# EA08AI.net
KiCad netlist of a schematic drawn in Altium Designer
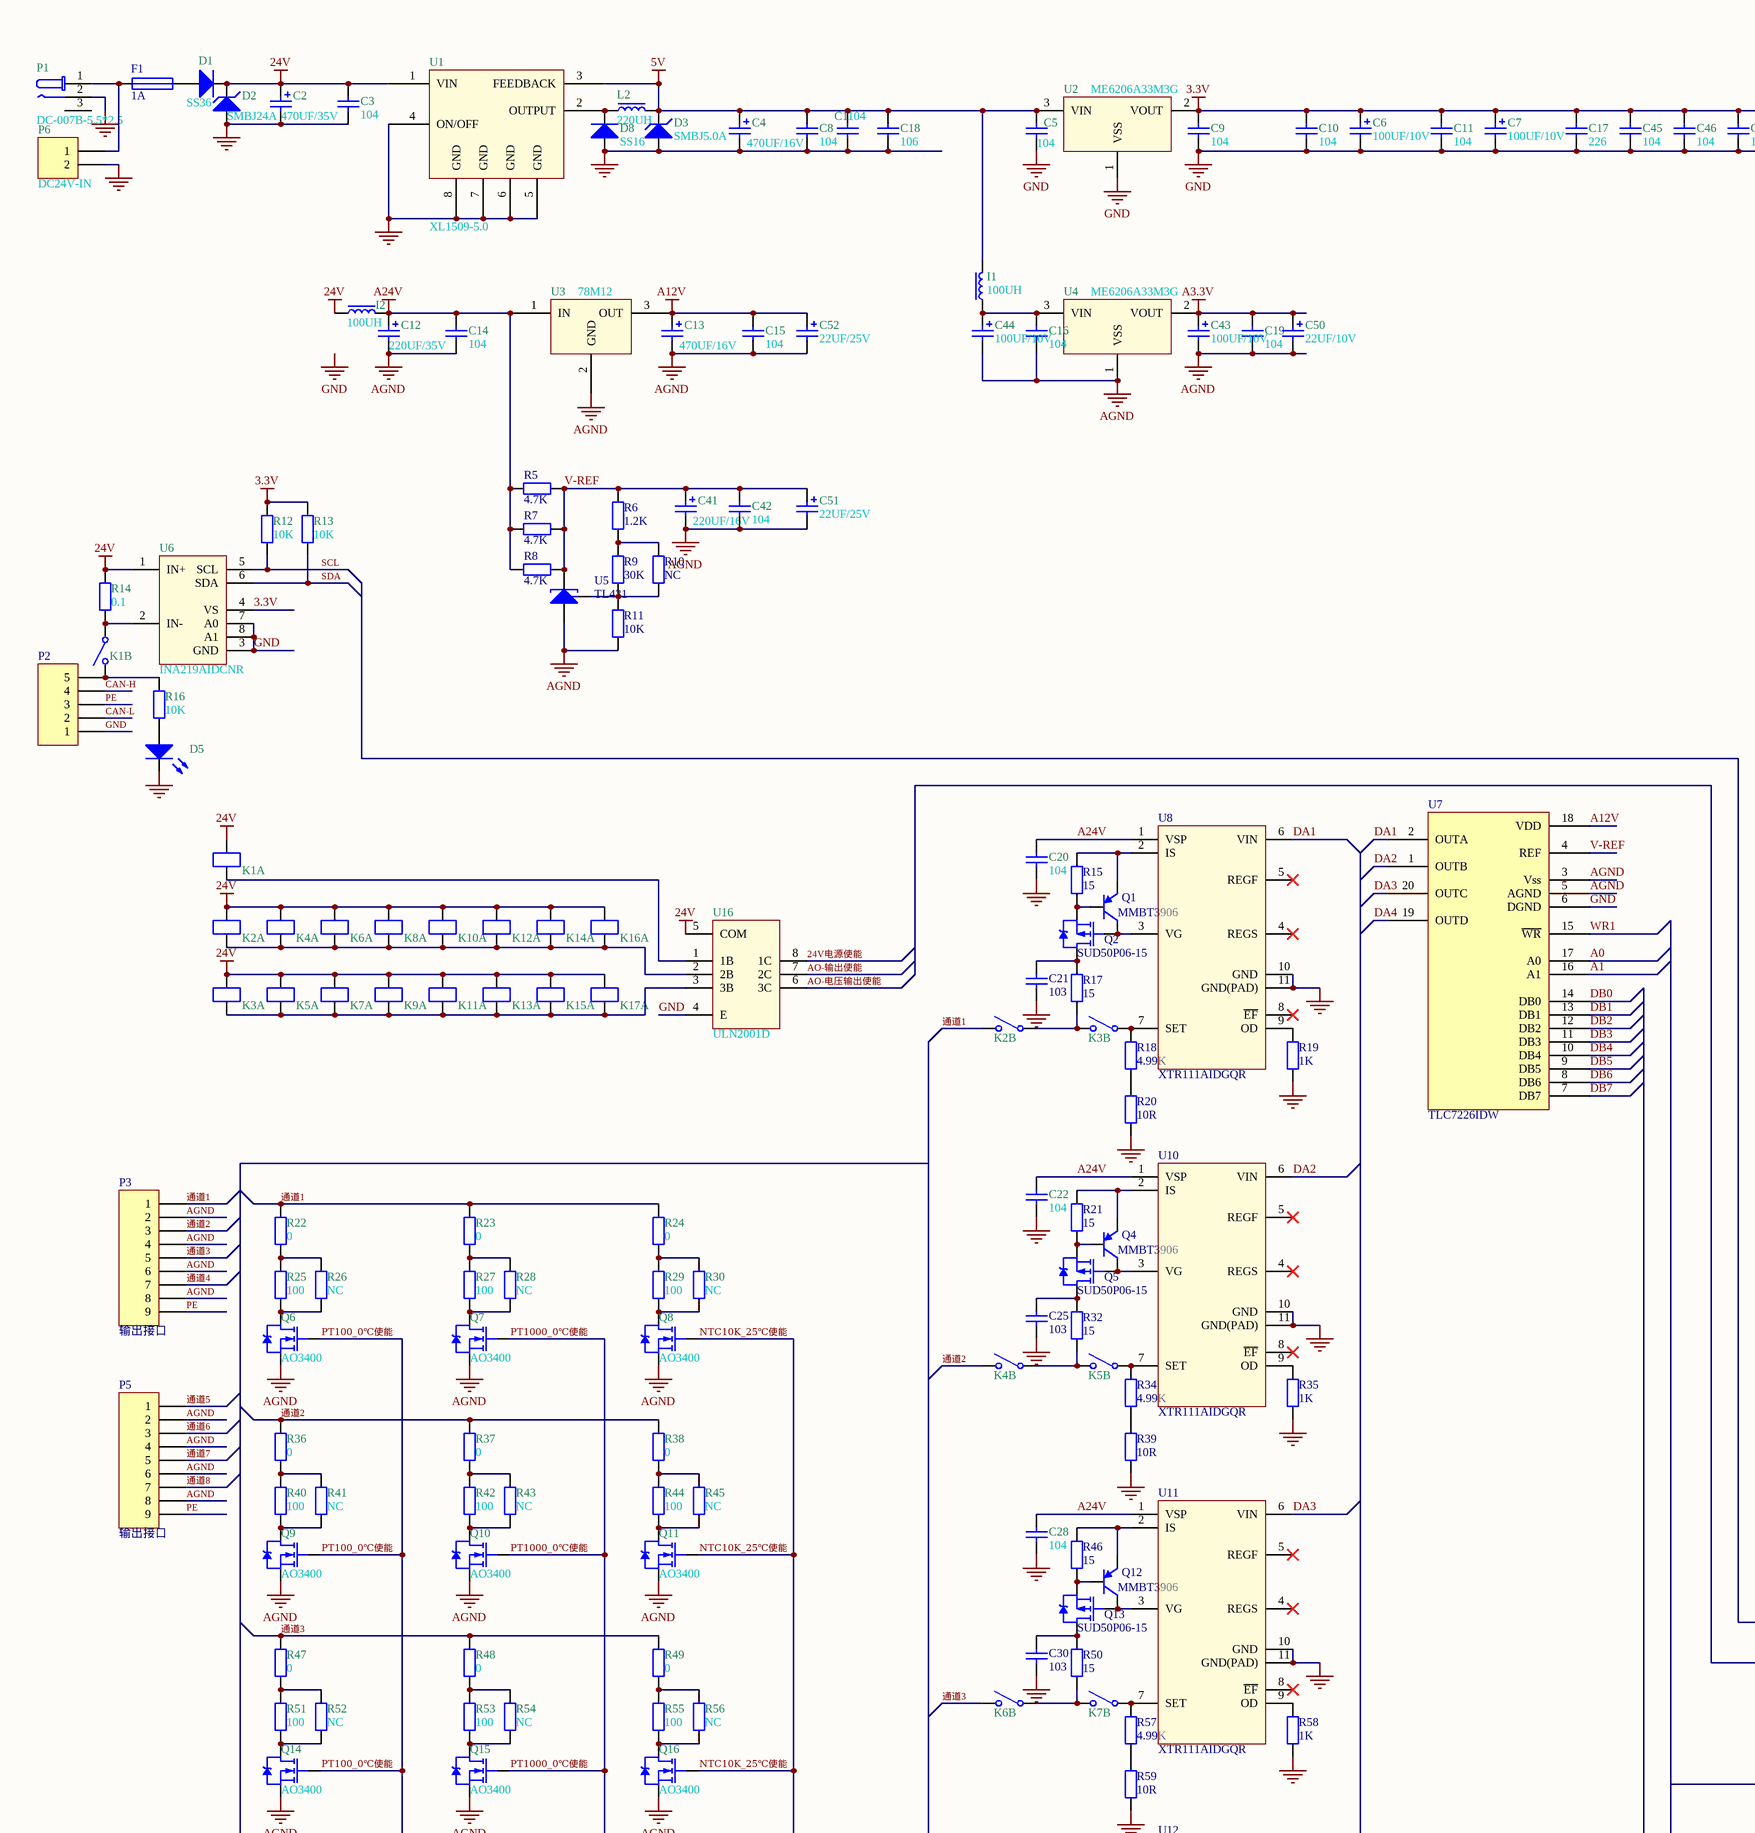
[diagram p0: EA08AI测试板.SchDoc, top left]
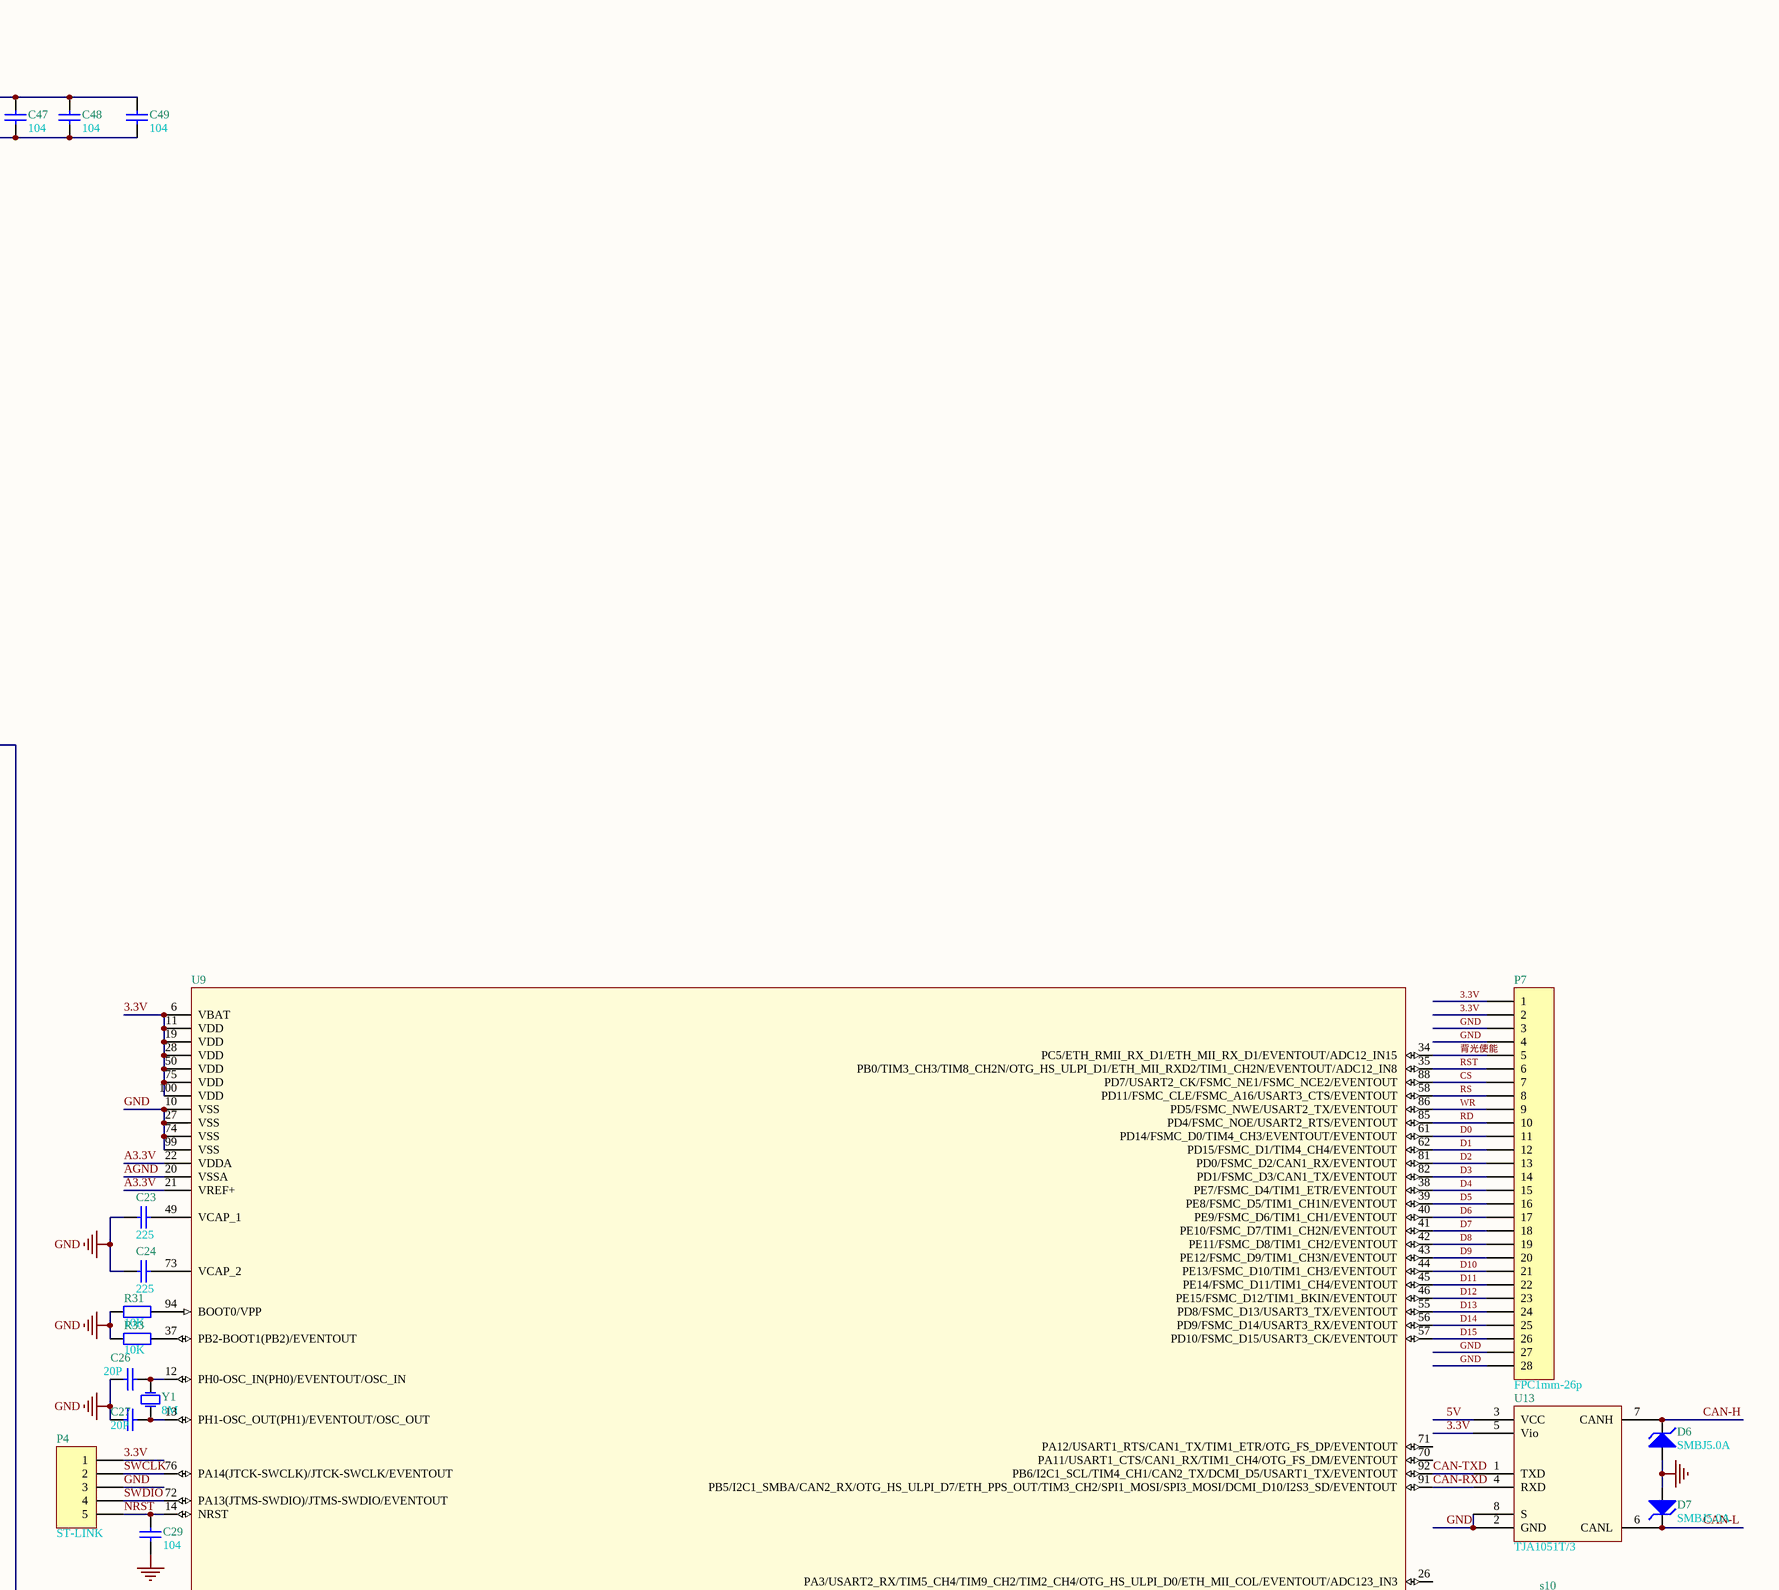
[diagram p1: EA08AI测试板.SchDoc, top right]
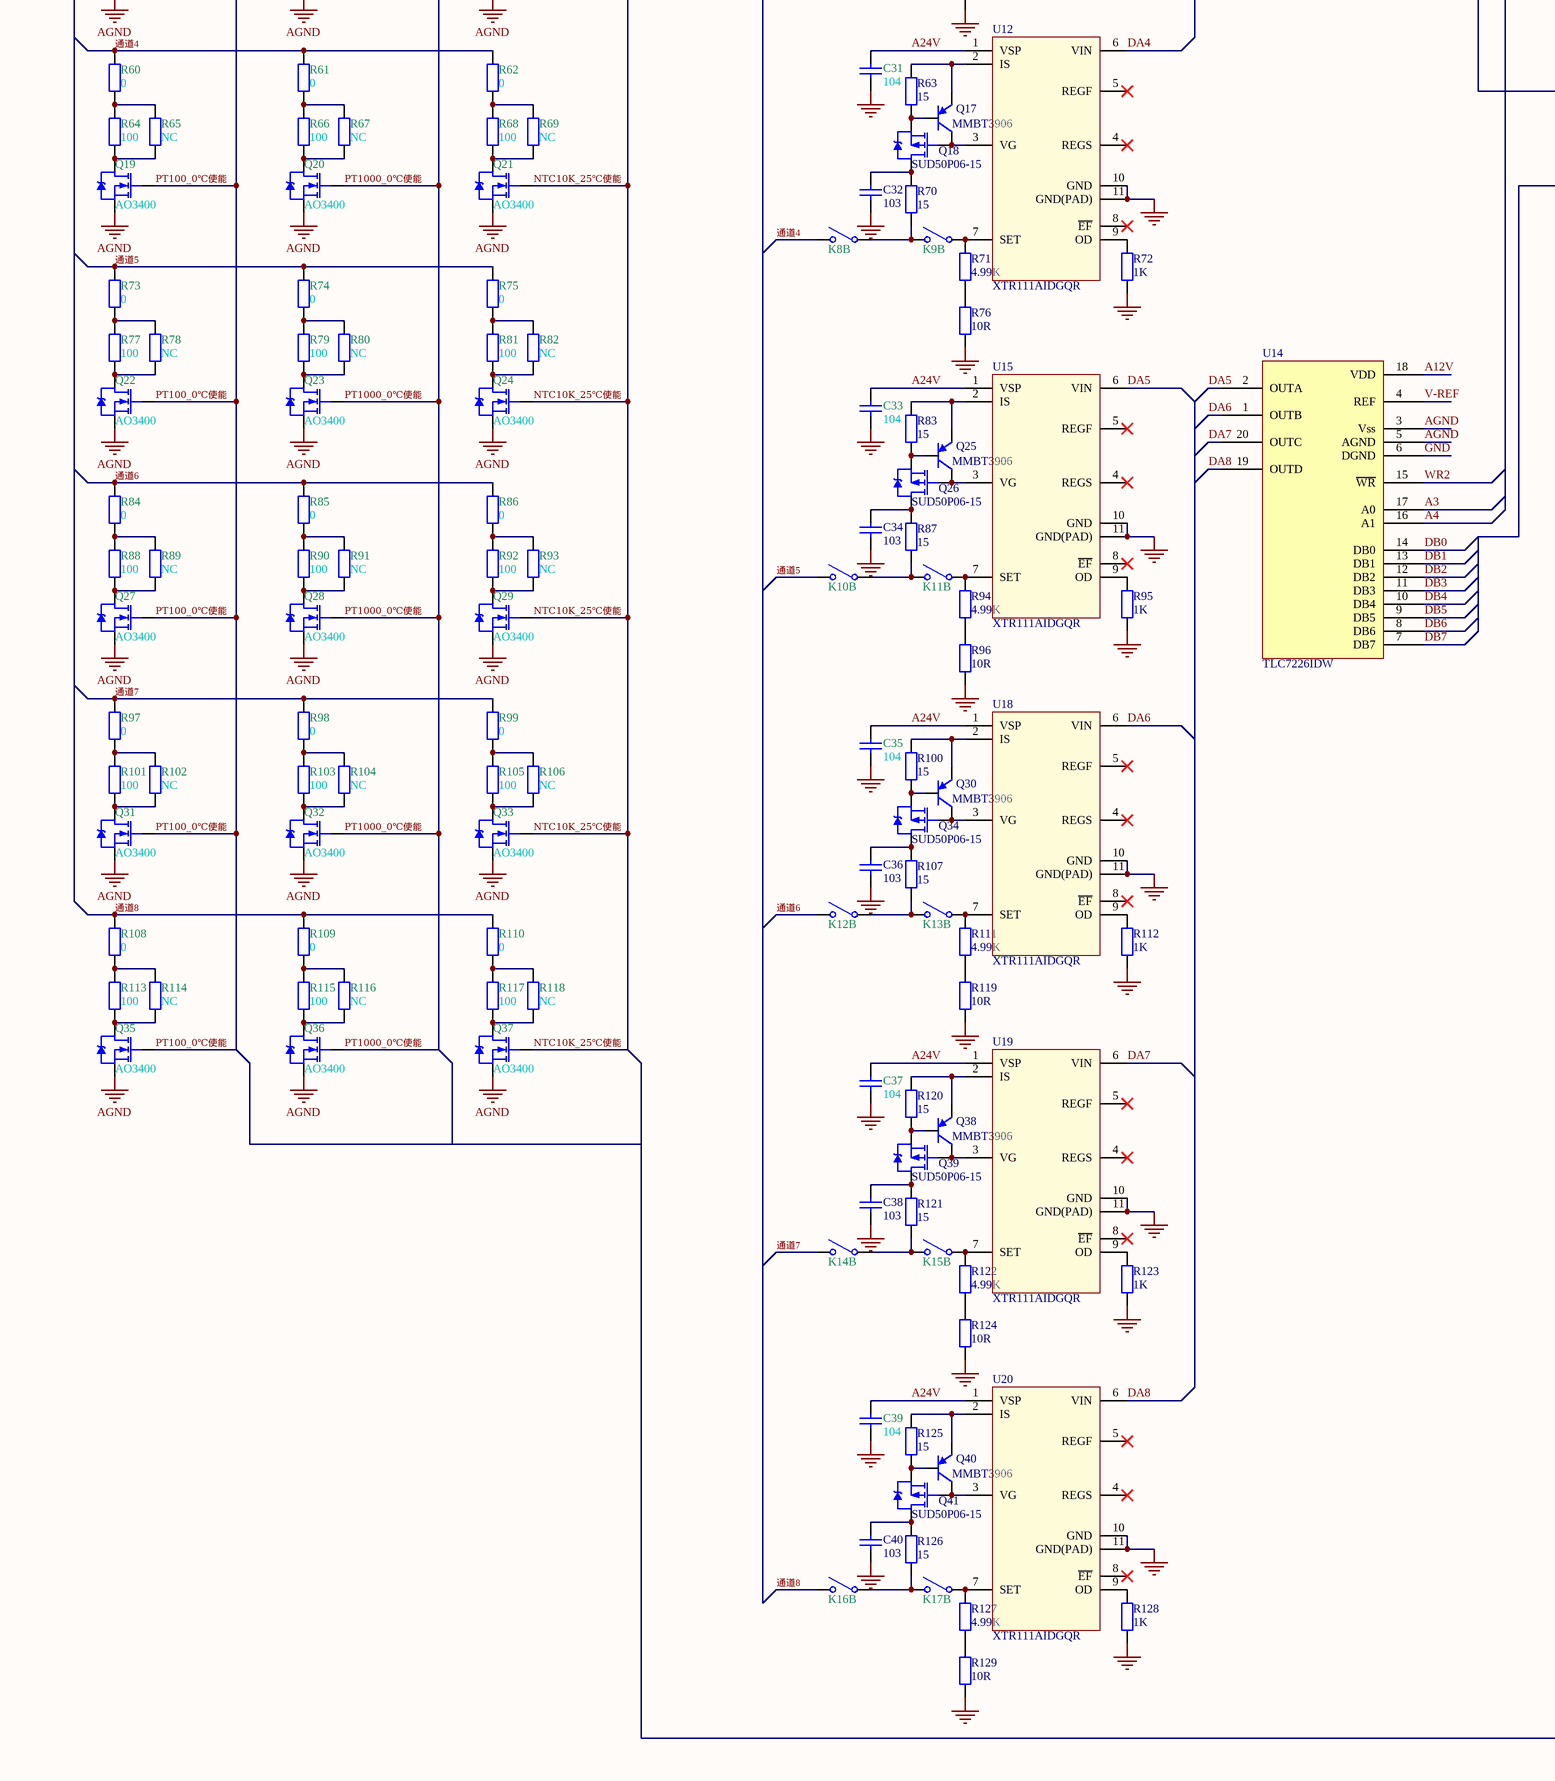
[diagram p2: EA08AI测试板.SchDoc, bottom left]
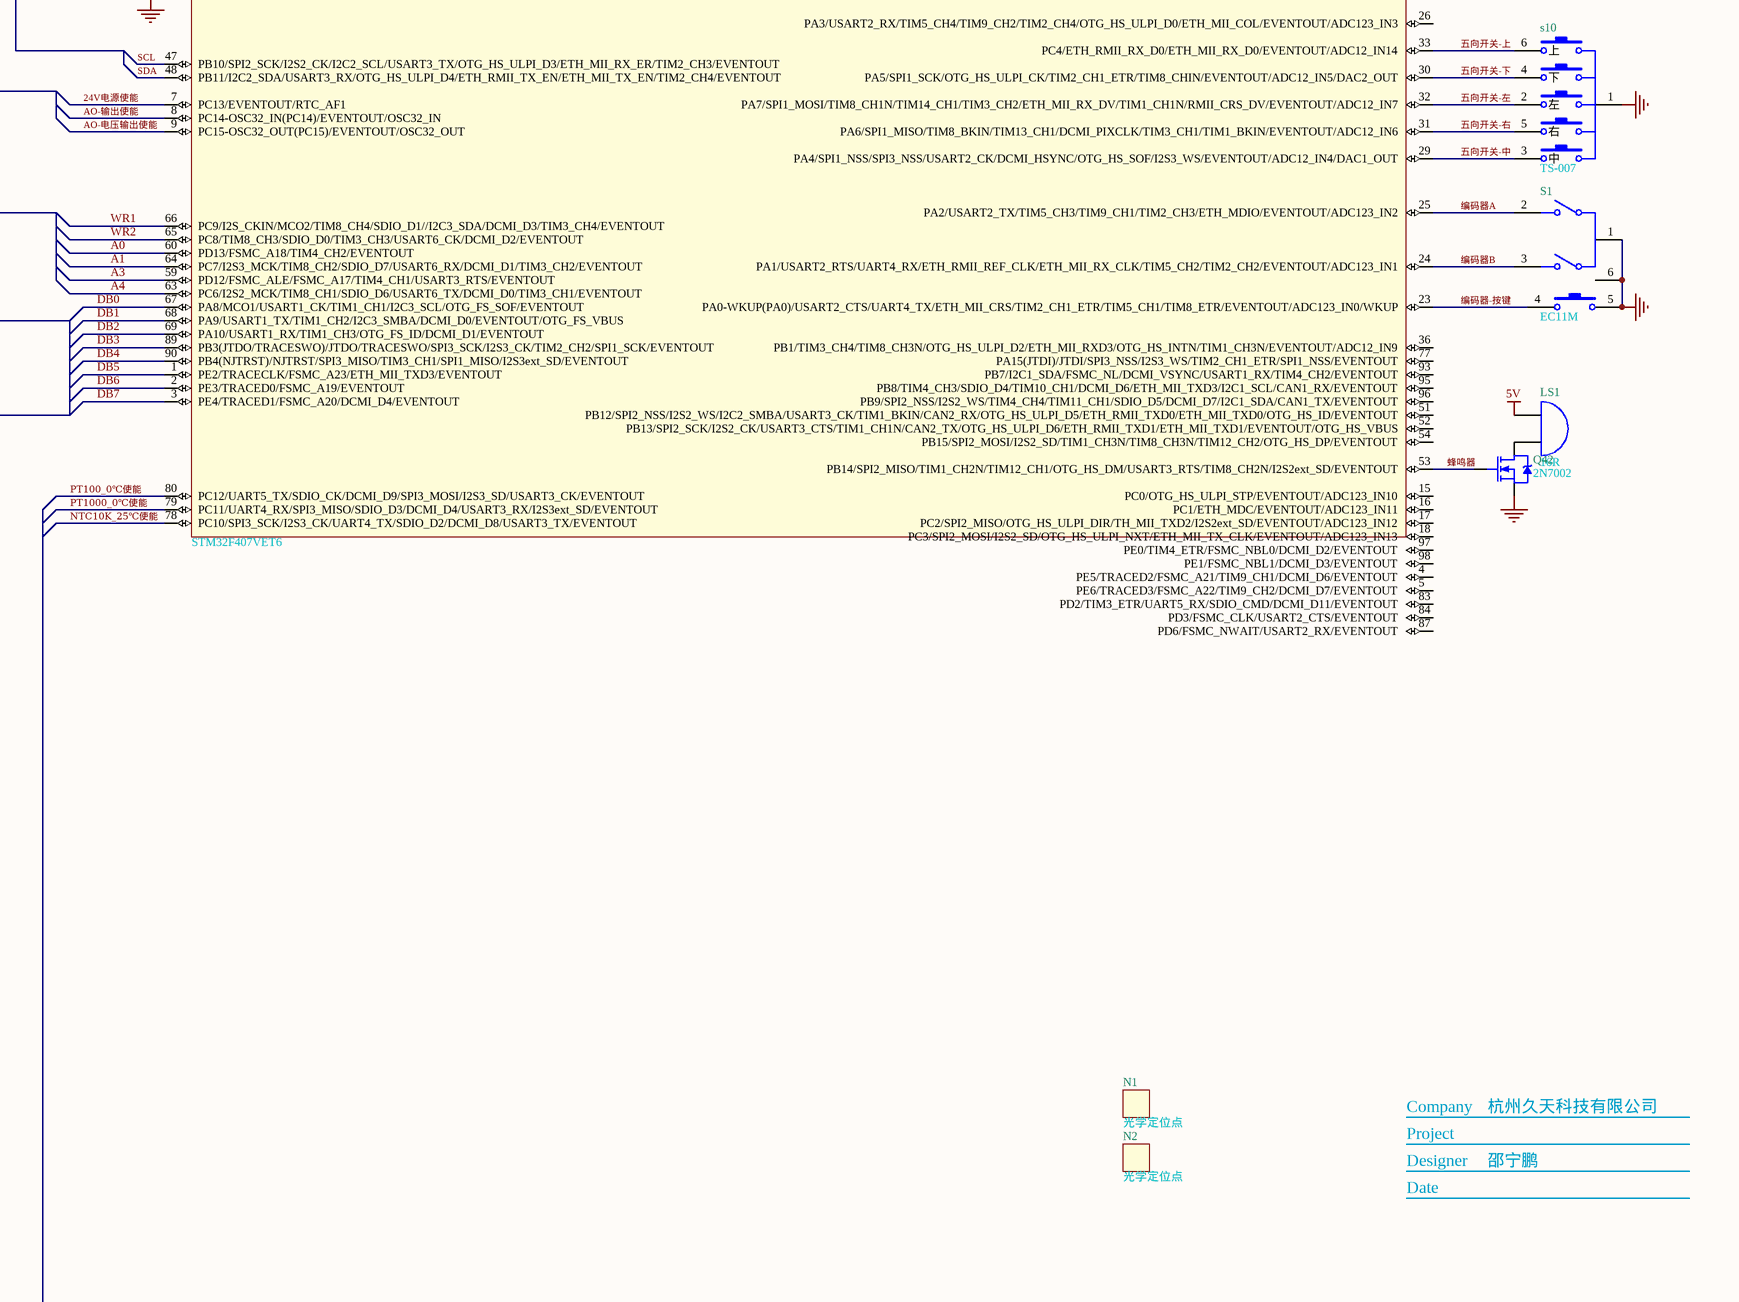
[diagram p3: EA08AI测试板.SchDoc, bottom right]

(export (version "E")
  (design (tool "Eeschema 10.0.6"))
  (components
    (comp (ref "C1")
      (value "104")
      (footprint "C-0603")
      (description "Capacitor")
      (fields (field (name "PUBLISHER") "Altium Limited"))
      (libsource (lib "元件2.0") (part "Cap"))
    )
    (comp (ref "C2")
      (value "470UF/35V")
      (footprint "贴片固态电容10*10")
      (description "电解电容")
      (fields (field (name "PUBLISHER") "Altium Limited"))
      (libsource (lib "2电容-V1.0") (part "Cap Pol1"))
    )
    (comp (ref "C3")
      (value "104")
      (footprint "C-0603")
      (description "Capacitor")
      (fields (field (name "PUBLISHER") "Altium Limited"))
      (libsource (lib "元件2.0") (part "Cap"))
    )
    (comp (ref "C4")
      (value "470UF/16V")
      (footprint "贴片固态电容8*10-M")
      (description "Polarized Capacitor (Radial)")
      (fields (field (name "PUBLISHER") "Altium Limited"))
      (libsource (lib "元件2.0") (part "Cap Pol1"))
    )
    (comp (ref "C5")
      (value "104")
      (footprint "C-0603")
      (description "Capacitor")
      (fields (field (name "PUBLISHER") "Altium Limited"))
      (libsource (lib "元件2.0") (part "Cap"))
    )
    (comp (ref "C6")
      (value "100UF/10V")
      (footprint "贴片固态电容5*5.3")
      (description "Polarized Capacitor (Radial)")
      (fields (field (name "PUBLISHER") "Altium Limited"))
      (libsource (lib "元件2.0") (part "Cap Pol1"))
    )
    (comp (ref "C7")
      (value "100UF/10V")
      (footprint "C-7343")
      (description "Polarized Capacitor (Radial)")
      (fields (field (name "PUBLISHER") "Altium Limited"))
      (libsource (lib "元件2.0") (part "Cap Pol1"))
    )
    (comp (ref "C8")
      (value "104")
      (footprint "C-0603")
      (description "Capacitor")
      (fields (field (name "PUBLISHER") "Altium Limited"))
      (libsource (lib "元件2.0") (part "Cap"))
    )
    (comp (ref "C9")
      (value "104")
      (footprint "C-0603")
      (description "Capacitor")
      (fields (field (name "PUBLISHER") "Altium Limited"))
      (libsource (lib "元件2.0") (part "Cap"))
    )
    (comp (ref "C10")
      (value "104")
      (footprint "C-0603")
      (description "Capacitor")
      (fields (field (name "PUBLISHER") "Altium Limited"))
      (libsource (lib "元件2.0") (part "Cap"))
    )
    (comp (ref "C11")
      (value "104")
      (footprint "C-0603")
      (description "Capacitor")
      (fields (field (name "PUBLISHER") "Altium Limited"))
      (libsource (lib "元件2.0") (part "Cap"))
    )
    (comp (ref "C12")
      (value "220UF/35V")
      (footprint "贴片固态电容8*10-M")
      (description "电解电容")
      (fields (field (name "PUBLISHER") "Altium Limited"))
      (libsource (lib "2电容-V1.0") (part "Cap Pol1"))
    )
    (comp (ref "C13")
      (value "470UF/16V")
      (footprint "贴片固态电容8*10-M")
      (description "Polarized Capacitor (Radial)")
      (fields (field (name "PUBLISHER") "Altium Limited"))
      (libsource (lib "元件2.0") (part "Cap Pol1"))
    )
    (comp (ref "C14")
      (value "104")
      (footprint "C-0603")
      (description "Capacitor")
      (fields (field (name "PUBLISHER") "Altium Limited"))
      (libsource (lib "元件2.0") (part "Cap"))
    )
    (comp (ref "C15")
      (value "104")
      (footprint "C-0603")
      (description "Capacitor")
      (fields (field (name "PUBLISHER") "Altium Limited"))
      (libsource (lib "元件2.0") (part "Cap"))
    )
    (comp (ref "C16")
      (value "104")
      (footprint "C-0603")
      (description "Capacitor")
      (fields (field (name "PUBLISHER") "Altium Limited"))
      (libsource (lib "元件2.0") (part "Cap"))
    )
    (comp (ref "C17")
      (value "226")
      (footprint "C-0805")
      (description "Capacitor")
      (fields (field (name "PUBLISHER") "Altium Limited"))
      (libsource (lib "元件2.0") (part "Cap"))
    )
    (comp (ref "C18")
      (value "106")
      (footprint "C-0805")
      (description "Capacitor")
      (fields (field (name "PUBLISHER") "Altium Limited"))
      (libsource (lib "元件2.0") (part "Cap"))
    )
    (comp (ref "C19")
      (value "104")
      (footprint "C-0603")
      (description "Capacitor")
      (fields (field (name "PUBLISHER") "Altium Limited"))
      (libsource (lib "元件2.0") (part "Cap"))
    )
    (comp (ref "C20")
      (value "104")
      (footprint "C-0603")
      (description "Capacitor")
      (fields (field (name "PUBLISHER") "Altium Limited"))
      (libsource (lib "元件2.0") (part "Cap"))
    )
    (comp (ref "C21")
      (value "103")
      (footprint "C-0603")
      (description "0805")
      (fields (field (name "PUBLISHER") "Altium Limited"))
      (libsource (lib "2电容-V1.0") (part "Cap-0603"))
    )
    (comp (ref "C22")
      (value "104")
      (footprint "C-0603")
      (description "Capacitor")
      (fields (field (name "PUBLISHER") "Altium Limited"))
      (libsource (lib "元件2.0") (part "Cap"))
    )
    (comp (ref "C23")
      (value "225")
      (footprint "C-0603")
      (description "0805")
      (fields (field (name "PUBLISHER") "Altium Limited"))
      (libsource (lib "2电容-V1.0") (part "Cap-0603"))
    )
    (comp (ref "C24")
      (value "225")
      (footprint "C-0603")
      (description "0805")
      (fields (field (name "PUBLISHER") "Altium Limited"))
      (libsource (lib "2电容-V1.0") (part "Cap-0603"))
    )
    (comp (ref "C25")
      (value "103")
      (footprint "C-0603")
      (description "0805")
      (fields (field (name "PUBLISHER") "Altium Limited"))
      (libsource (lib "2电容-V1.0") (part "Cap-0603"))
    )
    (comp (ref "C26")
      (value "20P")
      (footprint "C-0603")
      (description "0805")
      (fields (field (name "PUBLISHER") "Altium Limited"))
      (libsource (lib "2电容-V1.0") (part "Cap-0603"))
    )
    (comp (ref "C27")
      (value "20P")
      (footprint "C-0603")
      (description "0805")
      (fields (field (name "PUBLISHER") "Altium Limited"))
      (libsource (lib "2电容-V1.0") (part "Cap-0603"))
    )
    (comp (ref "C28")
      (value "104")
      (footprint "C-0603")
      (description "Capacitor")
      (fields (field (name "PUBLISHER") "Altium Limited"))
      (libsource (lib "元件2.0") (part "Cap"))
    )
    (comp (ref "C29")
      (value "104")
      (footprint "C-0603")
      (description "0805")
      (fields (field (name "PUBLISHER") "Altium Limited"))
      (libsource (lib "2电容-V1.0") (part "Cap-0603"))
    )
    (comp (ref "C30")
      (value "103")
      (footprint "C-0603")
      (description "0805")
      (fields (field (name "PUBLISHER") "Altium Limited"))
      (libsource (lib "2电容-V1.0") (part "Cap-0603"))
    )
    (comp (ref "C31")
      (value "104")
      (footprint "C-0603")
      (description "Capacitor")
      (fields (field (name "PUBLISHER") "Altium Limited"))
      (libsource (lib "元件2.0") (part "Cap"))
    )
    (comp (ref "C32")
      (value "103")
      (footprint "C-0603")
      (description "0805")
      (fields (field (name "PUBLISHER") "Altium Limited"))
      (libsource (lib "2电容-V1.0") (part "Cap-0603"))
    )
    (comp (ref "C33")
      (value "104")
      (footprint "C-0603")
      (description "Capacitor")
      (fields (field (name "PUBLISHER") "Altium Limited"))
      (libsource (lib "元件2.0") (part "Cap"))
    )
    (comp (ref "C34")
      (value "103")
      (footprint "C-0603")
      (description "0805")
      (fields (field (name "PUBLISHER") "Altium Limited"))
      (libsource (lib "2电容-V1.0") (part "Cap-0603"))
    )
    (comp (ref "C35")
      (value "104")
      (footprint "C-0603")
      (description "Capacitor")
      (fields (field (name "PUBLISHER") "Altium Limited"))
      (libsource (lib "元件2.0") (part "Cap"))
    )
    (comp (ref "C36")
      (value "103")
      (footprint "C-0603")
      (description "0805")
      (fields (field (name "PUBLISHER") "Altium Limited"))
      (libsource (lib "2电容-V1.0") (part "Cap-0603"))
    )
    (comp (ref "C37")
      (value "104")
      (footprint "C-0603")
      (description "Capacitor")
      (fields (field (name "PUBLISHER") "Altium Limited"))
      (libsource (lib "元件2.0") (part "Cap"))
    )
    (comp (ref "C38")
      (value "103")
      (footprint "C-0603")
      (description "0805")
      (fields (field (name "PUBLISHER") "Altium Limited"))
      (libsource (lib "2电容-V1.0") (part "Cap-0603"))
    )
    (comp (ref "C39")
      (value "104")
      (footprint "C-0603")
      (description "Capacitor")
      (fields (field (name "PUBLISHER") "Altium Limited"))
      (libsource (lib "元件2.0") (part "Cap"))
    )
    (comp (ref "C40")
      (value "103")
      (footprint "C-0603")
      (description "0805")
      (fields (field (name "PUBLISHER") "Altium Limited"))
      (libsource (lib "2电容-V1.0") (part "Cap-0603"))
    )
    (comp (ref "C41")
      (value "220UF/16V")
      (footprint "贴片固态电容6.3*7.7")
      (description "Polarized Capacitor (Radial)")
      (fields (field (name "PUBLISHER") "Altium Limited"))
      (libsource (lib "元件2.0") (part "Cap Pol1"))
    )
    (comp (ref "C42")
      (value "104")
      (footprint "C-0603")
      (description "Capacitor")
      (fields (field (name "PUBLISHER") "Altium Limited"))
      (libsource (lib "元件2.0") (part "Cap"))
    )
    (comp (ref "C43")
      (value "100UF/10V")
      (footprint "贴片固态电容5*5.3")
      (description "Polarized Capacitor (Radial)")
      (fields (field (name "PUBLISHER") "Altium Limited"))
      (libsource (lib "元件2.0") (part "Cap Pol1"))
    )
    (comp (ref "C44")
      (value "100UF/10V")
      (footprint "贴片固态电容5*5.3")
      (description "Polarized Capacitor (Radial)")
      (fields (field (name "PUBLISHER") "Altium Limited"))
      (libsource (lib "元件2.0") (part "Cap Pol1"))
    )
    (comp (ref "C45")
      (value "104")
      (footprint "C-0603")
      (description "Capacitor")
      (fields (field (name "PUBLISHER") "Altium Limited"))
      (libsource (lib "元件2.0") (part "Cap"))
    )
    (comp (ref "C46")
      (value "104")
      (footprint "C-0603")
      (description "Capacitor")
      (fields (field (name "PUBLISHER") "Altium Limited"))
      (libsource (lib "元件2.0") (part "Cap"))
    )
    (comp (ref "C47")
      (value "104")
      (footprint "C-0603")
      (description "Capacitor")
      (fields (field (name "PUBLISHER") "Altium Limited"))
      (libsource (lib "元件2.0") (part "Cap"))
    )
    (comp (ref "C48")
      (value "104")
      (footprint "C-0603")
      (description "Capacitor")
      (fields (field (name "PUBLISHER") "Altium Limited"))
      (libsource (lib "元件2.0") (part "Cap"))
    )
    (comp (ref "C49")
      (value "104")
      (footprint "C-0603")
      (description "Capacitor")
      (fields (field (name "PUBLISHER") "Altium Limited"))
      (libsource (lib "元件2.0") (part "Cap"))
    )
    (comp (ref "C50")
      (value "22UF/10V")
      (footprint "C-3216")
      (description "Polarized Capacitor (Radial)")
      (fields (field (name "PUBLISHER") "Altium Limited"))
      (libsource (lib "元件2.0") (part "Cap Pol1"))
    )
    (comp (ref "C51")
      (value "22UF/25V")
      (footprint "C-3528")
      (description "Polarized Capacitor (Radial)")
      (fields (field (name "PUBLISHER") "Altium Limited"))
      (libsource (lib "元件2.0") (part "Cap Pol1"))
    )
    (comp (ref "C52")
      (value "22UF/25V")
      (footprint "C-3528")
      (description "Polarized Capacitor (Radial)")
      (fields (field (name "PUBLISHER") "Altium Limited"))
      (libsource (lib "元件2.0") (part "Cap Pol1"))
    )
    (comp (ref "D1")
      (value "SS36")
      (footprint "SMB")
      (description "SMB")
      (fields (field (name "PUBLISHER") "Altium Limited"))
      (libsource (lib "4二极管-V1.1") (part "SS36"))
    )
    (comp (ref "D2")
      (value "SMBJ24A")
      (footprint "SMB")
      (description "SMB")
      (libsource (lib "4二极管-V1.1") (part "TVS-1"))
    )
    (comp (ref "D3")
      (value "SMBJ5.0A")
      (footprint "SMB")
      (description "SMB")
      (libsource (lib "4二极管-V1.1") (part "TVS-1"))
    )
    (comp (ref "D5")
      (value "~")
      (footprint "LED-0603-GREEN")
      (fields (field (name "PUBLISHER") "Altium Limited"))
      (libsource (lib "4二极管-V1.1") (part "LED-0603-Blue"))
    )
    (comp (ref "D6")
      (value "SMBJ5.0A")
      (footprint "SMB-N")
      (description "SMB")
      (libsource (lib "4二极管-V1.1") (part "TVS-1"))
    )
    (comp (ref "D7")
      (value "SMBJ5.0A")
      (footprint "SMB-N")
      (description "SMB")
      (libsource (lib "4二极管-V1.1") (part "TVS-1"))
    )
    (comp (ref "D8")
      (value "SS16")
      (footprint "SMA")
      (description "SMA")
      (libsource (lib "4二极管-V1.1") (part "SS14"))
    )
    (comp (ref "F1")
      (value "1A")
      (footprint "FUSE-1808保险丝座")
      (description "Fuse")
      (fields (field (name "PUBLISHER") "Altium Limited"))
      (libsource (lib "11其他元件-V1.0") (part "Fuse 1"))
    )
    (comp (ref "I1") (value "100UH") (footprint "CDRH74R") (libsource (lib "3电感-V1.0") (part "Inductance3")))
    (comp (ref "I2") (value "100UH") (footprint "CDRH74R") (libsource (lib "3电感-V1.0") (part "Inductance3")))
    (comp (ref "K1")
      (value "HF49FD-D24-1H11")
      (footprint "HF49FD-D24-1H11")
      (libsource (lib "10继电器-V1.0") (part "HF49FD-D24-1H11"))
    )
    (comp (ref "K2")
      (value "HF49FD-D24-1H11")
      (footprint "HF49FD-D24-1H11")
      (libsource (lib "") (part "HF49FD-D24-1H11_1"))
    )
    (comp (ref "K3")
      (value "HF49FD-D24-1H11")
      (footprint "HF49FD-D24-1H11")
      (libsource (lib "") (part "HF49FD-D24-1H11_1"))
    )
    (comp (ref "K4")
      (value "HF49FD-D24-1H11")
      (footprint "HF49FD-D24-1H11")
      (libsource (lib "") (part "HF49FD-D24-1H11_1"))
    )
    (comp (ref "K5")
      (value "HF49FD-D24-1H11")
      (footprint "HF49FD-D24-1H11")
      (libsource (lib "10继电器-V1.0") (part "HF49FD-D24-1H11"))
    )
    (comp (ref "K6")
      (value "HF49FD-D24-1H11")
      (footprint "HF49FD-D24-1H11")
      (libsource (lib "10继电器-V1.0") (part "HF49FD-D24-1H11"))
    )
    (comp (ref "K7")
      (value "HF49FD-D24-1H11")
      (footprint "HF49FD-D24-1H11")
      (libsource (lib "") (part "HF49FD-D24-1H11_1"))
    )
    (comp (ref "K8")
      (value "HF49FD-D24-1H11")
      (footprint "HF49FD-D24-1H11")
      (libsource (lib "10继电器-V1.0") (part "HF49FD-D24-1H11"))
    )
    (comp (ref "K9")
      (value "HF49FD-D24-1H11")
      (footprint "HF49FD-D24-1H11")
      (libsource (lib "10继电器-V1.0") (part "HF49FD-D24-1H11"))
    )
    (comp (ref "K10")
      (value "HF49FD-D24-1H11")
      (footprint "HF49FD-D24-1H11")
      (libsource (lib "") (part "HF49FD-D24-1H11_1"))
    )
    (comp (ref "K11")
      (value "HF49FD-D24-1H11")
      (footprint "HF49FD-D24-1H11")
      (libsource (lib "10继电器-V1.0") (part "HF49FD-D24-1H11"))
    )
    (comp (ref "K12")
      (value "HF49FD-D24-1H11")
      (footprint "HF49FD-D24-1H11")
      (libsource (lib "") (part "HF49FD-D24-1H11_1"))
    )
    (comp (ref "K13")
      (value "HF49FD-D24-1H11")
      (footprint "HF49FD-D24-1H11")
      (libsource (lib "") (part "HF49FD-D24-1H11_1"))
    )
    (comp (ref "K14")
      (value "HF49FD-D24-1H11")
      (footprint "HF49FD-D24-1H11")
      (libsource (lib "10继电器-V1.0") (part "HF49FD-D24-1H11"))
    )
    (comp (ref "K15")
      (value "HF49FD-D24-1H11")
      (footprint "HF49FD-D24-1H11")
      (libsource (lib "10继电器-V1.0") (part "HF49FD-D24-1H11"))
    )
    (comp (ref "K16")
      (value "HF49FD-D24-1H11")
      (footprint "HF49FD-D24-1H11")
      (libsource (lib "10继电器-V1.0") (part "HF49FD-D24-1H11"))
    )
    (comp (ref "K17")
      (value "HF49FD-D24-1H11")
      (footprint "HF49FD-D24-1H11")
      (libsource (lib "10继电器-V1.0") (part "HF49FD-D24-1H11"))
    )
    (comp (ref "L2") (value "220UH") (footprint "CDRH127R") (libsource (lib "3电感-V1.0") (part "Inductance3")))
    (comp (ref "LS1")
      (value "16R")
      (footprint "蜂鸣器 YH-8503-A")
      (description "Electrical Bell")
      (fields (field (name "PUBLISHER") "Altium Limited"))
      (libsource (lib "11其他元件-V1.0") (part "Bell"))
    )
    (comp (ref "N1") (value "光学定位点") (footprint "MARK-1mm-3mm") (libsource (lib "11其他元件-V1.0") (part "无引脚")))
    (comp (ref "N2") (value "光学定位点") (footprint "MARK-1mm-3mm") (libsource (lib "11其他元件-V1.0") (part "无引脚")))
    (comp (ref "P1")
      (value "DC-007B-5.5*2.5")
      (footprint "DC-007B")
      (libsource (lib "PJ系列") (part "DC-007B"))
    )
    (comp (ref "P2")
      (value "~")
      (footprint "KF2EDGVC-5.08-5P弯针")
      (description "Header, 5-Pin")
      (fields (field (name "PUBLISHER") "Altium Limited"))
      (libsource (lib "5排针-V1.0") (part "Header 5"))
    )
    (comp (ref "P3")
      (value "输出接口")
      (footprint "KF2EDGVC-5.08-9P")
      (description "Header, 9-Pin")
      (fields (field (name "PUBLISHER") "Altium Limited"))
      (libsource (lib "5排针-V1.0") (part "Header 9"))
    )
    (comp (ref "P4")
      (value "ST-LINK")
      (footprint "HDR1X5")
      (description "Header, 5-Pin")
      (fields (field (name "PUBLISHER") "Altium Limited"))
      (libsource (lib "") (part "Header 5_1"))
    )
    (comp (ref "P5")
      (value "输出接口")
      (footprint "KF2EDGVC-5.08-9P")
      (description "Header, 9-Pin")
      (fields (field (name "PUBLISHER") "Altium Limited"))
      (libsource (lib "5排针-V1.0") (part "Header 9"))
    )
    (comp (ref "P6")
      (value "DC24V-IN")
      (footprint "KF2EDGVC-5.08-2P")
      (description "Header, 2-Pin")
      (fields (field (name "PUBLISHER") "Altium Limited"))
      (libsource (lib "5排针-V1.0") (part "Header 2"))
    )
    (comp (ref "P7")
      (value "FPC1mm-26p")
      (footprint "FPC-0.5mm_26P下接翻盖")
      (description "Header, 28-Pin")
      (fields (field (name "PUBLISHER") "Altium Limited"))
      (libsource (lib "5排针-V1.0") (part "Header 28"))
    )
    (comp (ref "Q1")
      (value "MMBT3906")
      (footprint "SOT-23")
      (description "PNP SOT-23")
      (fields (field (name "PUBLISHER") "Altium Limited"))
      (libsource (lib "4二极管-V1.1") (part "S8550"))
    )
    (comp (ref "Q2")
      (value "SUD50P06-15")
      (footprint "TO-252")
      (description "SOT-23")
      (libsource (lib "4二极管-V1.1") (part "AO3401"))
    )
    (comp (ref "Q4")
      (value "MMBT3906")
      (footprint "SOT-23")
      (description "PNP SOT-23")
      (fields (field (name "PUBLISHER") "Altium Limited"))
      (libsource (lib "4二极管-V1.1") (part "S8550"))
    )
    (comp (ref "Q5")
      (value "SUD50P06-15")
      (footprint "TO-252")
      (description "SOT-23")
      (libsource (lib "4二极管-V1.1") (part "AO3401"))
    )
    (comp (ref "Q6")
      (value "AO3400")
      (footprint "SOT-23")
      (description "SOT-23")
      (libsource (lib "4二极管-V1.1") (part "AO3400"))
    )
    (comp (ref "Q7")
      (value "AO3400")
      (footprint "SOT-23")
      (description "SOT-23")
      (libsource (lib "4二极管-V1.1") (part "AO3400"))
    )
    (comp (ref "Q8")
      (value "AO3400")
      (footprint "SOT-23")
      (description "SOT-23")
      (libsource (lib "4二极管-V1.1") (part "AO3400"))
    )
    (comp (ref "Q9")
      (value "AO3400")
      (footprint "SOT-23")
      (description "SOT-23")
      (libsource (lib "4二极管-V1.1") (part "AO3400"))
    )
    (comp (ref "Q10")
      (value "AO3400")
      (footprint "SOT-23")
      (description "SOT-23")
      (libsource (lib "4二极管-V1.1") (part "AO3400"))
    )
    (comp (ref "Q11")
      (value "AO3400")
      (footprint "SOT-23")
      (description "SOT-23")
      (libsource (lib "4二极管-V1.1") (part "AO3400"))
    )
    (comp (ref "Q12")
      (value "MMBT3906")
      (footprint "SOT-23")
      (description "PNP SOT-23")
      (fields (field (name "PUBLISHER") "Altium Limited"))
      (libsource (lib "4二极管-V1.1") (part "S8550"))
    )
    (comp (ref "Q13")
      (value "SUD50P06-15")
      (footprint "TO-252")
      (description "SOT-23")
      (libsource (lib "4二极管-V1.1") (part "AO3401"))
    )
    (comp (ref "Q14")
      (value "AO3400")
      (footprint "SOT-23")
      (description "SOT-23")
      (libsource (lib "4二极管-V1.1") (part "AO3400"))
    )
    (comp (ref "Q15")
      (value "AO3400")
      (footprint "SOT-23")
      (description "SOT-23")
      (libsource (lib "4二极管-V1.1") (part "AO3400"))
    )
    (comp (ref "Q16")
      (value "AO3400")
      (footprint "SOT-23")
      (description "SOT-23")
      (libsource (lib "4二极管-V1.1") (part "AO3400"))
    )
    (comp (ref "Q17")
      (value "MMBT3906")
      (footprint "SOT-23")
      (description "PNP SOT-23")
      (fields (field (name "PUBLISHER") "Altium Limited"))
      (libsource (lib "4二极管-V1.1") (part "S8550"))
    )
    (comp (ref "Q18")
      (value "SUD50P06-15")
      (footprint "TO-252")
      (description "SOT-23")
      (libsource (lib "4二极管-V1.1") (part "AO3401"))
    )
    (comp (ref "Q19")
      (value "AO3400")
      (footprint "SOT-23")
      (description "SOT-23")
      (libsource (lib "4二极管-V1.1") (part "AO3400"))
    )
    (comp (ref "Q20")
      (value "AO3400")
      (footprint "SOT-23")
      (description "SOT-23")
      (libsource (lib "4二极管-V1.1") (part "AO3400"))
    )
    (comp (ref "Q21")
      (value "AO3400")
      (footprint "SOT-23")
      (description "SOT-23")
      (libsource (lib "4二极管-V1.1") (part "AO3400"))
    )
    (comp (ref "Q22")
      (value "AO3400")
      (footprint "SOT-23")
      (description "SOT-23")
      (libsource (lib "4二极管-V1.1") (part "AO3400"))
    )
    (comp (ref "Q23")
      (value "AO3400")
      (footprint "SOT-23")
      (description "SOT-23")
      (libsource (lib "4二极管-V1.1") (part "AO3400"))
    )
    (comp (ref "Q24")
      (value "AO3400")
      (footprint "SOT-23")
      (description "SOT-23")
      (libsource (lib "4二极管-V1.1") (part "AO3400"))
    )
    (comp (ref "Q25")
      (value "MMBT3906")
      (footprint "SOT-23")
      (description "PNP SOT-23")
      (fields (field (name "PUBLISHER") "Altium Limited"))
      (libsource (lib "4二极管-V1.1") (part "S8550"))
    )
    (comp (ref "Q26")
      (value "SUD50P06-15")
      (footprint "TO-252")
      (description "SOT-23")
      (libsource (lib "4二极管-V1.1") (part "AO3401"))
    )
    (comp (ref "Q27")
      (value "AO3400")
      (footprint "SOT-23")
      (description "SOT-23")
      (libsource (lib "4二极管-V1.1") (part "AO3400"))
    )
    (comp (ref "Q28")
      (value "AO3400")
      (footprint "SOT-23")
      (description "SOT-23")
      (libsource (lib "4二极管-V1.1") (part "AO3400"))
    )
    (comp (ref "Q29")
      (value "AO3400")
      (footprint "SOT-23")
      (description "SOT-23")
      (libsource (lib "4二极管-V1.1") (part "AO3400"))
    )
    (comp (ref "Q30")
      (value "MMBT3906")
      (footprint "SOT-23")
      (description "PNP SOT-23")
      (fields (field (name "PUBLISHER") "Altium Limited"))
      (libsource (lib "4二极管-V1.1") (part "S8550"))
    )
    (comp (ref "Q31")
      (value "AO3400")
      (footprint "SOT-23")
      (description "SOT-23")
      (libsource (lib "4二极管-V1.1") (part "AO3400"))
    )
    (comp (ref "Q32")
      (value "AO3400")
      (footprint "SOT-23")
      (description "SOT-23")
      (libsource (lib "4二极管-V1.1") (part "AO3400"))
    )
    (comp (ref "Q33")
      (value "AO3400")
      (footprint "SOT-23")
      (description "SOT-23")
      (libsource (lib "4二极管-V1.1") (part "AO3400"))
    )
    (comp (ref "Q34")
      (value "SUD50P06-15")
      (footprint "TO-252")
      (description "SOT-23")
      (libsource (lib "4二极管-V1.1") (part "AO3401"))
    )
    (comp (ref "Q35")
      (value "AO3400")
      (footprint "SOT-23")
      (description "SOT-23")
      (libsource (lib "4二极管-V1.1") (part "AO3400"))
    )
    (comp (ref "Q36")
      (value "AO3400")
      (footprint "SOT-23")
      (description "SOT-23")
      (libsource (lib "4二极管-V1.1") (part "AO3400"))
    )
    (comp (ref "Q37")
      (value "AO3400")
      (footprint "SOT-23")
      (description "SOT-23")
      (libsource (lib "4二极管-V1.1") (part "AO3400"))
    )
    (comp (ref "Q38")
      (value "MMBT3906")
      (footprint "SOT-23")
      (description "PNP SOT-23")
      (fields (field (name "PUBLISHER") "Altium Limited"))
      (libsource (lib "4二极管-V1.1") (part "S8550"))
    )
    (comp (ref "Q39")
      (value "SUD50P06-15")
      (footprint "TO-252")
      (description "SOT-23")
      (libsource (lib "4二极管-V1.1") (part "AO3401"))
    )
    (comp (ref "Q40")
      (value "MMBT3906")
      (footprint "SOT-23")
      (description "PNP SOT-23")
      (fields (field (name "PUBLISHER") "Altium Limited"))
      (libsource (lib "4二极管-V1.1") (part "S8550"))
    )
    (comp (ref "Q41")
      (value "SUD50P06-15")
      (footprint "TO-252")
      (description "SOT-23")
      (libsource (lib "4二极管-V1.1") (part "AO3401"))
    )
    (comp (ref "Q42") (value "2N7002") (footprint "SOT-23") (libsource (lib "4二极管-V1.1") (part "2N7002")))
    (comp (ref "R5")
      (value "4.7K")
      (footprint "R-1206")
      (description "0603")
      (fields (field (name "PUBLISHER") "Altium Limited"))
      (libsource (lib "") (part "Res2-0603_1"))
    )
    (comp (ref "R6")
      (value "1.2K")
      (footprint "R-0603")
      (description "0603")
      (fields (field (name "PUBLISHER") "Altium Limited"))
      (libsource (lib "1电阻-V1.0") (part "Res2-0603"))
    )
    (comp (ref "R7")
      (value "4.7K")
      (footprint "R-1206")
      (description "0603")
      (fields (field (name "PUBLISHER") "Altium Limited"))
      (libsource (lib "") (part "Res2-0603_1"))
    )
    (comp (ref "R8")
      (value "4.7K")
      (footprint "R-1206")
      (description "0603")
      (fields (field (name "PUBLISHER") "Altium Limited"))
      (libsource (lib "") (part "Res2-0603_1"))
    )
    (comp (ref "R9")
      (value "30K")
      (footprint "R-0603")
      (description "0603")
      (fields (field (name "PUBLISHER") "Altium Limited"))
      (libsource (lib "1电阻-V1.0") (part "Res2-0603"))
    )
    (comp (ref "R10")
      (value "NC")
      (footprint "R-0603")
      (description "0603")
      (fields (field (name "PUBLISHER") "Altium Limited"))
      (libsource (lib "1电阻-V1.0") (part "Res2-0603"))
    )
    (comp (ref "R11")
      (value "10K")
      (footprint "R-0603")
      (description "0603")
      (fields (field (name "PUBLISHER") "Altium Limited"))
      (libsource (lib "1电阻-V1.0") (part "Res2-0603"))
    )
    (comp (ref "R12")
      (value "10K")
      (footprint "R-0603")
      (description "0603")
      (fields (field (name "PUBLISHER") "Altium Limited"))
      (libsource (lib "") (part "Res2-0603_2"))
    )
    (comp (ref "R13")
      (value "10K")
      (footprint "R-0603")
      (description "0603")
      (fields (field (name "PUBLISHER") "Altium Limited"))
      (libsource (lib "") (part "Res2-0603_2"))
    )
    (comp (ref "R14")
      (value "0.1")
      (footprint "R-1206")
      (description "0603")
      (fields (field (name "PUBLISHER") "Altium Limited"))
      (libsource (lib "1电阻-V1.0") (part "Res2-0603"))
    )
    (comp (ref "R15")
      (value "15")
      (footprint "R-1206")
      (description "0603")
      (fields (field (name "PUBLISHER") "Altium Limited"))
      (libsource (lib "") (part "Res2-0603_1"))
    )
    (comp (ref "R16")
      (value "10K")
      (footprint "R-0603")
      (description "0603")
      (fields (field (name "PUBLISHER") "Altium Limited"))
      (libsource (lib "") (part "Res2-0603_2"))
    )
    (comp (ref "R17")
      (value "15")
      (footprint "R-1206")
      (description "0603")
      (fields (field (name "PUBLISHER") "Altium Limited"))
      (libsource (lib "") (part "Res2-0603_1"))
    )
    (comp (ref "R18")
      (value "4.99K")
      (footprint "R-0603")
      (description "0603")
      (fields (field (name "PUBLISHER") "Altium Limited"))
      (libsource (lib "") (part "Res2-0603_1"))
    )
    (comp (ref "R19")
      (value "1K")
      (footprint "R-0603")
      (description "0603")
      (fields (field (name "PUBLISHER") "Altium Limited"))
      (libsource (lib "") (part "Res2-0603_1"))
    )
    (comp (ref "R20")
      (value "10R")
      (footprint "R-0603")
      (description "0603")
      (fields (field (name "PUBLISHER") "Altium Limited"))
      (libsource (lib "") (part "Res2-0603_1"))
    )
    (comp (ref "R21")
      (value "15")
      (footprint "R-1206")
      (description "0603")
      (fields (field (name "PUBLISHER") "Altium Limited"))
      (libsource (lib "") (part "Res2-0603_1"))
    )
    (comp (ref "R22")
      (value "0")
      (footprint "R-1206")
      (description "0603")
      (fields (field (name "PUBLISHER") "Altium Limited"))
      (libsource (lib "1电阻-V1.0") (part "Res2-0603"))
    )
    (comp (ref "R23")
      (value "0")
      (footprint "R-1206")
      (description "0603")
      (fields (field (name "PUBLISHER") "Altium Limited"))
      (libsource (lib "1电阻-V1.0") (part "Res2-0603"))
    )
    (comp (ref "R24")
      (value "0")
      (footprint "R-1206")
      (description "0603")
      (fields (field (name "PUBLISHER") "Altium Limited"))
      (libsource (lib "1电阻-V1.0") (part "Res2-0603"))
    )
    (comp (ref "R25")
      (value "100")
      (footprint "R-1206")
      (description "0603")
      (fields (field (name "PUBLISHER") "Altium Limited"))
      (libsource (lib "1电阻-V1.0") (part "Res2-0603"))
    )
    (comp (ref "R26")
      (value "NC")
      (footprint "R-1206")
      (description "0603")
      (fields (field (name "PUBLISHER") "Altium Limited"))
      (libsource (lib "1电阻-V1.0") (part "Res2-0603"))
    )
    (comp (ref "R27")
      (value "100")
      (footprint "R-1206")
      (description "0603")
      (fields (field (name "PUBLISHER") "Altium Limited"))
      (libsource (lib "1电阻-V1.0") (part "Res2-0603"))
    )
    (comp (ref "R28")
      (value "NC")
      (footprint "R-1206")
      (description "0603")
      (fields (field (name "PUBLISHER") "Altium Limited"))
      (libsource (lib "1电阻-V1.0") (part "Res2-0603"))
    )
    (comp (ref "R29")
      (value "100")
      (footprint "R-1206")
      (description "0603")
      (fields (field (name "PUBLISHER") "Altium Limited"))
      (libsource (lib "1电阻-V1.0") (part "Res2-0603"))
    )
    (comp (ref "R30")
      (value "NC")
      (footprint "R-1206")
      (description "0603")
      (fields (field (name "PUBLISHER") "Altium Limited"))
      (libsource (lib "1电阻-V1.0") (part "Res2-0603"))
    )
    (comp (ref "R31")
      (value "10K")
      (footprint "R-0603")
      (description "0603")
      (fields (field (name "PUBLISHER") "Altium Limited"))
      (libsource (lib "") (part "Res2-0603_1"))
    )
    (comp (ref "R32")
      (value "15")
      (footprint "R-1206")
      (description "0603")
      (fields (field (name "PUBLISHER") "Altium Limited"))
      (libsource (lib "") (part "Res2-0603_1"))
    )
    (comp (ref "R33")
      (value "10K")
      (footprint "R-0603")
      (description "0603")
      (fields (field (name "PUBLISHER") "Altium Limited"))
      (libsource (lib "") (part "Res2-0603_1"))
    )
    (comp (ref "R34")
      (value "4.99K")
      (footprint "R-0603")
      (description "0603")
      (fields (field (name "PUBLISHER") "Altium Limited"))
      (libsource (lib "") (part "Res2-0603_1"))
    )
    (comp (ref "R35")
      (value "1K")
      (footprint "R-0603")
      (description "0603")
      (fields (field (name "PUBLISHER") "Altium Limited"))
      (libsource (lib "") (part "Res2-0603_1"))
    )
    (comp (ref "R36")
      (value "0")
      (footprint "R-1206")
      (description "0603")
      (fields (field (name "PUBLISHER") "Altium Limited"))
      (libsource (lib "1电阻-V1.0") (part "Res2-0603"))
    )
    (comp (ref "R37")
      (value "0")
      (footprint "R-1206")
      (description "0603")
      (fields (field (name "PUBLISHER") "Altium Limited"))
      (libsource (lib "1电阻-V1.0") (part "Res2-0603"))
    )
    (comp (ref "R38")
      (value "0")
      (footprint "R-1206")
      (description "0603")
      (fields (field (name "PUBLISHER") "Altium Limited"))
      (libsource (lib "1电阻-V1.0") (part "Res2-0603"))
    )
    (comp (ref "R39")
      (value "10R")
      (footprint "R-0603")
      (description "0603")
      (fields (field (name "PUBLISHER") "Altium Limited"))
      (libsource (lib "") (part "Res2-0603_1"))
    )
    (comp (ref "R40")
      (value "100")
      (footprint "R-1206")
      (description "0603")
      (fields (field (name "PUBLISHER") "Altium Limited"))
      (libsource (lib "1电阻-V1.0") (part "Res2-0603"))
    )
    (comp (ref "R41")
      (value "NC")
      (footprint "R-1206")
      (description "0603")
      (fields (field (name "PUBLISHER") "Altium Limited"))
      (libsource (lib "1电阻-V1.0") (part "Res2-0603"))
    )
    (comp (ref "R42")
      (value "100")
      (footprint "R-1206")
      (description "0603")
      (fields (field (name "PUBLISHER") "Altium Limited"))
      (libsource (lib "1电阻-V1.0") (part "Res2-0603"))
    )
    (comp (ref "R43")
      (value "NC")
      (footprint "R-1206")
      (description "0603")
      (fields (field (name "PUBLISHER") "Altium Limited"))
      (libsource (lib "1电阻-V1.0") (part "Res2-0603"))
    )
    (comp (ref "R44")
      (value "100")
      (footprint "R-1206")
      (description "0603")
      (fields (field (name "PUBLISHER") "Altium Limited"))
      (libsource (lib "1电阻-V1.0") (part "Res2-0603"))
    )
    (comp (ref "R45")
      (value "NC")
      (footprint "R-1206")
      (description "0603")
      (fields (field (name "PUBLISHER") "Altium Limited"))
      (libsource (lib "1电阻-V1.0") (part "Res2-0603"))
    )
    (comp (ref "R46")
      (value "15")
      (footprint "R-1206")
      (description "0603")
      (fields (field (name "PUBLISHER") "Altium Limited"))
      (libsource (lib "") (part "Res2-0603_1"))
    )
    (comp (ref "R47")
      (value "0")
      (footprint "R-1206")
      (description "0603")
      (fields (field (name "PUBLISHER") "Altium Limited"))
      (libsource (lib "1电阻-V1.0") (part "Res2-0603"))
    )
    (comp (ref "R48")
      (value "0")
      (footprint "R-1206")
      (description "0603")
      (fields (field (name "PUBLISHER") "Altium Limited"))
      (libsource (lib "1电阻-V1.0") (part "Res2-0603"))
    )
    (comp (ref "R49")
      (value "0")
      (footprint "R-1206")
      (description "0603")
      (fields (field (name "PUBLISHER") "Altium Limited"))
      (libsource (lib "1电阻-V1.0") (part "Res2-0603"))
    )
    (comp (ref "R50")
      (value "15")
      (footprint "R-1206")
      (description "0603")
      (fields (field (name "PUBLISHER") "Altium Limited"))
      (libsource (lib "") (part "Res2-0603_1"))
    )
    (comp (ref "R51")
      (value "100")
      (footprint "R-1206")
      (description "0603")
      (fields (field (name "PUBLISHER") "Altium Limited"))
      (libsource (lib "1电阻-V1.0") (part "Res2-0603"))
    )
    (comp (ref "R52")
      (value "NC")
      (footprint "R-1206")
      (description "0603")
      (fields (field (name "PUBLISHER") "Altium Limited"))
      (libsource (lib "1电阻-V1.0") (part "Res2-0603"))
    )
    (comp (ref "R53")
      (value "100")
      (footprint "R-1206")
      (description "0603")
      (fields (field (name "PUBLISHER") "Altium Limited"))
      (libsource (lib "1电阻-V1.0") (part "Res2-0603"))
    )
    (comp (ref "R54")
      (value "NC")
      (footprint "R-1206")
      (description "0603")
      (fields (field (name "PUBLISHER") "Altium Limited"))
      (libsource (lib "1电阻-V1.0") (part "Res2-0603"))
    )
    (comp (ref "R55")
      (value "100")
      (footprint "R-1206")
      (description "0603")
      (fields (field (name "PUBLISHER") "Altium Limited"))
      (libsource (lib "1电阻-V1.0") (part "Res2-0603"))
    )
    (comp (ref "R56")
      (value "NC")
      (footprint "R-1206")
      (description "0603")
      (fields (field (name "PUBLISHER") "Altium Limited"))
      (libsource (lib "1电阻-V1.0") (part "Res2-0603"))
    )
    (comp (ref "R57")
      (value "4.99K")
      (footprint "R-0603")
      (description "0603")
      (fields (field (name "PUBLISHER") "Altium Limited"))
      (libsource (lib "") (part "Res2-0603_1"))
    )
    (comp (ref "R58")
      (value "1K")
      (footprint "R-0603")
      (description "0603")
      (fields (field (name "PUBLISHER") "Altium Limited"))
      (libsource (lib "") (part "Res2-0603_1"))
    )
    (comp (ref "R59")
      (value "10R")
      (footprint "R-0603")
      (description "0603")
      (fields (field (name "PUBLISHER") "Altium Limited"))
      (libsource (lib "") (part "Res2-0603_1"))
    )
    (comp (ref "R60")
      (value "0")
      (footprint "R-1206")
      (description "0603")
      (fields (field (name "PUBLISHER") "Altium Limited"))
      (libsource (lib "1电阻-V1.0") (part "Res2-0603"))
    )
    (comp (ref "R61")
      (value "0")
      (footprint "R-1206")
      (description "0603")
      (fields (field (name "PUBLISHER") "Altium Limited"))
      (libsource (lib "1电阻-V1.0") (part "Res2-0603"))
    )
    (comp (ref "R62")
      (value "0")
      (footprint "R-1206")
      (description "0603")
      (fields (field (name "PUBLISHER") "Altium Limited"))
      (libsource (lib "1电阻-V1.0") (part "Res2-0603"))
    )
    (comp (ref "R63")
      (value "15")
      (footprint "R-1206")
      (description "0603")
      (fields (field (name "PUBLISHER") "Altium Limited"))
      (libsource (lib "") (part "Res2-0603_1"))
    )
    (comp (ref "R64")
      (value "100")
      (footprint "R-1206")
      (description "0603")
      (fields (field (name "PUBLISHER") "Altium Limited"))
      (libsource (lib "1电阻-V1.0") (part "Res2-0603"))
    )
    (comp (ref "R65")
      (value "NC")
      (footprint "R-1206")
      (description "0603")
      (fields (field (name "PUBLISHER") "Altium Limited"))
      (libsource (lib "1电阻-V1.0") (part "Res2-0603"))
    )
    (comp (ref "R66")
      (value "100")
      (footprint "R-1206")
      (description "0603")
      (fields (field (name "PUBLISHER") "Altium Limited"))
      (libsource (lib "1电阻-V1.0") (part "Res2-0603"))
    )
    (comp (ref "R67")
      (value "NC")
      (footprint "R-1206")
      (description "0603")
      (fields (field (name "PUBLISHER") "Altium Limited"))
      (libsource (lib "1电阻-V1.0") (part "Res2-0603"))
    )
    (comp (ref "R68")
      (value "100")
      (footprint "R-1206")
      (description "0603")
      (fields (field (name "PUBLISHER") "Altium Limited"))
      (libsource (lib "1电阻-V1.0") (part "Res2-0603"))
    )
    (comp (ref "R69")
      (value "NC")
      (footprint "R-1206")
      (description "0603")
      (fields (field (name "PUBLISHER") "Altium Limited"))
      (libsource (lib "1电阻-V1.0") (part "Res2-0603"))
    )
    (comp (ref "R70")
      (value "15")
      (footprint "R-1206")
      (description "0603")
      (fields (field (name "PUBLISHER") "Altium Limited"))
      (libsource (lib "") (part "Res2-0603_1"))
    )
    (comp (ref "R71")
      (value "4.99K")
      (footprint "R-0603")
      (description "0603")
      (fields (field (name "PUBLISHER") "Altium Limited"))
      (libsource (lib "") (part "Res2-0603_1"))
    )
    (comp (ref "R72")
      (value "1K")
      (footprint "R-0603")
      (description "0603")
      (fields (field (name "PUBLISHER") "Altium Limited"))
      (libsource (lib "") (part "Res2-0603_1"))
    )
    (comp (ref "R73")
      (value "0")
      (footprint "R-1206")
      (description "0603")
      (fields (field (name "PUBLISHER") "Altium Limited"))
      (libsource (lib "1电阻-V1.0") (part "Res2-0603"))
    )
    (comp (ref "R74")
      (value "0")
      (footprint "R-1206")
      (description "0603")
      (fields (field (name "PUBLISHER") "Altium Limited"))
      (libsource (lib "1电阻-V1.0") (part "Res2-0603"))
    )
    (comp (ref "R75")
      (value "0")
      (footprint "R-1206")
      (description "0603")
      (fields (field (name "PUBLISHER") "Altium Limited"))
      (libsource (lib "1电阻-V1.0") (part "Res2-0603"))
    )
    (comp (ref "R76")
      (value "10R")
      (footprint "R-0603")
      (description "0603")
      (fields (field (name "PUBLISHER") "Altium Limited"))
      (libsource (lib "") (part "Res2-0603_1"))
    )
    (comp (ref "R77")
      (value "100")
      (footprint "R-1206")
      (description "0603")
      (fields (field (name "PUBLISHER") "Altium Limited"))
      (libsource (lib "1电阻-V1.0") (part "Res2-0603"))
    )
    (comp (ref "R78")
      (value "NC")
      (footprint "R-1206")
      (description "0603")
      (fields (field (name "PUBLISHER") "Altium Limited"))
      (libsource (lib "1电阻-V1.0") (part "Res2-0603"))
    )
    (comp (ref "R79")
      (value "100")
      (footprint "R-1206")
      (description "0603")
      (fields (field (name "PUBLISHER") "Altium Limited"))
      (libsource (lib "1电阻-V1.0") (part "Res2-0603"))
    )
    (comp (ref "R80")
      (value "NC")
      (footprint "R-1206")
      (description "0603")
      (fields (field (name "PUBLISHER") "Altium Limited"))
      (libsource (lib "1电阻-V1.0") (part "Res2-0603"))
    )
    (comp (ref "R81")
      (value "100")
      (footprint "R-1206")
      (description "0603")
      (fields (field (name "PUBLISHER") "Altium Limited"))
      (libsource (lib "1电阻-V1.0") (part "Res2-0603"))
    )
    (comp (ref "R82")
      (value "NC")
      (footprint "R-1206")
      (description "0603")
      (fields (field (name "PUBLISHER") "Altium Limited"))
      (libsource (lib "1电阻-V1.0") (part "Res2-0603"))
    )
    (comp (ref "R83")
      (value "15")
      (footprint "R-1206")
      (description "0603")
      (fields (field (name "PUBLISHER") "Altium Limited"))
      (libsource (lib "") (part "Res2-0603_1"))
    )
    (comp (ref "R84")
      (value "0")
      (footprint "R-1206")
      (description "0603")
      (fields (field (name "PUBLISHER") "Altium Limited"))
      (libsource (lib "1电阻-V1.0") (part "Res2-0603"))
    )
    (comp (ref "R85")
      (value "0")
      (footprint "R-1206")
      (description "0603")
      (fields (field (name "PUBLISHER") "Altium Limited"))
      (libsource (lib "1电阻-V1.0") (part "Res2-0603"))
    )
    (comp (ref "R86")
      (value "0")
      (footprint "R-1206")
      (description "0603")
      (fields (field (name "PUBLISHER") "Altium Limited"))
      (libsource (lib "1电阻-V1.0") (part "Res2-0603"))
    )
    (comp (ref "R87")
      (value "15")
      (footprint "R-1206")
      (description "0603")
      (fields (field (name "PUBLISHER") "Altium Limited"))
      (libsource (lib "") (part "Res2-0603_1"))
    )
    (comp (ref "R88")
      (value "100")
      (footprint "R-1206")
      (description "0603")
      (fields (field (name "PUBLISHER") "Altium Limited"))
      (libsource (lib "1电阻-V1.0") (part "Res2-0603"))
    )
    (comp (ref "R89")
      (value "NC")
      (footprint "R-1206")
      (description "0603")
      (fields (field (name "PUBLISHER") "Altium Limited"))
      (libsource (lib "1电阻-V1.0") (part "Res2-0603"))
    )
    (comp (ref "R90")
      (value "100")
      (footprint "R-1206")
      (description "0603")
      (fields (field (name "PUBLISHER") "Altium Limited"))
      (libsource (lib "1电阻-V1.0") (part "Res2-0603"))
    )
    (comp (ref "R91")
      (value "NC")
      (footprint "R-1206")
      (description "0603")
      (fields (field (name "PUBLISHER") "Altium Limited"))
      (libsource (lib "1电阻-V1.0") (part "Res2-0603"))
    )
    (comp (ref "R92")
      (value "100")
      (footprint "R-1206")
      (description "0603")
      (fields (field (name "PUBLISHER") "Altium Limited"))
      (libsource (lib "1电阻-V1.0") (part "Res2-0603"))
    )
    (comp (ref "R93")
      (value "NC")
      (footprint "R-1206")
      (description "0603")
      (fields (field (name "PUBLISHER") "Altium Limited"))
      (libsource (lib "1电阻-V1.0") (part "Res2-0603"))
    )
    (comp (ref "R94")
      (value "4.99K")
      (footprint "R-0603")
      (description "0603")
      (fields (field (name "PUBLISHER") "Altium Limited"))
      (libsource (lib "") (part "Res2-0603_1"))
    )
    (comp (ref "R95")
      (value "1K")
      (footprint "R-0603")
      (description "0603")
      (fields (field (name "PUBLISHER") "Altium Limited"))
      (libsource (lib "") (part "Res2-0603_1"))
    )
    (comp (ref "R96")
      (value "10R")
      (footprint "R-0603")
      (description "0603")
      (fields (field (name "PUBLISHER") "Altium Limited"))
      (libsource (lib "") (part "Res2-0603_1"))
    )
    (comp (ref "R97")
      (value "0")
      (footprint "R-1206")
      (description "0603")
      (fields (field (name "PUBLISHER") "Altium Limited"))
      (libsource (lib "1电阻-V1.0") (part "Res2-0603"))
    )
    (comp (ref "R98")
      (value "0")
      (footprint "R-1206")
      (description "0603")
      (fields (field (name "PUBLISHER") "Altium Limited"))
      (libsource (lib "1电阻-V1.0") (part "Res2-0603"))
    )
    (comp (ref "R99")
      (value "0")
      (footprint "R-1206")
      (description "0603")
      (fields (field (name "PUBLISHER") "Altium Limited"))
      (libsource (lib "1电阻-V1.0") (part "Res2-0603"))
    )
    (comp (ref "R100")
      (value "15")
      (footprint "R-1206")
      (description "0603")
      (fields (field (name "PUBLISHER") "Altium Limited"))
      (libsource (lib "") (part "Res2-0603_1"))
    )
    (comp (ref "R101")
      (value "100")
      (footprint "R-1206")
      (description "0603")
      (fields (field (name "PUBLISHER") "Altium Limited"))
      (libsource (lib "1电阻-V1.0") (part "Res2-0603"))
    )
    (comp (ref "R102")
      (value "NC")
      (footprint "R-1206")
      (description "0603")
      (fields (field (name "PUBLISHER") "Altium Limited"))
      (libsource (lib "1电阻-V1.0") (part "Res2-0603"))
    )
    (comp (ref "R103")
      (value "100")
      (footprint "R-1206")
      (description "0603")
      (fields (field (name "PUBLISHER") "Altium Limited"))
      (libsource (lib "1电阻-V1.0") (part "Res2-0603"))
    )
    (comp (ref "R104")
      (value "NC")
      (footprint "R-1206")
      (description "0603")
      (fields (field (name "PUBLISHER") "Altium Limited"))
      (libsource (lib "1电阻-V1.0") (part "Res2-0603"))
    )
    (comp (ref "R105")
      (value "100")
      (footprint "R-1206")
      (description "0603")
      (fields (field (name "PUBLISHER") "Altium Limited"))
      (libsource (lib "1电阻-V1.0") (part "Res2-0603"))
    )
    (comp (ref "R106")
      (value "NC")
      (footprint "R-1206")
      (description "0603")
      (fields (field (name "PUBLISHER") "Altium Limited"))
      (libsource (lib "1电阻-V1.0") (part "Res2-0603"))
    )
    (comp (ref "R107")
      (value "15")
      (footprint "R-1206")
      (description "0603")
      (fields (field (name "PUBLISHER") "Altium Limited"))
      (libsource (lib "") (part "Res2-0603_1"))
    )
    (comp (ref "R108")
      (value "0")
      (footprint "R-1206")
      (description "0603")
      (fields (field (name "PUBLISHER") "Altium Limited"))
      (libsource (lib "1电阻-V1.0") (part "Res2-0603"))
    )
    (comp (ref "R109")
      (value "0")
      (footprint "R-1206")
      (description "0603")
      (fields (field (name "PUBLISHER") "Altium Limited"))
      (libsource (lib "1电阻-V1.0") (part "Res2-0603"))
    )
    (comp (ref "R110")
      (value "0")
      (footprint "R-1206")
      (description "0603")
      (fields (field (name "PUBLISHER") "Altium Limited"))
      (libsource (lib "1电阻-V1.0") (part "Res2-0603"))
    )
    (comp (ref "R111")
      (value "4.99K")
      (footprint "R-0603")
      (description "0603")
      (fields (field (name "PUBLISHER") "Altium Limited"))
      (libsource (lib "") (part "Res2-0603_1"))
    )
    (comp (ref "R112")
      (value "1K")
      (footprint "R-0603")
      (description "0603")
      (fields (field (name "PUBLISHER") "Altium Limited"))
      (libsource (lib "") (part "Res2-0603_1"))
    )
    (comp (ref "R113")
      (value "100")
      (footprint "R-1206")
      (description "0603")
      (fields (field (name "PUBLISHER") "Altium Limited"))
      (libsource (lib "1电阻-V1.0") (part "Res2-0603"))
    )
    (comp (ref "R114")
      (value "NC")
      (footprint "R-1206")
      (description "0603")
      (fields (field (name "PUBLISHER") "Altium Limited"))
      (libsource (lib "1电阻-V1.0") (part "Res2-0603"))
    )
    (comp (ref "R115")
      (value "100")
      (footprint "R-1206")
      (description "0603")
      (fields (field (name "PUBLISHER") "Altium Limited"))
      (libsource (lib "1电阻-V1.0") (part "Res2-0603"))
    )
    (comp (ref "R116")
      (value "NC")
      (footprint "R-1206")
      (description "0603")
      (fields (field (name "PUBLISHER") "Altium Limited"))
      (libsource (lib "1电阻-V1.0") (part "Res2-0603"))
    )
    (comp (ref "R117")
      (value "100")
      (footprint "R-1206")
      (description "0603")
      (fields (field (name "PUBLISHER") "Altium Limited"))
      (libsource (lib "1电阻-V1.0") (part "Res2-0603"))
    )
    (comp (ref "R118")
      (value "NC")
      (footprint "R-1206")
      (description "0603")
      (fields (field (name "PUBLISHER") "Altium Limited"))
      (libsource (lib "1电阻-V1.0") (part "Res2-0603"))
    )
    (comp (ref "R119")
      (value "10R")
      (footprint "R-0603")
      (description "0603")
      (fields (field (name "PUBLISHER") "Altium Limited"))
      (libsource (lib "") (part "Res2-0603_1"))
    )
    (comp (ref "R120")
      (value "15")
      (footprint "R-1206")
      (description "0603")
      (fields (field (name "PUBLISHER") "Altium Limited"))
      (libsource (lib "") (part "Res2-0603_1"))
    )
    (comp (ref "R121")
      (value "15")
      (footprint "R-1206")
      (description "0603")
      (fields (field (name "PUBLISHER") "Altium Limited"))
      (libsource (lib "") (part "Res2-0603_1"))
    )
    (comp (ref "R122")
      (value "4.99K")
      (footprint "R-0603")
      (description "0603")
      (fields (field (name "PUBLISHER") "Altium Limited"))
      (libsource (lib "") (part "Res2-0603_1"))
    )
    (comp (ref "R123")
      (value "1K")
      (footprint "R-0603")
      (description "0603")
      (fields (field (name "PUBLISHER") "Altium Limited"))
      (libsource (lib "") (part "Res2-0603_1"))
    )
    (comp (ref "R124")
      (value "10R")
      (footprint "R-0603")
      (description "0603")
      (fields (field (name "PUBLISHER") "Altium Limited"))
      (libsource (lib "") (part "Res2-0603_1"))
    )
    (comp (ref "R125")
      (value "15")
      (footprint "R-1206")
      (description "0603")
      (fields (field (name "PUBLISHER") "Altium Limited"))
      (libsource (lib "") (part "Res2-0603_1"))
    )
    (comp (ref "R126")
      (value "15")
      (footprint "R-1206")
      (description "0603")
      (fields (field (name "PUBLISHER") "Altium Limited"))
      (libsource (lib "") (part "Res2-0603_1"))
    )
    (comp (ref "R127")
      (value "4.99K")
      (footprint "R-0603")
      (description "0603")
      (fields (field (name "PUBLISHER") "Altium Limited"))
      (libsource (lib "") (part "Res2-0603_1"))
    )
    (comp (ref "R128")
      (value "1K")
      (footprint "R-0603")
      (description "0603")
      (fields (field (name "PUBLISHER") "Altium Limited"))
      (libsource (lib "") (part "Res2-0603_1"))
    )
    (comp (ref "R129")
      (value "10R")
      (footprint "R-0603")
      (description "0603")
      (fields (field (name "PUBLISHER") "Altium Limited"))
      (libsource (lib "") (part "Res2-0603_1"))
    )
    (comp (ref "S1") (value "EC11M") (footprint "EC11M") (libsource (lib "开关-V1") (part "EC11M")))
    (comp (ref "s10")
      (value "TS-007")
      (footprint "TS-007")
      (description "五向开关")
      (libsource (lib "开关-V1") (part "TS-007"))
    )
    (comp (ref "U1")
      (value "XL1509-5.0")
      (footprint "SOP-8-m")
      (description "开关电源 SOP-8")
      (libsource (lib "8集成电路-V1.1") (part "XL1509-ADJ"))
    )
    (comp (ref "U2")
      (value "ME6206A33M3G")
      (footprint "SOT-23")
      (description "LDO稳压 SOT-23")
      (libsource (lib "电源芯片-线性稳压-V1") (part "ME6206A33M3G"))
    )
    (comp (ref "U3")
      (value "78M12")
      (footprint "TO-252")
      (description "TO-252")
      (libsource (lib "电源芯片-线性稳压-V1") (part "78M05"))
    )
    (comp (ref "U4")
      (value "ME6206A33M3G")
      (footprint "SOT-23")
      (description "LDO稳压 SOT-23")
      (libsource (lib "电源芯片-线性稳压-V1") (part "ME6206A33M3G"))
    )
    (comp (ref "U5")
      (value "TL431")
      (footprint "SOT-23")
      (description "稳压芯片 SOT-23")
      (libsource (lib "8集成电路-V1.1") (part "TL431"))
    )
    (comp (ref "U6")
      (value "INA219AIDCNR")
      (footprint "SOT-23-8-N")
      (description "26V、双向、零漂移、低侧/高侧、I2C输出电流/功率监控器")
      (libsource (lib "8集成电路-V1.1") (part "INA219AIDCNR"))
    )
    (comp (ref "U7") (value "TLC7226IDW") (footprint "SOP-20") (libsource (lib "DAC-V1") (part "TLC7226IDW")))
    (comp (ref "U8")
      (value "XTR111AIDGQR")
      (footprint "MSOP-10(11)-M")
      (description "4-20ma输出")
      (libsource (lib "8集成电路-V1.1") (part "XTR111"))
    )
    (comp (ref "U9")
      (value "STM32F407VET6")
      (footprint "LQFP100")
      (libsource (lib "9单片机-V1.0") (part "STM32F407VET6"))
    )
    (comp (ref "U10")
      (value "XTR111AIDGQR")
      (footprint "MSOP-10(11)-M")
      (description "4-20ma输出")
      (libsource (lib "8集成电路-V1.1") (part "XTR111"))
    )
    (comp (ref "U11")
      (value "XTR111AIDGQR")
      (footprint "MSOP-10(11)-M")
      (description "4-20ma输出")
      (libsource (lib "8集成电路-V1.1") (part "XTR111"))
    )
    (comp (ref "U12")
      (value "XTR111AIDGQR")
      (footprint "MSOP-10(11)-M")
      (description "4-20ma输出")
      (libsource (lib "8集成电路-V1.1") (part "XTR111"))
    )
    (comp (ref "U13")
      (value "TJA1051T/3")
      (footprint "SOP-8-M")
      (libsource (lib "通讯-V1") (part "TJA1051T/3"))
    )
    (comp (ref "U14")
      (value "TLC7226IDW")
      (footprint "SOP-20")
      (libsource (lib "DAC-V1") (part "TLC7226IDW"))
    )
    (comp (ref "U15")
      (value "XTR111AIDGQR")
      (footprint "MSOP-10(11)-M")
      (description "4-20ma输出")
      (libsource (lib "8集成电路-V1.1") (part "XTR111"))
    )
    (comp (ref "U16") (value "ULN2001D") (footprint "SOP-8-M") (libsource (lib "电机驱动器V1") (part "ULN2001D")))
    (comp (ref "U18")
      (value "XTR111AIDGQR")
      (footprint "MSOP-10(11)-M")
      (description "4-20ma输出")
      (libsource (lib "8集成电路-V1.1") (part "XTR111"))
    )
    (comp (ref "U19")
      (value "XTR111AIDGQR")
      (footprint "MSOP-10(11)-M")
      (description "4-20ma输出")
      (libsource (lib "8集成电路-V1.1") (part "XTR111"))
    )
    (comp (ref "U20")
      (value "XTR111AIDGQR")
      (footprint "MSOP-10(11)-M")
      (description "4-20ma输出")
      (libsource (lib "8集成电路-V1.1") (part "XTR111"))
    )
    (comp (ref "Y1") (value "8M") (footprint "HC-49SMD") (libsource (lib "11其他元件-V1.0") (part "晶振")))
  )
  (nets
    (net (code "1") (name "/24V电源使能") (class "Default")
      (node (ref "U16") (pin "8") (pinfunction "1C_8") (pintype "passive"))
      (node (ref "U9") (pin "7") (pinfunction "PC13/EVENTOUT/RTC_AF1_7") (pintype "bidirectional"))
    )
    (net (code "2") (name "/A0") (class "Default")
      (node (ref "U7") (pin "17") (pinfunction "A0_17") (pintype "passive"))
      (node (ref "U9") (pin "60") (pinfunction "PD13/FSMC_A18/TIM4_CH2/EVENTOUT_60") (pintype "bidirectional"))
    )
    (net (code "3") (name "/A1") (class "Default")
      (node (ref "U7") (pin "16") (pinfunction "A1_16") (pintype "passive"))
      (node (ref "U9") (pin "64") (pinfunction "PC7/I2S3_MCK/TIM8_CH2/SDIO_D7/USART6_RX/DCMI_D1/TIM3_CH2/EVENTOUT_64") (pintype "bidirectional"))
    )
    (net (code "4") (name "/A3") (class "Default")
      (node (ref "U14") (pin "17") (pinfunction "A0_17") (pintype "passive"))
      (node (ref "U9") (pin "59") (pinfunction "PD12/FSMC_ALE/FSMC_A17/TIM4_CH1/USART3_RTS/EVENTOUT_59") (pintype "bidirectional"))
    )
    (net (code "5") (name "/A4") (class "Default")
      (node (ref "U14") (pin "16") (pinfunction "A1_16") (pintype "passive"))
      (node (ref "U9") (pin "63") (pinfunction "PC6/I2S2_MCK/TIM8_CH1/SDIO_D6/USART6_TX/DCMI_D0/TIM3_CH1/EVENTOUT_63") (pintype "bidirectional"))
    )
    (net (code "6") (name "/AO-电压输出使能") (class "Default")
      (node (ref "U16") (pin "6") (pinfunction "3C_6") (pintype "passive"))
      (node (ref "U9") (pin "9") (pinfunction "PC15-OSC32_OUT(PC15)/EVENTOUT/OSC32_OUT_9") (pintype "bidirectional"))
    )
    (net (code "7") (name "/AO-输出使能") (class "Default")
      (node (ref "U16") (pin "7") (pinfunction "2C_7") (pintype "passive"))
      (node (ref "U9") (pin "8") (pinfunction "PC14-OSC32_IN(PC14)/EVENTOUT/OSC32_IN_8") (pintype "bidirectional"))
    )
    (net (code "8") (name "/CAN-H") (class "Default")
      (node (ref "D6") (pin "2") (pinfunction "K_2") (pintype "passive"))
      (node (ref "P2") (pin "4") (pinfunction "4_4") (pintype "passive"))
      (node (ref "U13") (pin "7") (pinfunction "CANH_7") (pintype "passive"))
    )
    (net (code "9") (name "/CAN-L") (class "Default")
      (node (ref "D7") (pin "2") (pinfunction "K_2") (pintype "passive"))
      (node (ref "P2") (pin "2") (pinfunction "2_2") (pintype "passive"))
      (node (ref "U13") (pin "6") (pinfunction "CANL_6") (pintype "passive"))
    )
    (net (code "10") (name "/CAN-RXD") (class "Default")
      (node (ref "U13") (pin "4") (pinfunction "RXD_4") (pintype "passive"))
      (node (ref "U9") (pin "91") (pinfunction "PB5/I2C1_SMBA/CAN2_RX/OTG_HS_ULPI_D7/ETH_PPS_OUT/TIM3_CH2/SPI1_MOSI/SPI3_MOSI/DCMI_D10/I2S3_SD/EVENTOUT_91") (pintype "bidirectional"))
    )
    (net (code "11") (name "/CAN-TXD") (class "Default")
      (node (ref "U13") (pin "1") (pinfunction "TXD_1") (pintype "passive"))
      (node (ref "U9") (pin "92") (pinfunction "PB6/I2C1_SCL/TIM4_CH1/CAN2_TX/DCMI_D5/USART1_TX/EVENTOUT_92") (pintype "bidirectional"))
    )
    (net (code "12") (name "/CS") (class "Default")
      (node (ref "P7") (pin "7") (pinfunction "7_7") (pintype "passive"))
      (node (ref "U9") (pin "88") (pinfunction "PD7/USART2_CK/FSMC_NE1/FSMC_NCE2/EVENTOUT_88") (pintype "bidirectional"))
    )
    (net (code "13") (name "/D0") (class "Default")
      (node (ref "P7") (pin "11") (pinfunction "11_11") (pintype "passive"))
      (node (ref "U9") (pin "61") (pinfunction "PD14/FSMC_D0/TIM4_CH3/EVENTOUT/EVENTOUT_61") (pintype "bidirectional"))
    )
    (net (code "14") (name "/D1") (class "Default")
      (node (ref "P7") (pin "12") (pinfunction "12_12") (pintype "passive"))
      (node (ref "U9") (pin "62") (pinfunction "PD15/FSMC_D1/TIM4_CH4/EVENTOUT_62") (pintype "bidirectional"))
    )
    (net (code "15") (name "/D2") (class "Default")
      (node (ref "P7") (pin "13") (pinfunction "13_13") (pintype "passive"))
      (node (ref "U9") (pin "81") (pinfunction "PD0/FSMC_D2/CAN1_RX/EVENTOUT_81") (pintype "bidirectional"))
    )
    (net (code "16") (name "/D3") (class "Default")
      (node (ref "P7") (pin "14") (pinfunction "14_14") (pintype "passive"))
      (node (ref "U9") (pin "82") (pinfunction "PD1/FSMC_D3/CAN1_TX/EVENTOUT_82") (pintype "bidirectional"))
    )
    (net (code "17") (name "/D4") (class "Default")
      (node (ref "P7") (pin "15") (pinfunction "15_15") (pintype "passive"))
      (node (ref "U9") (pin "38") (pinfunction "PE7/FSMC_D4/TIM1_ETR/EVENTOUT_38") (pintype "bidirectional"))
    )
    (net (code "18") (name "/D5") (class "Default")
      (node (ref "P7") (pin "16") (pinfunction "16_16") (pintype "passive"))
      (node (ref "U9") (pin "39") (pinfunction "PE8/FSMC_D5/TIM1_CH1N/EVENTOUT_39") (pintype "bidirectional"))
    )
    (net (code "19") (name "/D6") (class "Default")
      (node (ref "P7") (pin "17") (pinfunction "17_17") (pintype "passive"))
      (node (ref "U9") (pin "40") (pinfunction "PE9/FSMC_D6/TIM1_CH1/EVENTOUT_40") (pintype "bidirectional"))
    )
    (net (code "20") (name "/D7") (class "Default")
      (node (ref "P7") (pin "18") (pinfunction "18_18") (pintype "passive"))
      (node (ref "U9") (pin "41") (pinfunction "PE10/FSMC_D7/TIM1_CH2N/EVENTOUT_41") (pintype "bidirectional"))
    )
    (net (code "21") (name "/D8") (class "Default")
      (node (ref "P7") (pin "19") (pinfunction "19_19") (pintype "passive"))
      (node (ref "U9") (pin "42") (pinfunction "PE11/FSMC_D8/TIM1_CH2/EVENTOUT_42") (pintype "bidirectional"))
    )
    (net (code "22") (name "/D9") (class "Default")
      (node (ref "P7") (pin "20") (pinfunction "20_20") (pintype "passive"))
      (node (ref "U9") (pin "43") (pinfunction "PE12/FSMC_D9/TIM1_CH3N/EVENTOUT_43") (pintype "bidirectional"))
    )
    (net (code "23") (name "/D10") (class "Default")
      (node (ref "P7") (pin "21") (pinfunction "21_21") (pintype "passive"))
      (node (ref "U9") (pin "44") (pinfunction "PE13/FSMC_D10/TIM1_CH3/EVENTOUT_44") (pintype "bidirectional"))
    )
    (net (code "24") (name "/D11") (class "Default")
      (node (ref "P7") (pin "22") (pinfunction "22_22") (pintype "passive"))
      (node (ref "U9") (pin "45") (pinfunction "PE14/FSMC_D11/TIM1_CH4/EVENTOUT_45") (pintype "bidirectional"))
    )
    (net (code "25") (name "/D12") (class "Default")
      (node (ref "P7") (pin "23") (pinfunction "23_23") (pintype "passive"))
      (node (ref "U9") (pin "46") (pinfunction "PE15/FSMC_D12/TIM1_BKIN/EVENTOUT_46") (pintype "bidirectional"))
    )
    (net (code "26") (name "/D13") (class "Default")
      (node (ref "P7") (pin "24") (pinfunction "24_24") (pintype "passive"))
      (node (ref "U9") (pin "55") (pinfunction "PD8/FSMC_D13/USART3_TX/EVENTOUT_55") (pintype "bidirectional"))
    )
    (net (code "27") (name "/D14") (class "Default")
      (node (ref "P7") (pin "25") (pinfunction "25_25") (pintype "passive"))
      (node (ref "U9") (pin "56") (pinfunction "PD9/FSMC_D14/USART3_RX/EVENTOUT_56") (pintype "bidirectional"))
    )
    (net (code "28") (name "/D15") (class "Default")
      (node (ref "P7") (pin "26") (pinfunction "26_26") (pintype "passive"))
      (node (ref "U9") (pin "57") (pinfunction "PD10/FSMC_D15/USART3_CK/EVENTOUT_57") (pintype "bidirectional"))
    )
    (net (code "29") (name "/DA1") (class "Default")
      (node (ref "U7") (pin "2") (pinfunction "OUTA_2") (pintype "passive"))
      (node (ref "U8") (pin "6") (pinfunction "VIN_6") (pintype "passive"))
    )
    (net (code "30") (name "/DA2") (class "Default")
      (node (ref "U10") (pin "6") (pinfunction "VIN_6") (pintype "passive"))
      (node (ref "U7") (pin "1") (pinfunction "OUTB_1") (pintype "passive"))
    )
    (net (code "31") (name "/DA3") (class "Default")
      (node (ref "U11") (pin "6") (pinfunction "VIN_6") (pintype "passive"))
      (node (ref "U7") (pin "20") (pinfunction "OUTC_20") (pintype "passive"))
    )
    (net (code "32") (name "/DA4") (class "Default")
      (node (ref "U12") (pin "6") (pinfunction "VIN_6") (pintype "passive"))
      (node (ref "U7") (pin "19") (pinfunction "OUTD_19") (pintype "passive"))
    )
    (net (code "33") (name "/DA5") (class "Default")
      (node (ref "U14") (pin "2") (pinfunction "OUTA_2") (pintype "passive"))
      (node (ref "U15") (pin "6") (pinfunction "VIN_6") (pintype "passive"))
    )
    (net (code "34") (name "/DA6") (class "Default")
      (node (ref "U14") (pin "1") (pinfunction "OUTB_1") (pintype "passive"))
      (node (ref "U18") (pin "6") (pinfunction "VIN_6") (pintype "passive"))
    )
    (net (code "35") (name "/DA7") (class "Default")
      (node (ref "U14") (pin "20") (pinfunction "OUTC_20") (pintype "passive"))
      (node (ref "U19") (pin "6") (pinfunction "VIN_6") (pintype "passive"))
    )
    (net (code "36") (name "/DA8") (class "Default")
      (node (ref "U14") (pin "19") (pinfunction "OUTD_19") (pintype "passive"))
      (node (ref "U20") (pin "6") (pinfunction "VIN_6") (pintype "passive"))
    )
    (net (code "37") (name "/DB0") (class "Default")
      (node (ref "U14") (pin "14") (pinfunction "DB0_14") (pintype "passive"))
      (node (ref "U7") (pin "14") (pinfunction "DB0_14") (pintype "passive"))
      (node (ref "U9") (pin "67") (pinfunction "PA8/MCO1/USART1_CK/TIM1_CH1/I2C3_SCL/OTG_FS_SOF/EVENTOUT_67") (pintype "bidirectional"))
    )
    (net (code "38") (name "/DB1") (class "Default")
      (node (ref "U14") (pin "13") (pinfunction "DB1_13") (pintype "passive"))
      (node (ref "U7") (pin "13") (pinfunction "DB1_13") (pintype "passive"))
      (node (ref "U9") (pin "68") (pinfunction "PA9/USART1_TX/TIM1_CH2/I2C3_SMBA/DCMI_D0/EVENTOUT/OTG_FS_VBUS_68") (pintype "bidirectional"))
    )
    (net (code "39") (name "/DB2") (class "Default")
      (node (ref "U14") (pin "12") (pinfunction "DB2_12") (pintype "passive"))
      (node (ref "U7") (pin "12") (pinfunction "DB2_12") (pintype "passive"))
      (node (ref "U9") (pin "69") (pinfunction "PA10/USART1_RX/TIM1_CH3/OTG_FS_ID/DCMI_D1/EVENTOUT_69") (pintype "bidirectional"))
    )
    (net (code "40") (name "/DB3") (class "Default")
      (node (ref "U14") (pin "11") (pinfunction "DB3_11") (pintype "passive"))
      (node (ref "U7") (pin "11") (pinfunction "DB3_11") (pintype "passive"))
      (node (ref "U9") (pin "89") (pinfunction "PB3(JTDO/TRACESWO)/JTDO/TRACESWO/SPI3_SCK/I2S3_CK/TIM2_CH2/SPI1_SCK/EVENTOUT_89") (pintype "bidirectional"))
    )
    (net (code "41") (name "/DB4") (class "Default")
      (node (ref "U14") (pin "10") (pinfunction "DB4_10") (pintype "passive"))
      (node (ref "U7") (pin "10") (pinfunction "DB4_10") (pintype "passive"))
      (node (ref "U9") (pin "90") (pinfunction "PB4(NJTRST)/NJTRST/SPI3_MISO/TIM3_CH1/SPI1_MISO/I2S3ext_SD/EVENTOUT_90") (pintype "bidirectional"))
    )
    (net (code "42") (name "/DB5") (class "Default")
      (node (ref "U14") (pin "9") (pinfunction "DB5_9") (pintype "passive"))
      (node (ref "U7") (pin "9") (pinfunction "DB5_9") (pintype "passive"))
      (node (ref "U9") (pin "1") (pinfunction "PE2/TRACECLK/FSMC_A23/ETH_MII_TXD3/EVENTOUT_1") (pintype "bidirectional"))
    )
    (net (code "43") (name "/DB6") (class "Default")
      (node (ref "U14") (pin "8") (pinfunction "DB6_8") (pintype "passive"))
      (node (ref "U7") (pin "8") (pinfunction "DB6_8") (pintype "passive"))
      (node (ref "U9") (pin "2") (pinfunction "PE3/TRACED0/FSMC_A19/EVENTOUT_2") (pintype "bidirectional"))
    )
    (net (code "44") (name "/DB7") (class "Default")
      (node (ref "U14") (pin "7") (pinfunction "DB7_7") (pintype "passive"))
      (node (ref "U7") (pin "7") (pinfunction "DB7_7") (pintype "passive"))
      (node (ref "U9") (pin "3") (pinfunction "PE4/TRACED1/FSMC_A20/DCMI_D4/EVENTOUT_3") (pintype "bidirectional"))
    )
    (net (code "45") (name "/NRST") (class "Default")
      (node (ref "C29") (pin "2") (pinfunction "2_2") (pintype "passive"))
      (node (ref "P4") (pin "5") (pinfunction "5_5") (pintype "passive"))
      (node (ref "U9") (pin "14") (pinfunction "NRST_14") (pintype "bidirectional"))
    )
    (net (code "46") (name "/NTC10K_25℃使能") (class "Default")
      (node (ref "Q11") (pin "1") (pinfunction "G_1") (pintype "passive"))
      (node (ref "Q16") (pin "1") (pinfunction "G_1") (pintype "passive"))
      (node (ref "Q21") (pin "1") (pinfunction "G_1") (pintype "passive"))
      (node (ref "Q24") (pin "1") (pinfunction "G_1") (pintype "passive"))
      (node (ref "Q29") (pin "1") (pinfunction "G_1") (pintype "passive"))
      (node (ref "Q33") (pin "1") (pinfunction "G_1") (pintype "passive"))
      (node (ref "Q37") (pin "1") (pinfunction "G_1") (pintype "passive"))
      (node (ref "Q8") (pin "1") (pinfunction "G_1") (pintype "passive"))
      (node (ref "U9") (pin "78") (pinfunction "PC10/SPI3_SCK/I2S3_CK/UART4_TX/SDIO_D2/DCMI_D8/USART3_TX/EVENTOUT_78") (pintype "bidirectional"))
    )
    (net (code "47") (name "/PE") (class "Default")
      (node (ref "P2") (pin "3") (pinfunction "3_3") (pintype "passive"))
      (node (ref "P3") (pin "9") (pinfunction "9_9") (pintype "passive"))
      (node (ref "P5") (pin "9") (pinfunction "9_9") (pintype "passive"))
    )
    (net (code "48") (name "/PT100_0℃使能") (class "Default")
      (node (ref "Q14") (pin "1") (pinfunction "G_1") (pintype "passive"))
      (node (ref "Q19") (pin "1") (pinfunction "G_1") (pintype "passive"))
      (node (ref "Q22") (pin "1") (pinfunction "G_1") (pintype "passive"))
      (node (ref "Q27") (pin "1") (pinfunction "G_1") (pintype "passive"))
      (node (ref "Q31") (pin "1") (pinfunction "G_1") (pintype "passive"))
      (node (ref "Q35") (pin "1") (pinfunction "G_1") (pintype "passive"))
      (node (ref "Q6") (pin "1") (pinfunction "G_1") (pintype "passive"))
      (node (ref "Q9") (pin "1") (pinfunction "G_1") (pintype "passive"))
      (node (ref "U9") (pin "80") (pinfunction "PC12/UART5_TX/SDIO_CK/DCMI_D9/SPI3_MOSI/I2S3_SD/USART3_CK/EVENTOUT_80") (pintype "bidirectional"))
    )
    (net (code "49") (name "/PT1000_0℃使能") (class "Default")
      (node (ref "Q10") (pin "1") (pinfunction "G_1") (pintype "passive"))
      (node (ref "Q15") (pin "1") (pinfunction "G_1") (pintype "passive"))
      (node (ref "Q20") (pin "1") (pinfunction "G_1") (pintype "passive"))
      (node (ref "Q23") (pin "1") (pinfunction "G_1") (pintype "passive"))
      (node (ref "Q28") (pin "1") (pinfunction "G_1") (pintype "passive"))
      (node (ref "Q32") (pin "1") (pinfunction "G_1") (pintype "passive"))
      (node (ref "Q36") (pin "1") (pinfunction "G_1") (pintype "passive"))
      (node (ref "Q7") (pin "1") (pinfunction "G_1") (pintype "passive"))
      (node (ref "U9") (pin "79") (pinfunction "PC11/UART4_RX/SPI3_MISO/SDIO_D3/DCMI_D4/USART3_RX/I2S3ext_SD/EVENTOUT_79") (pintype "bidirectional"))
    )
    (net (code "50") (name "/RD") (class "Default")
      (node (ref "P7") (pin "10") (pinfunction "10_10") (pintype "passive"))
      (node (ref "U9") (pin "85") (pinfunction "PD4/FSMC_NOE/USART2_RTS/EVENTOUT_85") (pintype "bidirectional"))
    )
    (net (code "51") (name "/RS") (class "Default")
      (node (ref "P7") (pin "8") (pinfunction "8_8") (pintype "passive"))
      (node (ref "U9") (pin "58") (pinfunction "PD11/FSMC_CLE/FSMC_A16/USART3_CTS/EVENTOUT_58") (pintype "bidirectional"))
    )
    (net (code "52") (name "/RST") (class "Default")
      (node (ref "P7") (pin "6") (pinfunction "6_6") (pintype "passive"))
      (node (ref "U9") (pin "35") (pinfunction "PB0/TIM3_CH3/TIM8_CH2N/OTG_HS_ULPI_D1/ETH_MII_RXD2/TIM1_CH2N/EVENTOUT/ADC12_IN8_35") (pintype "bidirectional"))
    )
    (net (code "53") (name "/SCL") (class "Default")
      (node (ref "R12") (pin "2") (pinfunction "2_2") (pintype "passive"))
      (node (ref "U6") (pin "5") (pinfunction "SCL_5") (pintype "passive"))
      (node (ref "U9") (pin "47") (pinfunction "PB10/SPI2_SCK/I2S2_CK/I2C2_SCL/USART3_TX/OTG_HS_ULPI_D3/ETH_MII_RX_ER/TIM2_CH3/EVENTOUT_47") (pintype "bidirectional"))
    )
    (net (code "54") (name "/SDA") (class "Default")
      (node (ref "R13") (pin "2") (pinfunction "2_2") (pintype "passive"))
      (node (ref "U6") (pin "6") (pinfunction "SDA_6") (pintype "passive"))
      (node (ref "U9") (pin "48") (pinfunction "PB11/I2C2_SDA/USART3_RX/OTG_HS_ULPI_D4/ETH_RMII_TX_EN/ETH_MII_TX_EN/TIM2_CH4/EVENTOUT_48") (pintype "bidirectional"))
    )
    (net (code "55") (name "/SWCLK") (class "Default")
      (node (ref "P4") (pin "2") (pinfunction "2_2") (pintype "passive"))
      (node (ref "U9") (pin "76") (pinfunction "PA14(JTCK-SWCLK)/JTCK-SWCLK/EVENTOUT_76") (pintype "bidirectional"))
    )
    (net (code "56") (name "/SWDIO") (class "Default")
      (node (ref "P4") (pin "4") (pinfunction "4_4") (pintype "passive"))
      (node (ref "U9") (pin "72") (pinfunction "PA13(JTMS-SWDIO)/JTMS-SWDIO/EVENTOUT_72") (pintype "bidirectional"))
    )
    (net (code "57") (name "/V-REF") (class "Default")
      (node (ref "C41") (pin "1") (pinfunction "1_1") (pintype "passive"))
      (node (ref "C42") (pin "2") (pinfunction "2_2") (pintype "passive"))
      (node (ref "C51") (pin "1") (pinfunction "1_1") (pintype "passive"))
      (node (ref "R5") (pin "1") (pinfunction "1_1") (pintype "passive"))
      (node (ref "R6") (pin "2") (pinfunction "2_2") (pintype "passive"))
      (node (ref "R7") (pin "1") (pinfunction "1_1") (pintype "passive"))
      (node (ref "R8") (pin "1") (pinfunction "1_1") (pintype "passive"))
      (node (ref "U14") (pin "4") (pinfunction "REF_4") (pintype "passive"))
      (node (ref "U5") (pin "2") (pinfunction "K_2") (pintype "passive"))
      (node (ref "U7") (pin "4") (pinfunction "REF_4") (pintype "passive"))
    )
    (net (code "58") (name "/WR") (class "Default")
      (node (ref "P7") (pin "9") (pinfunction "9_9") (pintype "passive"))
      (node (ref "U9") (pin "86") (pinfunction "PD5/FSMC_NWE/USART2_TX/EVENTOUT_86") (pintype "bidirectional"))
    )
    (net (code "59") (name "/WR1") (class "Default")
      (node (ref "U7") (pin "15") (pinfunction "~{WR}_15") (pintype "passive"))
      (node (ref "U9") (pin "66") (pinfunction "PC9/I2S_CKIN/MCO2/TIM8_CH4/SDIO_D1//I2C3_SDA/DCMI_D3/TIM3_CH4/EVENTOUT_66") (pintype "bidirectional"))
    )
    (net (code "60") (name "/WR2") (class "Default")
      (node (ref "U14") (pin "15") (pinfunction "~{WR}_15") (pintype "passive"))
      (node (ref "U9") (pin "65") (pinfunction "PC8/TIM8_CH3/SDIO_D0/TIM3_CH3/USART6_CK/DCMI_D2/EVENTOUT_65") (pintype "bidirectional"))
    )
    (net (code "61") (name "/五向开关-上") (class "Default")
      (node (ref "U9") (pin "33") (pinfunction "PC4/ETH_RMII_RX_D0/ETH_MII_RX_D0/EVENTOUT/ADC12_IN14_33") (pintype "bidirectional"))
      (node (ref "s10") (pin "6") (pinfunction "上_6") (pintype "passive"))
    )
    (net (code "62") (name "/五向开关-下") (class "Default")
      (node (ref "U9") (pin "30") (pinfunction "PA5/SPI1_SCK/OTG_HS_ULPI_CK/TIM2_CH1_ETR/TIM8_CHIN/EVENTOUT/ADC12_IN5/DAC2_OUT_30") (pintype "bidirectional"))
      (node (ref "s10") (pin "4") (pinfunction "下_4") (pintype "passive"))
    )
    (net (code "63") (name "/五向开关-中") (class "Default")
      (node (ref "U9") (pin "29") (pinfunction "PA4/SPI1_NSS/SPI3_NSS/USART2_CK/DCMI_HSYNC/OTG_HS_SOF/I2S3_WS/EVENTOUT/ADC12_IN4/DAC1_OUT_29") (pintype "bidirectional"))
      (node (ref "s10") (pin "3") (pinfunction "中_3") (pintype "passive"))
    )
    (net (code "64") (name "/五向开关-右") (class "Default")
      (node (ref "U9") (pin "31") (pinfunction "PA6/SPI1_MISO/TIM8_BKIN/TIM13_CH1/DCMI_PIXCLK/TIM3_CH1/TIM1_BKIN/EVENTOUT/ADC12_IN6_31") (pintype "bidirectional"))
      (node (ref "s10") (pin "5") (pinfunction "右_5") (pintype "passive"))
    )
    (net (code "65") (name "/五向开关-左") (class "Default")
      (node (ref "U9") (pin "32") (pinfunction "PA7/SPI1_MOSI/TIM8_CH1N/TIM14_CH1/TIM3_CH2/ETH_MII_RX_DV/TIM1_CH1N/RMII_CRS_DV/EVENTOUT/ADC12_IN7_32") (pintype "bidirectional"))
      (node (ref "s10") (pin "2") (pinfunction "左_2") (pintype "passive"))
    )
    (net (code "66") (name "/编码器-按键") (class "Default")
      (node (ref "S1") (pin "4") (pinfunction "4_4") (pintype "passive"))
      (node (ref "U9") (pin "23") (pinfunction "PA0-WKUP(PA0)/USART2_CTS/UART4_TX/ETH_MII_CRS/TIM2_CH1_ETR/TIM5_CH1/TIM8_ETR/EVENTOUT/ADC123_IN0/WKUP_23") (pintype "bidirectional"))
    )
    (net (code "67") (name "/编码器A") (class "Default")
      (node (ref "S1") (pin "2") (pinfunction "2_2") (pintype "passive"))
      (node (ref "U9") (pin "25") (pinfunction "PA2/USART2_TX/TIM5_CH3/TIM9_CH1/TIM2_CH3/ETH_MDIO/EVENTOUT/ADC123_IN2_25") (pintype "bidirectional"))
    )
    (net (code "68") (name "/编码器B") (class "Default")
      (node (ref "S1") (pin "3") (pinfunction "3_3") (pintype "passive"))
      (node (ref "U9") (pin "24") (pinfunction "PA1/USART2_RTS/UART4_RX/ETH_RMII_REF_CLK/ETH_MII_RX_CLK/TIM5_CH2/TIM2_CH2/EVENTOUT/ADC123_IN1_24") (pintype "bidirectional"))
    )
    (net (code "69") (name "/背光使能") (class "Default")
      (node (ref "P7") (pin "5") (pinfunction "5_5") (pintype "passive"))
      (node (ref "U9") (pin "34") (pinfunction "PC5/ETH_RMII_RX_D1/ETH_MII_RX_D1/EVENTOUT/ADC12_IN15_34") (pintype "bidirectional"))
    )
    (net (code "70") (name "/蜂鸣器") (class "Default")
      (node (ref "Q42") (pin "1") (pinfunction "G_1") (pintype "passive"))
      (node (ref "U9") (pin "53") (pinfunction "PB14/SPI2_MISO/TIM1_CH2N/TIM12_CH1/OTG_HS_DM/USART3_RTS/TIM8_CH2N/I2S2ext_SD/EVENTOUT_53") (pintype "bidirectional"))
    )
    (net (code "71") (name "/通道1") (class "Default")
      (node (ref "K2") (pin "4") (pinfunction "4_4") (pintype "passive"))
      (node (ref "P3") (pin "1") (pinfunction "1_1") (pintype "passive"))
      (node (ref "R22") (pin "2") (pinfunction "2_2") (pintype "passive"))
      (node (ref "R23") (pin "2") (pinfunction "2_2") (pintype "passive"))
      (node (ref "R24") (pin "2") (pinfunction "2_2") (pintype "passive"))
    )
    (net (code "72") (name "/通道2") (class "Default")
      (node (ref "K4") (pin "4") (pinfunction "4_4") (pintype "passive"))
      (node (ref "P3") (pin "3") (pinfunction "3_3") (pintype "passive"))
      (node (ref "R36") (pin "2") (pinfunction "2_2") (pintype "passive"))
      (node (ref "R37") (pin "2") (pinfunction "2_2") (pintype "passive"))
      (node (ref "R38") (pin "2") (pinfunction "2_2") (pintype "passive"))
    )
    (net (code "73") (name "/通道3") (class "Default")
      (node (ref "K6") (pin "4") (pinfunction "4_4") (pintype "passive"))
      (node (ref "P3") (pin "5") (pinfunction "5_5") (pintype "passive"))
      (node (ref "R47") (pin "2") (pinfunction "2_2") (pintype "passive"))
      (node (ref "R48") (pin "2") (pinfunction "2_2") (pintype "passive"))
      (node (ref "R49") (pin "2") (pinfunction "2_2") (pintype "passive"))
    )
    (net (code "74") (name "/通道4") (class "Default")
      (node (ref "K8") (pin "4") (pinfunction "4_4") (pintype "passive"))
      (node (ref "P3") (pin "7") (pinfunction "7_7") (pintype "passive"))
      (node (ref "R60") (pin "2") (pinfunction "2_2") (pintype "passive"))
      (node (ref "R61") (pin "2") (pinfunction "2_2") (pintype "passive"))
      (node (ref "R62") (pin "2") (pinfunction "2_2") (pintype "passive"))
    )
    (net (code "75") (name "/通道5") (class "Default")
      (node (ref "K10") (pin "4") (pinfunction "4_4") (pintype "passive"))
      (node (ref "P5") (pin "1") (pinfunction "1_1") (pintype "passive"))
      (node (ref "R73") (pin "2") (pinfunction "2_2") (pintype "passive"))
      (node (ref "R74") (pin "2") (pinfunction "2_2") (pintype "passive"))
      (node (ref "R75") (pin "2") (pinfunction "2_2") (pintype "passive"))
    )
    (net (code "76") (name "/通道6") (class "Default")
      (node (ref "K12") (pin "4") (pinfunction "4_4") (pintype "passive"))
      (node (ref "P5") (pin "3") (pinfunction "3_3") (pintype "passive"))
      (node (ref "R84") (pin "2") (pinfunction "2_2") (pintype "passive"))
      (node (ref "R85") (pin "2") (pinfunction "2_2") (pintype "passive"))
      (node (ref "R86") (pin "2") (pinfunction "2_2") (pintype "passive"))
    )
    (net (code "77") (name "/通道7") (class "Default")
      (node (ref "K14") (pin "4") (pinfunction "4_4") (pintype "passive"))
      (node (ref "P5") (pin "5") (pinfunction "5_5") (pintype "passive"))
      (node (ref "R97") (pin "2") (pinfunction "2_2") (pintype "passive"))
      (node (ref "R98") (pin "2") (pinfunction "2_2") (pintype "passive"))
      (node (ref "R99") (pin "2") (pinfunction "2_2") (pintype "passive"))
    )
    (net (code "78") (name "/通道8") (class "Default")
      (node (ref "K16") (pin "4") (pinfunction "4_4") (pintype "passive"))
      (node (ref "P5") (pin "7") (pinfunction "7_7") (pintype "passive"))
      (node (ref "R108") (pin "2") (pinfunction "2_2") (pintype "passive"))
      (node (ref "R109") (pin "2") (pinfunction "2_2") (pintype "passive"))
      (node (ref "R110") (pin "2") (pinfunction "2_2") (pintype "passive"))
    )
    (net (code "79") (name "3.3V") (class "Default")
      (node (ref "C10") (pin "2") (pinfunction "2_2") (pintype "passive"))
      (node (ref "C11") (pin "2") (pinfunction "2_2") (pintype "passive"))
      (node (ref "C17") (pin "2") (pinfunction "2_2") (pintype "passive"))
      (node (ref "C45") (pin "2") (pinfunction "2_2") (pintype "passive"))
      (node (ref "C46") (pin "2") (pinfunction "2_2") (pintype "passive"))
      (node (ref "C47") (pin "2") (pinfunction "2_2") (pintype "passive"))
      (node (ref "C48") (pin "2") (pinfunction "2_2") (pintype "passive"))
      (node (ref "C49") (pin "2") (pinfunction "2_2") (pintype "passive"))
      (node (ref "C6") (pin "1") (pinfunction "1_1") (pintype "passive"))
      (node (ref "C7") (pin "1") (pinfunction "1_1") (pintype "passive"))
      (node (ref "C9") (pin "2") (pinfunction "2_2") (pintype "passive"))
      (node (ref "P4") (pin "1") (pinfunction "1_1") (pintype "passive"))
      (node (ref "P7") (pin "1") (pinfunction "1_1") (pintype "passive"))
      (node (ref "P7") (pin "2") (pinfunction "2_2") (pintype "passive"))
      (node (ref "R12") (pin "1") (pinfunction "1_1") (pintype "passive"))
      (node (ref "R13") (pin "1") (pinfunction "1_1") (pintype "passive"))
      (node (ref "U13") (pin "5") (pinfunction "Vio_5") (pintype "passive"))
      (node (ref "U2") (pin "2") (pinfunction "VOUT_2") (pintype "passive"))
      (node (ref "U6") (pin "4") (pinfunction "VS_4") (pintype "passive"))
      (node (ref "U9") (pin "100") (pinfunction "VDD_100") (pintype "power_in"))
      (node (ref "U9") (pin "11") (pinfunction "VDD_11") (pintype "power_in"))
      (node (ref "U9") (pin "19") (pinfunction "VDD_19") (pintype "power_in"))
      (node (ref "U9") (pin "28") (pinfunction "VDD_28") (pintype "power_in"))
      (node (ref "U9") (pin "50") (pinfunction "VDD_50") (pintype "power_in"))
      (node (ref "U9") (pin "6") (pinfunction "VBAT_6") (pintype "power_in"))
      (node (ref "U9") (pin "75") (pinfunction "VDD_75") (pintype "power_in"))
    )
    (net (code "80") (name "5V") (class "Default")
      (node (ref "C1") (pin "2") (pinfunction "2_2") (pintype "passive"))
      (node (ref "C18") (pin "2") (pinfunction "2_2") (pintype "passive"))
      (node (ref "C4") (pin "1") (pinfunction "1_1") (pintype "passive"))
      (node (ref "C5") (pin "2") (pinfunction "2_2") (pintype "passive"))
      (node (ref "C8") (pin "2") (pinfunction "2_2") (pintype "passive"))
      (node (ref "D3") (pin "2") (pinfunction "K_2") (pintype "passive"))
      (node (ref "I1") (pin "2") (pinfunction "2_2") (pintype "passive"))
      (node (ref "L2") (pin "2") (pinfunction "2_2") (pintype "passive"))
      (node (ref "LS1") (pin "1") (pinfunction "A_1") (pintype "passive"))
      (node (ref "U1") (pin "3") (pinfunction "FEEDBACK_3") (pintype "passive"))
      (node (ref "U13") (pin "3") (pinfunction "VCC_3") (pintype "passive"))
      (node (ref "U2") (pin "3") (pinfunction "VIN_3") (pintype "passive"))
    )
    (net (code "81") (name "24V") (class "Default")
      (node (ref "C2") (pin "1") (pinfunction "1_1") (pintype "passive"))
      (node (ref "C3") (pin "2") (pinfunction "2_2") (pintype "passive"))
      (node (ref "D1") (pin "2") (pinfunction "K_2") (pintype "passive"))
      (node (ref "D2") (pin "2") (pinfunction "K_2") (pintype "passive"))
      (node (ref "I2") (pin "1") (pinfunction "1_1") (pintype "passive"))
      (node (ref "K1") (pin "2") (pinfunction "2_2") (pintype "passive"))
      (node (ref "K10") (pin "2") (pinfunction "2_2") (pintype "passive"))
      (node (ref "K11") (pin "2") (pinfunction "2_2") (pintype "passive"))
      (node (ref "K12") (pin "2") (pinfunction "2_2") (pintype "passive"))
      (node (ref "K13") (pin "2") (pinfunction "2_2") (pintype "passive"))
      (node (ref "K14") (pin "2") (pinfunction "2_2") (pintype "passive"))
      (node (ref "K15") (pin "2") (pinfunction "2_2") (pintype "passive"))
      (node (ref "K16") (pin "2") (pinfunction "2_2") (pintype "passive"))
      (node (ref "K17") (pin "2") (pinfunction "2_2") (pintype "passive"))
      (node (ref "K2") (pin "2") (pinfunction "2_2") (pintype "passive"))
      (node (ref "K3") (pin "2") (pinfunction "2_2") (pintype "passive"))
      (node (ref "K4") (pin "2") (pinfunction "2_2") (pintype "passive"))
      (node (ref "K5") (pin "2") (pinfunction "2_2") (pintype "passive"))
      (node (ref "K6") (pin "2") (pinfunction "2_2") (pintype "passive"))
      (node (ref "K7") (pin "2") (pinfunction "2_2") (pintype "passive"))
      (node (ref "K8") (pin "2") (pinfunction "2_2") (pintype "passive"))
      (node (ref "K9") (pin "2") (pinfunction "2_2") (pintype "passive"))
      (node (ref "R14") (pin "2") (pinfunction "2_2") (pintype "passive"))
      (node (ref "U1") (pin "1") (pinfunction "VIN_1") (pintype "passive"))
      (node (ref "U16") (pin "5") (pinfunction "COM_5") (pintype "passive"))
      (node (ref "U6") (pin "1") (pinfunction "IN+_1") (pintype "passive"))
    )
    (net (code "82") (name "A3.3V") (class "Default")
      (node (ref "C19") (pin "2") (pinfunction "2_2") (pintype "passive"))
      (node (ref "C43") (pin "1") (pinfunction "1_1") (pintype "passive"))
      (node (ref "C50") (pin "1") (pinfunction "1_1") (pintype "passive"))
      (node (ref "U4") (pin "2") (pinfunction "VOUT_2") (pintype "passive"))
      (node (ref "U9") (pin "21") (pinfunction "VREF+_21") (pintype "power_in"))
      (node (ref "U9") (pin "22") (pinfunction "VDDA_22") (pintype "power_in"))
    )
    (net (code "83") (name "A12V") (class "Default")
      (node (ref "C13") (pin "1") (pinfunction "1_1") (pintype "passive"))
      (node (ref "C15") (pin "2") (pinfunction "2_2") (pintype "passive"))
      (node (ref "C52") (pin "1") (pinfunction "1_1") (pintype "passive"))
      (node (ref "U14") (pin "18") (pinfunction "VDD_18") (pintype "passive"))
      (node (ref "U3") (pin "3") (pinfunction "OUT_3") (pintype "passive"))
      (node (ref "U7") (pin "18") (pinfunction "VDD_18") (pintype "passive"))
    )
    (net (code "84") (name "A24V") (class "Default")
      (node (ref "C12") (pin "1") (pinfunction "1_1") (pintype "passive"))
      (node (ref "C14") (pin "2") (pinfunction "2_2") (pintype "passive"))
      (node (ref "C20") (pin "2") (pinfunction "2_2") (pintype "passive"))
      (node (ref "C22") (pin "2") (pinfunction "2_2") (pintype "passive"))
      (node (ref "C28") (pin "2") (pinfunction "2_2") (pintype "passive"))
      (node (ref "C31") (pin "2") (pinfunction "2_2") (pintype "passive"))
      (node (ref "C33") (pin "2") (pinfunction "2_2") (pintype "passive"))
      (node (ref "C35") (pin "2") (pinfunction "2_2") (pintype "passive"))
      (node (ref "C37") (pin "2") (pinfunction "2_2") (pintype "passive"))
      (node (ref "C39") (pin "2") (pinfunction "2_2") (pintype "passive"))
      (node (ref "I2") (pin "2") (pinfunction "2_2") (pintype "passive"))
      (node (ref "R5") (pin "2") (pinfunction "2_2") (pintype "passive"))
      (node (ref "R7") (pin "2") (pinfunction "2_2") (pintype "passive"))
      (node (ref "R8") (pin "2") (pinfunction "2_2") (pintype "passive"))
      (node (ref "U10") (pin "1") (pinfunction "VSP_1") (pintype "passive"))
      (node (ref "U11") (pin "1") (pinfunction "VSP_1") (pintype "passive"))
      (node (ref "U12") (pin "1") (pinfunction "VSP_1") (pintype "passive"))
      (node (ref "U15") (pin "1") (pinfunction "VSP_1") (pintype "passive"))
      (node (ref "U18") (pin "1") (pinfunction "VSP_1") (pintype "passive"))
      (node (ref "U19") (pin "1") (pinfunction "VSP_1") (pintype "passive"))
      (node (ref "U20") (pin "1") (pinfunction "VSP_1") (pintype "passive"))
      (node (ref "U3") (pin "1") (pinfunction "IN_1") (pintype "passive"))
      (node (ref "U8") (pin "1") (pinfunction "VSP_1") (pintype "passive"))
    )
    (net (code "85") (name "AGND") (class "Default")
      (node (ref "C12") (pin "2") (pinfunction "2_2") (pintype "passive"))
      (node (ref "C13") (pin "2") (pinfunction "2_2") (pintype "passive"))
      (node (ref "C14") (pin "1") (pinfunction "1_1") (pintype "passive"))
      (node (ref "C15") (pin "1") (pinfunction "1_1") (pintype "passive"))
      (node (ref "C16") (pin "1") (pinfunction "1_1") (pintype "passive"))
      (node (ref "C19") (pin "1") (pinfunction "1_1") (pintype "passive"))
      (node (ref "C20") (pin "1") (pinfunction "1_1") (pintype "passive"))
      (node (ref "C21") (pin "2") (pinfunction "2_2") (pintype "passive"))
      (node (ref "C22") (pin "1") (pinfunction "1_1") (pintype "passive"))
      (node (ref "C25") (pin "2") (pinfunction "2_2") (pintype "passive"))
      (node (ref "C28") (pin "1") (pinfunction "1_1") (pintype "passive"))
      (node (ref "C30") (pin "2") (pinfunction "2_2") (pintype "passive"))
      (node (ref "C31") (pin "1") (pinfunction "1_1") (pintype "passive"))
      (node (ref "C32") (pin "2") (pinfunction "2_2") (pintype "passive"))
      (node (ref "C33") (pin "1") (pinfunction "1_1") (pintype "passive"))
      (node (ref "C34") (pin "2") (pinfunction "2_2") (pintype "passive"))
      (node (ref "C35") (pin "1") (pinfunction "1_1") (pintype "passive"))
      (node (ref "C36") (pin "2") (pinfunction "2_2") (pintype "passive"))
      (node (ref "C37") (pin "1") (pinfunction "1_1") (pintype "passive"))
      (node (ref "C38") (pin "2") (pinfunction "2_2") (pintype "passive"))
      (node (ref "C39") (pin "1") (pinfunction "1_1") (pintype "passive"))
      (node (ref "C40") (pin "2") (pinfunction "2_2") (pintype "passive"))
      (node (ref "C41") (pin "2") (pinfunction "2_2") (pintype "passive"))
      (node (ref "C42") (pin "1") (pinfunction "1_1") (pintype "passive"))
      (node (ref "C43") (pin "2") (pinfunction "2_2") (pintype "passive"))
      (node (ref "C44") (pin "2") (pinfunction "2_2") (pintype "passive"))
      (node (ref "C50") (pin "2") (pinfunction "2_2") (pintype "passive"))
      (node (ref "C51") (pin "2") (pinfunction "2_2") (pintype "passive"))
      (node (ref "C52") (pin "2") (pinfunction "2_2") (pintype "passive"))
      (node (ref "P3") (pin "2") (pinfunction "2_2") (pintype "passive"))
      (node (ref "P3") (pin "4") (pinfunction "4_4") (pintype "passive"))
      (node (ref "P3") (pin "6") (pinfunction "6_6") (pintype "passive"))
      (node (ref "P3") (pin "8") (pinfunction "8_8") (pintype "passive"))
      (node (ref "P5") (pin "2") (pinfunction "2_2") (pintype "passive"))
      (node (ref "P5") (pin "4") (pinfunction "4_4") (pintype "passive"))
      (node (ref "P5") (pin "6") (pinfunction "6_6") (pintype "passive"))
      (node (ref "P5") (pin "8") (pinfunction "8_8") (pintype "passive"))
      (node (ref "Q10") (pin "2") (pinfunction "S_2") (pintype "passive"))
      (node (ref "Q11") (pin "2") (pinfunction "S_2") (pintype "passive"))
      (node (ref "Q14") (pin "2") (pinfunction "S_2") (pintype "passive"))
      (node (ref "Q15") (pin "2") (pinfunction "S_2") (pintype "passive"))
      (node (ref "Q16") (pin "2") (pinfunction "S_2") (pintype "passive"))
      (node (ref "Q19") (pin "2") (pinfunction "S_2") (pintype "passive"))
      (node (ref "Q20") (pin "2") (pinfunction "S_2") (pintype "passive"))
      (node (ref "Q21") (pin "2") (pinfunction "S_2") (pintype "passive"))
      (node (ref "Q22") (pin "2") (pinfunction "S_2") (pintype "passive"))
      (node (ref "Q23") (pin "2") (pinfunction "S_2") (pintype "passive"))
      (node (ref "Q24") (pin "2") (pinfunction "S_2") (pintype "passive"))
      (node (ref "Q27") (pin "2") (pinfunction "S_2") (pintype "passive"))
      (node (ref "Q28") (pin "2") (pinfunction "S_2") (pintype "passive"))
      (node (ref "Q29") (pin "2") (pinfunction "S_2") (pintype "passive"))
      (node (ref "Q31") (pin "2") (pinfunction "S_2") (pintype "passive"))
      (node (ref "Q32") (pin "2") (pinfunction "S_2") (pintype "passive"))
      (node (ref "Q33") (pin "2") (pinfunction "S_2") (pintype "passive"))
      (node (ref "Q35") (pin "2") (pinfunction "S_2") (pintype "passive"))
      (node (ref "Q36") (pin "2") (pinfunction "S_2") (pintype "passive"))
      (node (ref "Q37") (pin "2") (pinfunction "S_2") (pintype "passive"))
      (node (ref "Q6") (pin "2") (pinfunction "S_2") (pintype "passive"))
      (node (ref "Q7") (pin "2") (pinfunction "S_2") (pintype "passive"))
      (node (ref "Q8") (pin "2") (pinfunction "S_2") (pintype "passive"))
      (node (ref "Q9") (pin "2") (pinfunction "S_2") (pintype "passive"))
      (node (ref "R11") (pin "1") (pinfunction "1_1") (pintype "passive"))
      (node (ref "R112") (pin "2") (pinfunction "2_2") (pintype "passive"))
      (node (ref "R119") (pin "2") (pinfunction "2_2") (pintype "passive"))
      (node (ref "R123") (pin "2") (pinfunction "2_2") (pintype "passive"))
      (node (ref "R124") (pin "2") (pinfunction "2_2") (pintype "passive"))
      (node (ref "R128") (pin "2") (pinfunction "2_2") (pintype "passive"))
      (node (ref "R129") (pin "2") (pinfunction "2_2") (pintype "passive"))
      (node (ref "R19") (pin "2") (pinfunction "2_2") (pintype "passive"))
      (node (ref "R20") (pin "2") (pinfunction "2_2") (pintype "passive"))
      (node (ref "R35") (pin "2") (pinfunction "2_2") (pintype "passive"))
      (node (ref "R39") (pin "2") (pinfunction "2_2") (pintype "passive"))
      (node (ref "R58") (pin "2") (pinfunction "2_2") (pintype "passive"))
      (node (ref "R59") (pin "2") (pinfunction "2_2") (pintype "passive"))
      (node (ref "R72") (pin "2") (pinfunction "2_2") (pintype "passive"))
      (node (ref "R76") (pin "2") (pinfunction "2_2") (pintype "passive"))
      (node (ref "R95") (pin "2") (pinfunction "2_2") (pintype "passive"))
      (node (ref "R96") (pin "2") (pinfunction "2_2") (pintype "passive"))
      (node (ref "U10") (pin "10") (pinfunction "GND_10") (pintype "passive"))
      (node (ref "U10") (pin "11") (pinfunction "GND(PAD)_11") (pintype "passive"))
      (node (ref "U11") (pin "10") (pinfunction "GND_10") (pintype "passive"))
      (node (ref "U11") (pin "11") (pinfunction "GND(PAD)_11") (pintype "passive"))
      (node (ref "U12") (pin "10") (pinfunction "GND_10") (pintype "passive"))
      (node (ref "U12") (pin "11") (pinfunction "GND(PAD)_11") (pintype "passive"))
      (node (ref "U14") (pin "3") (pinfunction "Vss_3") (pintype "passive"))
      (node (ref "U14") (pin "5") (pinfunction "AGND_5") (pintype "passive"))
      (node (ref "U15") (pin "10") (pinfunction "GND_10") (pintype "passive"))
      (node (ref "U15") (pin "11") (pinfunction "GND(PAD)_11") (pintype "passive"))
      (node (ref "U18") (pin "10") (pinfunction "GND_10") (pintype "passive"))
      (node (ref "U18") (pin "11") (pinfunction "GND(PAD)_11") (pintype "passive"))
      (node (ref "U19") (pin "10") (pinfunction "GND_10") (pintype "passive"))
      (node (ref "U19") (pin "11") (pinfunction "GND(PAD)_11") (pintype "passive"))
      (node (ref "U20") (pin "10") (pinfunction "GND_10") (pintype "passive"))
      (node (ref "U20") (pin "11") (pinfunction "GND(PAD)_11") (pintype "passive"))
      (node (ref "U3") (pin "2") (pinfunction "GND_2") (pintype "passive"))
      (node (ref "U4") (pin "1") (pinfunction "VSS_1") (pintype "passive"))
      (node (ref "U5") (pin "3") (pinfunction "A_3") (pintype "passive"))
      (node (ref "U7") (pin "3") (pinfunction "Vss_3") (pintype "passive"))
      (node (ref "U7") (pin "5") (pinfunction "AGND_5") (pintype "passive"))
      (node (ref "U8") (pin "10") (pinfunction "GND_10") (pintype "passive"))
      (node (ref "U8") (pin "11") (pinfunction "GND(PAD)_11") (pintype "passive"))
      (node (ref "U9") (pin "20") (pinfunction "VSSA_20") (pintype "power_in"))
    )
    (net (code "86") (name "GND") (class "Default")
      (node (ref "C1") (pin "1") (pinfunction "1_1") (pintype "passive"))
      (node (ref "C10") (pin "1") (pinfunction "1_1") (pintype "passive"))
      (node (ref "C11") (pin "1") (pinfunction "1_1") (pintype "passive"))
      (node (ref "C17") (pin "1") (pinfunction "1_1") (pintype "passive"))
      (node (ref "C18") (pin "1") (pinfunction "1_1") (pintype "passive"))
      (node (ref "C2") (pin "2") (pinfunction "2_2") (pintype "passive"))
      (node (ref "C23") (pin "1") (pinfunction "1_1") (pintype "passive"))
      (node (ref "C24") (pin "1") (pinfunction "1_1") (pintype "passive"))
      (node (ref "C26") (pin "1") (pinfunction "1_1") (pintype "passive"))
      (node (ref "C27") (pin "1") (pinfunction "1_1") (pintype "passive"))
      (node (ref "C29") (pin "1") (pinfunction "1_1") (pintype "passive"))
      (node (ref "C3") (pin "1") (pinfunction "1_1") (pintype "passive"))
      (node (ref "C4") (pin "2") (pinfunction "2_2") (pintype "passive"))
      (node (ref "C45") (pin "1") (pinfunction "1_1") (pintype "passive"))
      (node (ref "C46") (pin "1") (pinfunction "1_1") (pintype "passive"))
      (node (ref "C47") (pin "1") (pinfunction "1_1") (pintype "passive"))
      (node (ref "C48") (pin "1") (pinfunction "1_1") (pintype "passive"))
      (node (ref "C49") (pin "1") (pinfunction "1_1") (pintype "passive"))
      (node (ref "C5") (pin "1") (pinfunction "1_1") (pintype "passive"))
      (node (ref "C6") (pin "2") (pinfunction "2_2") (pintype "passive"))
      (node (ref "C7") (pin "2") (pinfunction "2_2") (pintype "passive"))
      (node (ref "C8") (pin "1") (pinfunction "1_1") (pintype "passive"))
      (node (ref "C9") (pin "1") (pinfunction "1_1") (pintype "passive"))
      (node (ref "D2") (pin "1") (pinfunction "A_1") (pintype "passive"))
      (node (ref "D3") (pin "1") (pinfunction "A_1") (pintype "passive"))
      (node (ref "D5") (pin "2") (pinfunction "K_2") (pintype "passive"))
      (node (ref "D6") (pin "1") (pinfunction "A_1") (pintype "passive"))
      (node (ref "D7") (pin "1") (pinfunction "A_1") (pintype "passive"))
      (node (ref "D8") (pin "1") (pinfunction "A_1") (pintype "passive"))
      (node (ref "P1") (pin "2") (pinfunction "2_2") (pintype "passive"))
      (node (ref "P2") (pin "1") (pinfunction "1_1") (pintype "passive"))
      (node (ref "P4") (pin "3") (pinfunction "3_3") (pintype "passive"))
      (node (ref "P6") (pin "2") (pinfunction "2_2") (pintype "passive"))
      (node (ref "P7") (pin "27") (pinfunction "27_27") (pintype "passive"))
      (node (ref "P7") (pin "28") (pinfunction "28_28") (pintype "passive"))
      (node (ref "P7") (pin "3") (pinfunction "3_3") (pintype "passive"))
      (node (ref "P7") (pin "4") (pinfunction "4_4") (pintype "passive"))
      (node (ref "Q42") (pin "2") (pinfunction "S_2") (pintype "passive"))
      (node (ref "R31") (pin "2") (pinfunction "2_2") (pintype "passive"))
      (node (ref "R33") (pin "2") (pinfunction "2_2") (pintype "passive"))
      (node (ref "S1") (pin "1") (pinfunction "1_1") (pintype "passive"))
      (node (ref "S1") (pin "5") (pinfunction "5_5") (pintype "passive"))
      (node (ref "S1") (pin "6") (pinfunction "6_6") (pintype "passive"))
      (node (ref "U1") (pin "4") (pinfunction "ON/OFF_4") (pintype "passive"))
      (node (ref "U1") (pin "5") (pinfunction "GND_5") (pintype "passive"))
      (node (ref "U1") (pin "6") (pinfunction "GND_6") (pintype "passive"))
      (node (ref "U1") (pin "7") (pinfunction "GND_7") (pintype "passive"))
      (node (ref "U1") (pin "8") (pinfunction "GND_8") (pintype "passive"))
      (node (ref "U13") (pin "2") (pinfunction "GND_2") (pintype "passive"))
      (node (ref "U13") (pin "8") (pinfunction "S_8") (pintype "passive"))
      (node (ref "U14") (pin "6") (pinfunction "DGND_6") (pintype "passive"))
      (node (ref "U16") (pin "4") (pinfunction "E_4") (pintype "passive"))
      (node (ref "U2") (pin "1") (pinfunction "VSS_1") (pintype "passive"))
      (node (ref "U6") (pin "3") (pinfunction "GND_3") (pintype "passive"))
      (node (ref "U6") (pin "7") (pinfunction "A0_7") (pintype "passive"))
      (node (ref "U6") (pin "8") (pinfunction "A1_8") (pintype "passive"))
      (node (ref "U7") (pin "6") (pinfunction "DGND_6") (pintype "passive"))
      (node (ref "U9") (pin "10") (pinfunction "VSS_10") (pintype "power_in"))
      (node (ref "U9") (pin "27") (pinfunction "VSS_27") (pintype "power_in"))
      (node (ref "U9") (pin "74") (pinfunction "VSS_74") (pintype "power_in"))
      (node (ref "U9") (pin "99") (pinfunction "VSS_99") (pintype "power_in"))
      (node (ref "s10") (pin "1") (pinfunction "Common_1") (pintype "passive"))
    )
    (net (code "87") (name "Net-(D1-A)") (class "Default")
      (node (ref "D1") (pin "1") (pinfunction "A_1") (pintype "passive"))
      (node (ref "F1") (pin "2") (pinfunction "2_2") (pintype "passive"))
    )
    (net (code "88") (name "Net-(D5-A)") (class "Default")
      (node (ref "D5") (pin "1") (pinfunction "A_1") (pintype "passive"))
      (node (ref "R16") (pin "2") (pinfunction "2_2") (pintype "passive"))
    )
    (net (code "89") (name "Net-(D8-K)") (class "Default")
      (node (ref "D8") (pin "2") (pinfunction "K_2") (pintype "passive"))
      (node (ref "L2") (pin "1") (pinfunction "1_1") (pintype "passive"))
      (node (ref "U1") (pin "2") (pinfunction "OUTPUT_2") (pintype "passive"))
    )
    (net (code "90") (name "Net-(F1-Pad1)") (class "Default")
      (node (ref "F1") (pin "1") (pinfunction "1_1") (pintype "passive"))
      (node (ref "P1") (pin "1") (pinfunction "1_1") (pintype "passive"))
      (node (ref "P6") (pin "1") (pinfunction "1_1") (pintype "passive"))
    )
    (net (code "91") (name "Net-(K1-Pad4)") (class "Default")
      (node (ref "K1") (pin "4") (pinfunction "4_4") (pintype "passive"))
      (node (ref "P2") (pin "5") (pinfunction "5_5") (pintype "passive"))
      (node (ref "R16") (pin "1") (pinfunction "1_1") (pintype "passive"))
    )
    (net (code "92") (name "Net-(K2-Pad3)") (class "Default")
      (node (ref "K2") (pin "3") (pinfunction "3_3") (pintype "passive"))
      (node (ref "K3") (pin "4") (pinfunction "4_4") (pintype "passive"))
      (node (ref "R17") (pin "2") (pinfunction "2_2") (pintype "passive"))
    )
    (net (code "93") (name "Net-(K4-Pad3)") (class "Default")
      (node (ref "K4") (pin "3") (pinfunction "3_3") (pintype "passive"))
      (node (ref "K5") (pin "4") (pinfunction "4_4") (pintype "passive"))
      (node (ref "R32") (pin "2") (pinfunction "2_2") (pintype "passive"))
    )
    (net (code "94") (name "Net-(K6-Pad3)") (class "Default")
      (node (ref "K6") (pin "3") (pinfunction "3_3") (pintype "passive"))
      (node (ref "K7") (pin "4") (pinfunction "4_4") (pintype "passive"))
      (node (ref "R50") (pin "2") (pinfunction "2_2") (pintype "passive"))
    )
    (net (code "95") (name "Net-(K8-Pad3)") (class "Default")
      (node (ref "K8") (pin "3") (pinfunction "3_3") (pintype "passive"))
      (node (ref "K9") (pin "4") (pinfunction "4_4") (pintype "passive"))
      (node (ref "R70") (pin "2") (pinfunction "2_2") (pintype "passive"))
    )
    (net (code "96") (name "Net-(K10-Pad3)") (class "Default")
      (node (ref "K10") (pin "3") (pinfunction "3_3") (pintype "passive"))
      (node (ref "K11") (pin "4") (pinfunction "4_4") (pintype "passive"))
      (node (ref "R87") (pin "2") (pinfunction "2_2") (pintype "passive"))
    )
    (net (code "97") (name "Net-(K12-Pad3)") (class "Default")
      (node (ref "K12") (pin "3") (pinfunction "3_3") (pintype "passive"))
      (node (ref "K13") (pin "4") (pinfunction "4_4") (pintype "passive"))
      (node (ref "R107") (pin "2") (pinfunction "2_2") (pintype "passive"))
    )
    (net (code "98") (name "Net-(K14-Pad3)") (class "Default")
      (node (ref "K14") (pin "3") (pinfunction "3_3") (pintype "passive"))
      (node (ref "K15") (pin "4") (pinfunction "4_4") (pintype "passive"))
      (node (ref "R121") (pin "2") (pinfunction "2_2") (pintype "passive"))
    )
    (net (code "99") (name "Net-(K16-Pad3)") (class "Default")
      (node (ref "K16") (pin "3") (pinfunction "3_3") (pintype "passive"))
      (node (ref "K17") (pin "4") (pinfunction "4_4") (pintype "passive"))
      (node (ref "R126") (pin "2") (pinfunction "2_2") (pintype "passive"))
    )
    (net (code "100") (name "Net-(LS1-B)") (class "Default")
      (node (ref "LS1") (pin "2") (pinfunction "B_2") (pintype "passive"))
      (node (ref "Q42") (pin "3") (pinfunction "D_3") (pintype "passive"))
    )
    (net (code "101") (name "Net-(Q1-B)") (class "Default")
      (node (ref "Q1") (pin "1") (pinfunction "B_1") (pintype "passive"))
      (node (ref "Q2") (pin "3") (pinfunction "S_3") (pintype "passive"))
      (node (ref "R15") (pin "2") (pinfunction "2_2") (pintype "passive"))
    )
    (net (code "102") (name "Net-(Q1-C)") (class "Default")
      (node (ref "Q1") (pin "3") (pinfunction "C_3") (pintype "passive"))
      (node (ref "Q2") (pin "1") (pinfunction "G_1") (pintype "passive"))
      (node (ref "U8") (pin "3") (pinfunction "VG_3") (pintype "passive"))
    )
    (net (code "103") (name "Net-(Q1-E)") (class "Default")
      (node (ref "Q1") (pin "2") (pinfunction "E_2") (pintype "passive"))
      (node (ref "R15") (pin "1") (pinfunction "1_1") (pintype "passive"))
      (node (ref "U8") (pin "2") (pinfunction "IS_2") (pintype "passive"))
    )
    (net (code "104") (name "Net-(Q2-D)") (class "Default")
      (node (ref "C21") (pin "1") (pinfunction "1_1") (pintype "passive"))
      (node (ref "Q2") (pin "2") (pinfunction "D_2") (pintype "passive"))
      (node (ref "R17") (pin "1") (pinfunction "1_1") (pintype "passive"))
    )
    (net (code "105") (name "Net-(Q4-B)") (class "Default")
      (node (ref "Q4") (pin "1") (pinfunction "B_1") (pintype "passive"))
      (node (ref "Q5") (pin "3") (pinfunction "S_3") (pintype "passive"))
      (node (ref "R21") (pin "2") (pinfunction "2_2") (pintype "passive"))
    )
    (net (code "106") (name "Net-(Q4-C)") (class "Default")
      (node (ref "Q4") (pin "3") (pinfunction "C_3") (pintype "passive"))
      (node (ref "Q5") (pin "1") (pinfunction "G_1") (pintype "passive"))
      (node (ref "U10") (pin "3") (pinfunction "VG_3") (pintype "passive"))
    )
    (net (code "107") (name "Net-(Q4-E)") (class "Default")
      (node (ref "Q4") (pin "2") (pinfunction "E_2") (pintype "passive"))
      (node (ref "R21") (pin "1") (pinfunction "1_1") (pintype "passive"))
      (node (ref "U10") (pin "2") (pinfunction "IS_2") (pintype "passive"))
    )
    (net (code "108") (name "Net-(Q5-D)") (class "Default")
      (node (ref "C25") (pin "1") (pinfunction "1_1") (pintype "passive"))
      (node (ref "Q5") (pin "2") (pinfunction "D_2") (pintype "passive"))
      (node (ref "R32") (pin "1") (pinfunction "1_1") (pintype "passive"))
    )
    (net (code "109") (name "Net-(Q6-D)") (class "Default")
      (node (ref "Q6") (pin "3") (pinfunction "D_3") (pintype "passive"))
      (node (ref "R25") (pin "1") (pinfunction "1_1") (pintype "passive"))
      (node (ref "R26") (pin "1") (pinfunction "1_1") (pintype "passive"))
    )
    (net (code "110") (name "Net-(Q7-D)") (class "Default")
      (node (ref "Q7") (pin "3") (pinfunction "D_3") (pintype "passive"))
      (node (ref "R27") (pin "1") (pinfunction "1_1") (pintype "passive"))
      (node (ref "R28") (pin "1") (pinfunction "1_1") (pintype "passive"))
    )
    (net (code "111") (name "Net-(Q8-D)") (class "Default")
      (node (ref "Q8") (pin "3") (pinfunction "D_3") (pintype "passive"))
      (node (ref "R29") (pin "1") (pinfunction "1_1") (pintype "passive"))
      (node (ref "R30") (pin "1") (pinfunction "1_1") (pintype "passive"))
    )
    (net (code "112") (name "Net-(Q9-D)") (class "Default")
      (node (ref "Q9") (pin "3") (pinfunction "D_3") (pintype "passive"))
      (node (ref "R40") (pin "1") (pinfunction "1_1") (pintype "passive"))
      (node (ref "R41") (pin "1") (pinfunction "1_1") (pintype "passive"))
    )
    (net (code "113") (name "Net-(Q10-D)") (class "Default")
      (node (ref "Q10") (pin "3") (pinfunction "D_3") (pintype "passive"))
      (node (ref "R42") (pin "1") (pinfunction "1_1") (pintype "passive"))
      (node (ref "R43") (pin "1") (pinfunction "1_1") (pintype "passive"))
    )
    (net (code "114") (name "Net-(Q11-D)") (class "Default")
      (node (ref "Q11") (pin "3") (pinfunction "D_3") (pintype "passive"))
      (node (ref "R44") (pin "1") (pinfunction "1_1") (pintype "passive"))
      (node (ref "R45") (pin "1") (pinfunction "1_1") (pintype "passive"))
    )
    (net (code "115") (name "Net-(Q12-B)") (class "Default")
      (node (ref "Q12") (pin "1") (pinfunction "B_1") (pintype "passive"))
      (node (ref "Q13") (pin "3") (pinfunction "S_3") (pintype "passive"))
      (node (ref "R46") (pin "2") (pinfunction "2_2") (pintype "passive"))
    )
    (net (code "116") (name "Net-(Q12-C)") (class "Default")
      (node (ref "Q12") (pin "3") (pinfunction "C_3") (pintype "passive"))
      (node (ref "Q13") (pin "1") (pinfunction "G_1") (pintype "passive"))
      (node (ref "U11") (pin "3") (pinfunction "VG_3") (pintype "passive"))
    )
    (net (code "117") (name "Net-(Q12-E)") (class "Default")
      (node (ref "Q12") (pin "2") (pinfunction "E_2") (pintype "passive"))
      (node (ref "R46") (pin "1") (pinfunction "1_1") (pintype "passive"))
      (node (ref "U11") (pin "2") (pinfunction "IS_2") (pintype "passive"))
    )
    (net (code "118") (name "Net-(Q13-D)") (class "Default")
      (node (ref "C30") (pin "1") (pinfunction "1_1") (pintype "passive"))
      (node (ref "Q13") (pin "2") (pinfunction "D_2") (pintype "passive"))
      (node (ref "R50") (pin "1") (pinfunction "1_1") (pintype "passive"))
    )
    (net (code "119") (name "Net-(Q14-D)") (class "Default")
      (node (ref "Q14") (pin "3") (pinfunction "D_3") (pintype "passive"))
      (node (ref "R51") (pin "1") (pinfunction "1_1") (pintype "passive"))
      (node (ref "R52") (pin "1") (pinfunction "1_1") (pintype "passive"))
    )
    (net (code "120") (name "Net-(Q15-D)") (class "Default")
      (node (ref "Q15") (pin "3") (pinfunction "D_3") (pintype "passive"))
      (node (ref "R53") (pin "1") (pinfunction "1_1") (pintype "passive"))
      (node (ref "R54") (pin "1") (pinfunction "1_1") (pintype "passive"))
    )
    (net (code "121") (name "Net-(Q16-D)") (class "Default")
      (node (ref "Q16") (pin "3") (pinfunction "D_3") (pintype "passive"))
      (node (ref "R55") (pin "1") (pinfunction "1_1") (pintype "passive"))
      (node (ref "R56") (pin "1") (pinfunction "1_1") (pintype "passive"))
    )
    (net (code "122") (name "Net-(Q17-B)") (class "Default")
      (node (ref "Q17") (pin "1") (pinfunction "B_1") (pintype "passive"))
      (node (ref "Q18") (pin "3") (pinfunction "S_3") (pintype "passive"))
      (node (ref "R63") (pin "2") (pinfunction "2_2") (pintype "passive"))
    )
    (net (code "123") (name "Net-(Q17-C)") (class "Default")
      (node (ref "Q17") (pin "3") (pinfunction "C_3") (pintype "passive"))
      (node (ref "Q18") (pin "1") (pinfunction "G_1") (pintype "passive"))
      (node (ref "U12") (pin "3") (pinfunction "VG_3") (pintype "passive"))
    )
    (net (code "124") (name "Net-(Q17-E)") (class "Default")
      (node (ref "Q17") (pin "2") (pinfunction "E_2") (pintype "passive"))
      (node (ref "R63") (pin "1") (pinfunction "1_1") (pintype "passive"))
      (node (ref "U12") (pin "2") (pinfunction "IS_2") (pintype "passive"))
    )
    (net (code "125") (name "Net-(Q18-D)") (class "Default")
      (node (ref "C32") (pin "1") (pinfunction "1_1") (pintype "passive"))
      (node (ref "Q18") (pin "2") (pinfunction "D_2") (pintype "passive"))
      (node (ref "R70") (pin "1") (pinfunction "1_1") (pintype "passive"))
    )
    (net (code "126") (name "Net-(Q19-D)") (class "Default")
      (node (ref "Q19") (pin "3") (pinfunction "D_3") (pintype "passive"))
      (node (ref "R64") (pin "1") (pinfunction "1_1") (pintype "passive"))
      (node (ref "R65") (pin "1") (pinfunction "1_1") (pintype "passive"))
    )
    (net (code "127") (name "Net-(Q20-D)") (class "Default")
      (node (ref "Q20") (pin "3") (pinfunction "D_3") (pintype "passive"))
      (node (ref "R66") (pin "1") (pinfunction "1_1") (pintype "passive"))
      (node (ref "R67") (pin "1") (pinfunction "1_1") (pintype "passive"))
    )
    (net (code "128") (name "Net-(Q21-D)") (class "Default")
      (node (ref "Q21") (pin "3") (pinfunction "D_3") (pintype "passive"))
      (node (ref "R68") (pin "1") (pinfunction "1_1") (pintype "passive"))
      (node (ref "R69") (pin "1") (pinfunction "1_1") (pintype "passive"))
    )
    (net (code "129") (name "Net-(Q22-D)") (class "Default")
      (node (ref "Q22") (pin "3") (pinfunction "D_3") (pintype "passive"))
      (node (ref "R77") (pin "1") (pinfunction "1_1") (pintype "passive"))
      (node (ref "R78") (pin "1") (pinfunction "1_1") (pintype "passive"))
    )
    (net (code "130") (name "Net-(Q23-D)") (class "Default")
      (node (ref "Q23") (pin "3") (pinfunction "D_3") (pintype "passive"))
      (node (ref "R79") (pin "1") (pinfunction "1_1") (pintype "passive"))
      (node (ref "R80") (pin "1") (pinfunction "1_1") (pintype "passive"))
    )
    (net (code "131") (name "Net-(Q24-D)") (class "Default")
      (node (ref "Q24") (pin "3") (pinfunction "D_3") (pintype "passive"))
      (node (ref "R81") (pin "1") (pinfunction "1_1") (pintype "passive"))
      (node (ref "R82") (pin "1") (pinfunction "1_1") (pintype "passive"))
    )
    (net (code "132") (name "Net-(Q25-B)") (class "Default")
      (node (ref "Q25") (pin "1") (pinfunction "B_1") (pintype "passive"))
      (node (ref "Q26") (pin "3") (pinfunction "S_3") (pintype "passive"))
      (node (ref "R83") (pin "2") (pinfunction "2_2") (pintype "passive"))
    )
    (net (code "133") (name "Net-(Q25-C)") (class "Default")
      (node (ref "Q25") (pin "3") (pinfunction "C_3") (pintype "passive"))
      (node (ref "Q26") (pin "1") (pinfunction "G_1") (pintype "passive"))
      (node (ref "U15") (pin "3") (pinfunction "VG_3") (pintype "passive"))
    )
    (net (code "134") (name "Net-(Q25-E)") (class "Default")
      (node (ref "Q25") (pin "2") (pinfunction "E_2") (pintype "passive"))
      (node (ref "R83") (pin "1") (pinfunction "1_1") (pintype "passive"))
      (node (ref "U15") (pin "2") (pinfunction "IS_2") (pintype "passive"))
    )
    (net (code "135") (name "Net-(Q26-D)") (class "Default")
      (node (ref "C34") (pin "1") (pinfunction "1_1") (pintype "passive"))
      (node (ref "Q26") (pin "2") (pinfunction "D_2") (pintype "passive"))
      (node (ref "R87") (pin "1") (pinfunction "1_1") (pintype "passive"))
    )
    (net (code "136") (name "Net-(Q27-D)") (class "Default")
      (node (ref "Q27") (pin "3") (pinfunction "D_3") (pintype "passive"))
      (node (ref "R88") (pin "1") (pinfunction "1_1") (pintype "passive"))
      (node (ref "R89") (pin "1") (pinfunction "1_1") (pintype "passive"))
    )
    (net (code "137") (name "Net-(Q28-D)") (class "Default")
      (node (ref "Q28") (pin "3") (pinfunction "D_3") (pintype "passive"))
      (node (ref "R90") (pin "1") (pinfunction "1_1") (pintype "passive"))
      (node (ref "R91") (pin "1") (pinfunction "1_1") (pintype "passive"))
    )
    (net (code "138") (name "Net-(Q29-D)") (class "Default")
      (node (ref "Q29") (pin "3") (pinfunction "D_3") (pintype "passive"))
      (node (ref "R92") (pin "1") (pinfunction "1_1") (pintype "passive"))
      (node (ref "R93") (pin "1") (pinfunction "1_1") (pintype "passive"))
    )
    (net (code "139") (name "Net-(Q30-B)") (class "Default")
      (node (ref "Q30") (pin "1") (pinfunction "B_1") (pintype "passive"))
      (node (ref "Q34") (pin "3") (pinfunction "S_3") (pintype "passive"))
      (node (ref "R100") (pin "2") (pinfunction "2_2") (pintype "passive"))
    )
    (net (code "140") (name "Net-(Q30-C)") (class "Default")
      (node (ref "Q30") (pin "3") (pinfunction "C_3") (pintype "passive"))
      (node (ref "Q34") (pin "1") (pinfunction "G_1") (pintype "passive"))
      (node (ref "U18") (pin "3") (pinfunction "VG_3") (pintype "passive"))
    )
    (net (code "141") (name "Net-(Q30-E)") (class "Default")
      (node (ref "Q30") (pin "2") (pinfunction "E_2") (pintype "passive"))
      (node (ref "R100") (pin "1") (pinfunction "1_1") (pintype "passive"))
      (node (ref "U18") (pin "2") (pinfunction "IS_2") (pintype "passive"))
    )
    (net (code "142") (name "Net-(Q31-D)") (class "Default")
      (node (ref "Q31") (pin "3") (pinfunction "D_3") (pintype "passive"))
      (node (ref "R101") (pin "1") (pinfunction "1_1") (pintype "passive"))
      (node (ref "R102") (pin "1") (pinfunction "1_1") (pintype "passive"))
    )
    (net (code "143") (name "Net-(Q32-D)") (class "Default")
      (node (ref "Q32") (pin "3") (pinfunction "D_3") (pintype "passive"))
      (node (ref "R103") (pin "1") (pinfunction "1_1") (pintype "passive"))
      (node (ref "R104") (pin "1") (pinfunction "1_1") (pintype "passive"))
    )
    (net (code "144") (name "Net-(Q33-D)") (class "Default")
      (node (ref "Q33") (pin "3") (pinfunction "D_3") (pintype "passive"))
      (node (ref "R105") (pin "1") (pinfunction "1_1") (pintype "passive"))
      (node (ref "R106") (pin "1") (pinfunction "1_1") (pintype "passive"))
    )
    (net (code "145") (name "Net-(Q34-D)") (class "Default")
      (node (ref "C36") (pin "1") (pinfunction "1_1") (pintype "passive"))
      (node (ref "Q34") (pin "2") (pinfunction "D_2") (pintype "passive"))
      (node (ref "R107") (pin "1") (pinfunction "1_1") (pintype "passive"))
    )
    (net (code "146") (name "Net-(Q35-D)") (class "Default")
      (node (ref "Q35") (pin "3") (pinfunction "D_3") (pintype "passive"))
      (node (ref "R113") (pin "1") (pinfunction "1_1") (pintype "passive"))
      (node (ref "R114") (pin "1") (pinfunction "1_1") (pintype "passive"))
    )
    (net (code "147") (name "Net-(Q36-D)") (class "Default")
      (node (ref "Q36") (pin "3") (pinfunction "D_3") (pintype "passive"))
      (node (ref "R115") (pin "1") (pinfunction "1_1") (pintype "passive"))
      (node (ref "R116") (pin "1") (pinfunction "1_1") (pintype "passive"))
    )
    (net (code "148") (name "Net-(Q37-D)") (class "Default")
      (node (ref "Q37") (pin "3") (pinfunction "D_3") (pintype "passive"))
      (node (ref "R117") (pin "1") (pinfunction "1_1") (pintype "passive"))
      (node (ref "R118") (pin "1") (pinfunction "1_1") (pintype "passive"))
    )
    (net (code "149") (name "Net-(Q38-B)") (class "Default")
      (node (ref "Q38") (pin "1") (pinfunction "B_1") (pintype "passive"))
      (node (ref "Q39") (pin "3") (pinfunction "S_3") (pintype "passive"))
      (node (ref "R120") (pin "2") (pinfunction "2_2") (pintype "passive"))
    )
    (net (code "150") (name "Net-(Q38-C)") (class "Default")
      (node (ref "Q38") (pin "3") (pinfunction "C_3") (pintype "passive"))
      (node (ref "Q39") (pin "1") (pinfunction "G_1") (pintype "passive"))
      (node (ref "U19") (pin "3") (pinfunction "VG_3") (pintype "passive"))
    )
    (net (code "151") (name "Net-(Q38-E)") (class "Default")
      (node (ref "Q38") (pin "2") (pinfunction "E_2") (pintype "passive"))
      (node (ref "R120") (pin "1") (pinfunction "1_1") (pintype "passive"))
      (node (ref "U19") (pin "2") (pinfunction "IS_2") (pintype "passive"))
    )
    (net (code "152") (name "Net-(Q39-D)") (class "Default")
      (node (ref "C38") (pin "1") (pinfunction "1_1") (pintype "passive"))
      (node (ref "Q39") (pin "2") (pinfunction "D_2") (pintype "passive"))
      (node (ref "R121") (pin "1") (pinfunction "1_1") (pintype "passive"))
    )
    (net (code "153") (name "Net-(Q40-B)") (class "Default")
      (node (ref "Q40") (pin "1") (pinfunction "B_1") (pintype "passive"))
      (node (ref "Q41") (pin "3") (pinfunction "S_3") (pintype "passive"))
      (node (ref "R125") (pin "2") (pinfunction "2_2") (pintype "passive"))
    )
    (net (code "154") (name "Net-(Q40-C)") (class "Default")
      (node (ref "Q40") (pin "3") (pinfunction "C_3") (pintype "passive"))
      (node (ref "Q41") (pin "1") (pinfunction "G_1") (pintype "passive"))
      (node (ref "U20") (pin "3") (pinfunction "VG_3") (pintype "passive"))
    )
    (net (code "155") (name "Net-(Q40-E)") (class "Default")
      (node (ref "Q40") (pin "2") (pinfunction "E_2") (pintype "passive"))
      (node (ref "R125") (pin "1") (pinfunction "1_1") (pintype "passive"))
      (node (ref "U20") (pin "2") (pinfunction "IS_2") (pintype "passive"))
    )
    (net (code "156") (name "Net-(Q41-D)") (class "Default")
      (node (ref "C40") (pin "1") (pinfunction "1_1") (pintype "passive"))
      (node (ref "Q41") (pin "2") (pinfunction "D_2") (pintype "passive"))
      (node (ref "R126") (pin "1") (pinfunction "1_1") (pintype "passive"))
    )
    (net (code "157") (name "Net-(R10-Pad2)") (class "Default")
      (node (ref "R10") (pin "2") (pinfunction "2_2") (pintype "passive"))
      (node (ref "R6") (pin "1") (pinfunction "1_1") (pintype "passive"))
      (node (ref "R9") (pin "2") (pinfunction "2_2") (pintype "passive"))
    )
    (net (code "158") (name "Net-(R18-Pad2)") (class "Default")
      (node (ref "R18") (pin "2") (pinfunction "2_2") (pintype "passive"))
      (node (ref "R20") (pin "1") (pinfunction "1_1") (pintype "passive"))
    )
    (net (code "159") (name "Net-(R22-Pad1)") (class "Default")
      (node (ref "R22") (pin "1") (pinfunction "1_1") (pintype "passive"))
      (node (ref "R25") (pin "2") (pinfunction "2_2") (pintype "passive"))
      (node (ref "R26") (pin "2") (pinfunction "2_2") (pintype "passive"))
    )
    (net (code "160") (name "Net-(R23-Pad1)") (class "Default")
      (node (ref "R23") (pin "1") (pinfunction "1_1") (pintype "passive"))
      (node (ref "R27") (pin "2") (pinfunction "2_2") (pintype "passive"))
      (node (ref "R28") (pin "2") (pinfunction "2_2") (pintype "passive"))
    )
    (net (code "161") (name "Net-(R24-Pad1)") (class "Default")
      (node (ref "R24") (pin "1") (pinfunction "1_1") (pintype "passive"))
      (node (ref "R29") (pin "2") (pinfunction "2_2") (pintype "passive"))
      (node (ref "R30") (pin "2") (pinfunction "2_2") (pintype "passive"))
    )
    (net (code "162") (name "Net-(R34-Pad2)") (class "Default")
      (node (ref "R34") (pin "2") (pinfunction "2_2") (pintype "passive"))
      (node (ref "R39") (pin "1") (pinfunction "1_1") (pintype "passive"))
    )
    (net (code "163") (name "Net-(R36-Pad1)") (class "Default")
      (node (ref "R36") (pin "1") (pinfunction "1_1") (pintype "passive"))
      (node (ref "R40") (pin "2") (pinfunction "2_2") (pintype "passive"))
      (node (ref "R41") (pin "2") (pinfunction "2_2") (pintype "passive"))
    )
    (net (code "164") (name "Net-(R37-Pad1)") (class "Default")
      (node (ref "R37") (pin "1") (pinfunction "1_1") (pintype "passive"))
      (node (ref "R42") (pin "2") (pinfunction "2_2") (pintype "passive"))
      (node (ref "R43") (pin "2") (pinfunction "2_2") (pintype "passive"))
    )
    (net (code "165") (name "Net-(R38-Pad1)") (class "Default")
      (node (ref "R38") (pin "1") (pinfunction "1_1") (pintype "passive"))
      (node (ref "R44") (pin "2") (pinfunction "2_2") (pintype "passive"))
      (node (ref "R45") (pin "2") (pinfunction "2_2") (pintype "passive"))
    )
    (net (code "166") (name "Net-(R47-Pad1)") (class "Default")
      (node (ref "R47") (pin "1") (pinfunction "1_1") (pintype "passive"))
      (node (ref "R51") (pin "2") (pinfunction "2_2") (pintype "passive"))
      (node (ref "R52") (pin "2") (pinfunction "2_2") (pintype "passive"))
    )
    (net (code "167") (name "Net-(R48-Pad1)") (class "Default")
      (node (ref "R48") (pin "1") (pinfunction "1_1") (pintype "passive"))
      (node (ref "R53") (pin "2") (pinfunction "2_2") (pintype "passive"))
      (node (ref "R54") (pin "2") (pinfunction "2_2") (pintype "passive"))
    )
    (net (code "168") (name "Net-(R49-Pad1)") (class "Default")
      (node (ref "R49") (pin "1") (pinfunction "1_1") (pintype "passive"))
      (node (ref "R55") (pin "2") (pinfunction "2_2") (pintype "passive"))
      (node (ref "R56") (pin "2") (pinfunction "2_2") (pintype "passive"))
    )
    (net (code "169") (name "Net-(R57-Pad2)") (class "Default")
      (node (ref "R57") (pin "2") (pinfunction "2_2") (pintype "passive"))
      (node (ref "R59") (pin "1") (pinfunction "1_1") (pintype "passive"))
    )
    (net (code "170") (name "Net-(R60-Pad1)") (class "Default")
      (node (ref "R60") (pin "1") (pinfunction "1_1") (pintype "passive"))
      (node (ref "R64") (pin "2") (pinfunction "2_2") (pintype "passive"))
      (node (ref "R65") (pin "2") (pinfunction "2_2") (pintype "passive"))
    )
    (net (code "171") (name "Net-(R61-Pad1)") (class "Default")
      (node (ref "R61") (pin "1") (pinfunction "1_1") (pintype "passive"))
      (node (ref "R66") (pin "2") (pinfunction "2_2") (pintype "passive"))
      (node (ref "R67") (pin "2") (pinfunction "2_2") (pintype "passive"))
    )
    (net (code "172") (name "Net-(R62-Pad1)") (class "Default")
      (node (ref "R62") (pin "1") (pinfunction "1_1") (pintype "passive"))
      (node (ref "R68") (pin "2") (pinfunction "2_2") (pintype "passive"))
      (node (ref "R69") (pin "2") (pinfunction "2_2") (pintype "passive"))
    )
    (net (code "173") (name "Net-(R71-Pad2)") (class "Default")
      (node (ref "R71") (pin "2") (pinfunction "2_2") (pintype "passive"))
      (node (ref "R76") (pin "1") (pinfunction "1_1") (pintype "passive"))
    )
    (net (code "174") (name "Net-(R73-Pad1)") (class "Default")
      (node (ref "R73") (pin "1") (pinfunction "1_1") (pintype "passive"))
      (node (ref "R77") (pin "2") (pinfunction "2_2") (pintype "passive"))
      (node (ref "R78") (pin "2") (pinfunction "2_2") (pintype "passive"))
    )
    (net (code "175") (name "Net-(R74-Pad1)") (class "Default")
      (node (ref "R74") (pin "1") (pinfunction "1_1") (pintype "passive"))
      (node (ref "R79") (pin "2") (pinfunction "2_2") (pintype "passive"))
      (node (ref "R80") (pin "2") (pinfunction "2_2") (pintype "passive"))
    )
    (net (code "176") (name "Net-(R75-Pad1)") (class "Default")
      (node (ref "R75") (pin "1") (pinfunction "1_1") (pintype "passive"))
      (node (ref "R81") (pin "2") (pinfunction "2_2") (pintype "passive"))
      (node (ref "R82") (pin "2") (pinfunction "2_2") (pintype "passive"))
    )
    (net (code "177") (name "Net-(R84-Pad1)") (class "Default")
      (node (ref "R84") (pin "1") (pinfunction "1_1") (pintype "passive"))
      (node (ref "R88") (pin "2") (pinfunction "2_2") (pintype "passive"))
      (node (ref "R89") (pin "2") (pinfunction "2_2") (pintype "passive"))
    )
    (net (code "178") (name "Net-(R85-Pad1)") (class "Default")
      (node (ref "R85") (pin "1") (pinfunction "1_1") (pintype "passive"))
      (node (ref "R90") (pin "2") (pinfunction "2_2") (pintype "passive"))
      (node (ref "R91") (pin "2") (pinfunction "2_2") (pintype "passive"))
    )
    (net (code "179") (name "Net-(R86-Pad1)") (class "Default")
      (node (ref "R86") (pin "1") (pinfunction "1_1") (pintype "passive"))
      (node (ref "R92") (pin "2") (pinfunction "2_2") (pintype "passive"))
      (node (ref "R93") (pin "2") (pinfunction "2_2") (pintype "passive"))
    )
    (net (code "180") (name "Net-(R94-Pad2)") (class "Default")
      (node (ref "R94") (pin "2") (pinfunction "2_2") (pintype "passive"))
      (node (ref "R96") (pin "1") (pinfunction "1_1") (pintype "passive"))
    )
    (net (code "181") (name "Net-(R101-Pad2)") (class "Default")
      (node (ref "R101") (pin "2") (pinfunction "2_2") (pintype "passive"))
      (node (ref "R102") (pin "2") (pinfunction "2_2") (pintype "passive"))
      (node (ref "R97") (pin "1") (pinfunction "1_1") (pintype "passive"))
    )
    (net (code "182") (name "Net-(R103-Pad2)") (class "Default")
      (node (ref "R103") (pin "2") (pinfunction "2_2") (pintype "passive"))
      (node (ref "R104") (pin "2") (pinfunction "2_2") (pintype "passive"))
      (node (ref "R98") (pin "1") (pinfunction "1_1") (pintype "passive"))
    )
    (net (code "183") (name "Net-(R105-Pad2)") (class "Default")
      (node (ref "R105") (pin "2") (pinfunction "2_2") (pintype "passive"))
      (node (ref "R106") (pin "2") (pinfunction "2_2") (pintype "passive"))
      (node (ref "R99") (pin "1") (pinfunction "1_1") (pintype "passive"))
    )
    (net (code "184") (name "Net-(R108-Pad1)") (class "Default")
      (node (ref "R108") (pin "1") (pinfunction "1_1") (pintype "passive"))
      (node (ref "R113") (pin "2") (pinfunction "2_2") (pintype "passive"))
      (node (ref "R114") (pin "2") (pinfunction "2_2") (pintype "passive"))
    )
    (net (code "185") (name "Net-(R109-Pad1)") (class "Default")
      (node (ref "R109") (pin "1") (pinfunction "1_1") (pintype "passive"))
      (node (ref "R115") (pin "2") (pinfunction "2_2") (pintype "passive"))
      (node (ref "R116") (pin "2") (pinfunction "2_2") (pintype "passive"))
    )
    (net (code "186") (name "Net-(R110-Pad1)") (class "Default")
      (node (ref "R110") (pin "1") (pinfunction "1_1") (pintype "passive"))
      (node (ref "R117") (pin "2") (pinfunction "2_2") (pintype "passive"))
      (node (ref "R118") (pin "2") (pinfunction "2_2") (pintype "passive"))
    )
    (net (code "187") (name "Net-(R111-Pad2)") (class "Default")
      (node (ref "R111") (pin "2") (pinfunction "2_2") (pintype "passive"))
      (node (ref "R119") (pin "1") (pinfunction "1_1") (pintype "passive"))
    )
    (net (code "188") (name "Net-(R122-Pad2)") (class "Default")
      (node (ref "R122") (pin "2") (pinfunction "2_2") (pintype "passive"))
      (node (ref "R124") (pin "1") (pinfunction "1_1") (pintype "passive"))
    )
    (net (code "189") (name "Net-(R127-Pad2)") (class "Default")
      (node (ref "R127") (pin "2") (pinfunction "2_2") (pintype "passive"))
      (node (ref "R129") (pin "1") (pinfunction "1_1") (pintype "passive"))
    )
    (net (code "190") (name "Net-(U4-VIN)") (class "Default")
      (node (ref "C16") (pin "2") (pinfunction "2_2") (pintype "passive"))
      (node (ref "C44") (pin "1") (pinfunction "1_1") (pintype "passive"))
      (node (ref "I1") (pin "1") (pinfunction "1_1") (pintype "passive"))
      (node (ref "U4") (pin "3") (pinfunction "VIN_3") (pintype "passive"))
    )
    (net (code "191") (name "Net-(U5-REF)") (class "Default")
      (node (ref "R10") (pin "1") (pinfunction "1_1") (pintype "passive"))
      (node (ref "R11") (pin "2") (pinfunction "2_2") (pintype "passive"))
      (node (ref "R9") (pin "1") (pinfunction "1_1") (pintype "passive"))
      (node (ref "U5") (pin "1") (pinfunction "REF_1") (pintype "passive"))
    )
    (net (code "192") (name "Net-(U6-IN-)") (class "Default")
      (node (ref "K1") (pin "3") (pinfunction "3_3") (pintype "passive"))
      (node (ref "R14") (pin "1") (pinfunction "1_1") (pintype "passive"))
      (node (ref "U6") (pin "2") (pinfunction "IN-_2") (pintype "passive"))
    )
    (net (code "193") (name "Net-(U8-OD)") (class "Default")
      (node (ref "R19") (pin "1") (pinfunction "1_1") (pintype "passive"))
      (node (ref "U8") (pin "9") (pinfunction "OD_9") (pintype "passive"))
    )
    (net (code "194") (name "Net-(U8-SET)") (class "Default")
      (node (ref "K3") (pin "3") (pinfunction "3_3") (pintype "passive"))
      (node (ref "R18") (pin "1") (pinfunction "1_1") (pintype "passive"))
      (node (ref "U8") (pin "7") (pinfunction "SET_7") (pintype "passive"))
    )
    (net (code "195") (name "Net-(U9-BOOT0{slash}VPP)") (class "Default")
      (node (ref "R31") (pin "1") (pinfunction "1_1") (pintype "passive"))
      (node (ref "U9") (pin "94") (pinfunction "BOOT0/VPP_94") (pintype "input"))
    )
    (net (code "196") (name "Net-(U9-PB2-BOOT1(PB2){slash}EVENTOUT)") (class "Default")
      (node (ref "R33") (pin "1") (pinfunction "1_1") (pintype "passive"))
      (node (ref "U9") (pin "37") (pinfunction "PB2-BOOT1(PB2)/EVENTOUT_37") (pintype "bidirectional"))
    )
    (net (code "197") (name "Net-(U9-PH0-OSC_IN(PH0){slash}EVENTOUT{slash}OSC_IN)") (class "Default")
      (node (ref "C26") (pin "2") (pinfunction "2_2") (pintype "passive"))
      (node (ref "U9") (pin "12") (pinfunction "PH0-OSC_IN(PH0)/EVENTOUT/OSC_IN_12") (pintype "bidirectional"))
      (node (ref "Y1") (pin "2") (pinfunction "OSC2_2") (pintype "passive"))
    )
    (net (code "198") (name "Net-(U9-PH1-OSC_OUT(PH1){slash}EVENTOUT{slash}OSC_OUT)") (class "Default")
      (node (ref "C27") (pin "2") (pinfunction "2_2") (pintype "passive"))
      (node (ref "U9") (pin "13") (pinfunction "PH1-OSC_OUT(PH1)/EVENTOUT/OSC_OUT_13") (pintype "bidirectional"))
      (node (ref "Y1") (pin "1") (pinfunction "OSC1_1") (pintype "passive"))
    )
    (net (code "199") (name "Net-(U9-VCAP_1)") (class "Default")
      (node (ref "C23") (pin "2") (pinfunction "2_2") (pintype "passive"))
      (node (ref "U9") (pin "49") (pinfunction "VCAP_1_49") (pintype "power_in"))
    )
    (net (code "200") (name "Net-(U9-VCAP_2)") (class "Default")
      (node (ref "C24") (pin "2") (pinfunction "2_2") (pintype "passive"))
      (node (ref "U9") (pin "73") (pinfunction "VCAP_2_73") (pintype "power_in"))
    )
    (net (code "201") (name "Net-(U10-OD)") (class "Default")
      (node (ref "R35") (pin "1") (pinfunction "1_1") (pintype "passive"))
      (node (ref "U10") (pin "9") (pinfunction "OD_9") (pintype "passive"))
    )
    (net (code "202") (name "Net-(U10-SET)") (class "Default")
      (node (ref "K5") (pin "3") (pinfunction "3_3") (pintype "passive"))
      (node (ref "R34") (pin "1") (pinfunction "1_1") (pintype "passive"))
      (node (ref "U10") (pin "7") (pinfunction "SET_7") (pintype "passive"))
    )
    (net (code "203") (name "Net-(U11-OD)") (class "Default")
      (node (ref "R58") (pin "1") (pinfunction "1_1") (pintype "passive"))
      (node (ref "U11") (pin "9") (pinfunction "OD_9") (pintype "passive"))
    )
    (net (code "204") (name "Net-(U11-SET)") (class "Default")
      (node (ref "K7") (pin "3") (pinfunction "3_3") (pintype "passive"))
      (node (ref "R57") (pin "1") (pinfunction "1_1") (pintype "passive"))
      (node (ref "U11") (pin "7") (pinfunction "SET_7") (pintype "passive"))
    )
    (net (code "205") (name "Net-(U12-OD)") (class "Default")
      (node (ref "R72") (pin "1") (pinfunction "1_1") (pintype "passive"))
      (node (ref "U12") (pin "9") (pinfunction "OD_9") (pintype "passive"))
    )
    (net (code "206") (name "Net-(U12-SET)") (class "Default")
      (node (ref "K9") (pin "3") (pinfunction "3_3") (pintype "passive"))
      (node (ref "R71") (pin "1") (pinfunction "1_1") (pintype "passive"))
      (node (ref "U12") (pin "7") (pinfunction "SET_7") (pintype "passive"))
    )
    (net (code "207") (name "Net-(U15-OD)") (class "Default")
      (node (ref "R95") (pin "1") (pinfunction "1_1") (pintype "passive"))
      (node (ref "U15") (pin "9") (pinfunction "OD_9") (pintype "passive"))
    )
    (net (code "208") (name "Net-(U15-SET)") (class "Default")
      (node (ref "K11") (pin "3") (pinfunction "3_3") (pintype "passive"))
      (node (ref "R94") (pin "1") (pinfunction "1_1") (pintype "passive"))
      (node (ref "U15") (pin "7") (pinfunction "SET_7") (pintype "passive"))
    )
    (net (code "209") (name "Net-(U16-1B)") (class "Default")
      (node (ref "K1") (pin "1") (pinfunction "1_1") (pintype "passive"))
      (node (ref "U16") (pin "1") (pinfunction "1B_1") (pintype "passive"))
    )
    (net (code "210") (name "Net-(U16-2B)") (class "Default")
      (node (ref "K10") (pin "1") (pinfunction "1_1") (pintype "passive"))
      (node (ref "K12") (pin "1") (pinfunction "1_1") (pintype "passive"))
      (node (ref "K14") (pin "1") (pinfunction "1_1") (pintype "passive"))
      (node (ref "K16") (pin "1") (pinfunction "1_1") (pintype "passive"))
      (node (ref "K2") (pin "1") (pinfunction "1_1") (pintype "passive"))
      (node (ref "K4") (pin "1") (pinfunction "1_1") (pintype "passive"))
      (node (ref "K6") (pin "1") (pinfunction "1_1") (pintype "passive"))
      (node (ref "K8") (pin "1") (pinfunction "1_1") (pintype "passive"))
      (node (ref "U16") (pin "2") (pinfunction "2B_2") (pintype "passive"))
    )
    (net (code "211") (name "Net-(U16-3B)") (class "Default")
      (node (ref "K11") (pin "1") (pinfunction "1_1") (pintype "passive"))
      (node (ref "K13") (pin "1") (pinfunction "1_1") (pintype "passive"))
      (node (ref "K15") (pin "1") (pinfunction "1_1") (pintype "passive"))
      (node (ref "K17") (pin "1") (pinfunction "1_1") (pintype "passive"))
      (node (ref "K3") (pin "1") (pinfunction "1_1") (pintype "passive"))
      (node (ref "K5") (pin "1") (pinfunction "1_1") (pintype "passive"))
      (node (ref "K7") (pin "1") (pinfunction "1_1") (pintype "passive"))
      (node (ref "K9") (pin "1") (pinfunction "1_1") (pintype "passive"))
      (node (ref "U16") (pin "3") (pinfunction "3B_3") (pintype "passive"))
    )
    (net (code "212") (name "Net-(U18-OD)") (class "Default")
      (node (ref "R112") (pin "1") (pinfunction "1_1") (pintype "passive"))
      (node (ref "U18") (pin "9") (pinfunction "OD_9") (pintype "passive"))
    )
    (net (code "213") (name "Net-(U18-SET)") (class "Default")
      (node (ref "K13") (pin "3") (pinfunction "3_3") (pintype "passive"))
      (node (ref "R111") (pin "1") (pinfunction "1_1") (pintype "passive"))
      (node (ref "U18") (pin "7") (pinfunction "SET_7") (pintype "passive"))
    )
    (net (code "214") (name "Net-(U19-OD)") (class "Default")
      (node (ref "R123") (pin "1") (pinfunction "1_1") (pintype "passive"))
      (node (ref "U19") (pin "9") (pinfunction "OD_9") (pintype "passive"))
    )
    (net (code "215") (name "Net-(U19-SET)") (class "Default")
      (node (ref "K15") (pin "3") (pinfunction "3_3") (pintype "passive"))
      (node (ref "R122") (pin "1") (pinfunction "1_1") (pintype "passive"))
      (node (ref "U19") (pin "7") (pinfunction "SET_7") (pintype "passive"))
    )
    (net (code "216") (name "Net-(U20-OD)") (class "Default")
      (node (ref "R128") (pin "1") (pinfunction "1_1") (pintype "passive"))
      (node (ref "U20") (pin "9") (pinfunction "OD_9") (pintype "passive"))
    )
    (net (code "217") (name "Net-(U20-SET)") (class "Default")
      (node (ref "K17") (pin "3") (pinfunction "3_3") (pintype "passive"))
      (node (ref "R127") (pin "1") (pinfunction "1_1") (pintype "passive"))
      (node (ref "U20") (pin "7") (pinfunction "SET_7") (pintype "passive"))
    )
    (net (code "218") (name "unconnected-(P1-NC-Pad3)") (class "Default")
      (node (ref "P1") (pin "3") (pinfunction "NC_3") (pintype "passive"))
    )
    (net (code "219") (name "unconnected-(U8-REGF-Pad5)") (class "Default")
      (node (ref "U8") (pin "5") (pinfunction "REGF_5") (pintype "passive+no_connect"))
    )
    (net (code "220") (name "unconnected-(U8-REGS-Pad4)") (class "Default")
      (node (ref "U8") (pin "4") (pinfunction "REGS_4") (pintype "passive+no_connect"))
    )
    (net (code "221") (name "unconnected-(U8-~{EF}-Pad8)") (class "Default")
      (node (ref "U8") (pin "8") (pinfunction "~{EF}_8") (pintype "passive+no_connect"))
    )
    (net (code "222") (name "unconnected-(U9-PA3{slash}USART2_RX{slash}TIM5_CH4{slash}TIM9_CH2{slash}TIM2_CH4{slash}OTG_HS_ULPI_D0{slash}ETH_MII_COL{slash}EVENTOUT{slash}ADC123_IN3-Pad26)") (class "Default")
      (node (ref "U9") (pin "26") (pinfunction "PA3/USART2_RX/TIM5_CH4/TIM9_CH2/TIM2_CH4/OTG_HS_ULPI_D0/ETH_MII_COL/EVENTOUT/ADC123_IN3_26") (pintype "bidirectional"))
    )
    (net (code "223") (name "unconnected-(U9-PA11{slash}USART1_CTS{slash}CAN1_RX{slash}TIM1_CH4{slash}OTG_FS_DM{slash}EVENTOUT-Pad70)") (class "Default")
      (node (ref "U9") (pin "70") (pinfunction "PA11/USART1_CTS/CAN1_RX/TIM1_CH4/OTG_FS_DM/EVENTOUT_70") (pintype "bidirectional"))
    )
    (net (code "224") (name "unconnected-(U9-PA12{slash}USART1_RTS{slash}CAN1_TX{slash}TIM1_ETR{slash}OTG_FS_DP{slash}EVENTOUT-Pad71)") (class "Default")
      (node (ref "U9") (pin "71") (pinfunction "PA12/USART1_RTS/CAN1_TX/TIM1_ETR/OTG_FS_DP/EVENTOUT_71") (pintype "bidirectional"))
    )
    (net (code "225") (name "unconnected-(U9-PA15(JTDI){slash}JTDI{slash}SPI3_NSS{slash}I2S3_WS{slash}TIM2_CH1_ETR{slash}SPI1_NSS{slash}EVENTOUT-Pad77)") (class "Default")
      (node (ref "U9") (pin "77") (pinfunction "PA15(JTDI)/JTDI/SPI3_NSS/I2S3_WS/TIM2_CH1_ETR/SPI1_NSS/EVENTOUT_77") (pintype "bidirectional"))
    )
    (net (code "226") (name "unconnected-(U9-PB1{slash}TIM3_CH4{slash}TIM8_CH3N{slash}OTG_HS_ULPI_D2{slash}ETH_MII_RXD3{slash}OTG_HS_INTN{slash}TIM1_CH3N{slash}EVENTOUT{slash}ADC12_IN9-Pad36)") (class "Default")
      (node (ref "U9") (pin "36") (pinfunction "PB1/TIM3_CH4/TIM8_CH3N/OTG_HS_ULPI_D2/ETH_MII_RXD3/OTG_HS_INTN/TIM1_CH3N/EVENTOUT/ADC12_IN9_36") (pintype "bidirectional"))
    )
    (net (code "227") (name "unconnected-(U9-PB7{slash}I2C1_SDA{slash}FSMC_NL{slash}DCMI_VSYNC{slash}USART1_RX{slash}TIM4_CH2{slash}EVENTOUT-Pad93)") (class "Default")
      (node (ref "U9") (pin "93") (pinfunction "PB7/I2C1_SDA/FSMC_NL/DCMI_VSYNC/USART1_RX/TIM4_CH2/EVENTOUT_93") (pintype "bidirectional"))
    )
    (net (code "228") (name "unconnected-(U9-PB8{slash}TIM4_CH3{slash}SDIO_D4{slash}TIM10_CH1{slash}DCMI_D6{slash}ETH_MII_TXD3{slash}I2C1_SCL{slash}CAN1_RX{slash}EVENTOUT-Pad95)") (class "Default")
      (node (ref "U9") (pin "95") (pinfunction "PB8/TIM4_CH3/SDIO_D4/TIM10_CH1/DCMI_D6/ETH_MII_TXD3/I2C1_SCL/CAN1_RX/EVENTOUT_95") (pintype "bidirectional"))
    )
    (net (code "229") (name "unconnected-(U9-PB9{slash}SPI2_NSS{slash}I2S2_WS{slash}TIM4_CH4{slash}TIM11_CH1{slash}SDIO_D5{slash}DCMI_D7{slash}I2C1_SDA{slash}CAN1_TX{slash}EVENTOUT-Pad96)") (class "Default")
      (node (ref "U9") (pin "96") (pinfunction "PB9/SPI2_NSS/I2S2_WS/TIM4_CH4/TIM11_CH1/SDIO_D5/DCMI_D7/I2C1_SDA/CAN1_TX/EVENTOUT_96") (pintype "bidirectional"))
    )
    (net (code "230") (name "unconnected-(U9-PB12{slash}SPI2_NSS{slash}I2S2_WS{slash}I2C2_SMBA{slash}USART3_CK{slash}TIM1_BKIN{slash}CAN2_RX{slash}OTG_HS_ULPI_D5{slash}ETH_RMII_TXD0{slash}ETH_MII_TXD0{slash}OTG_HS_ID{slash}EVENTOUT-Pad51)") (class "Default")
      (node (ref "U9") (pin "51") (pinfunction "PB12/SPI2_NSS/I2S2_WS/I2C2_SMBA/USART3_CK/TIM1_BKIN/CAN2_RX/OTG_HS_ULPI_D5/ETH_RMII_TXD0/ETH_MII_TXD0/OTG_HS_ID/EVENTOUT_51") (pintype "bidirectional"))
    )
    (net (code "231") (name "unconnected-(U9-PB13{slash}SPI2_SCK{slash}I2S2_CK{slash}USART3_CTS{slash}TIM1_CH1N{slash}CAN2_TX{slash}OTG_HS_ULPI_D6{slash}ETH_RMII_TXD1{slash}ETH_MII_TXD1{slash}EVENTOUT{slash}OTG_HS_VBUS-Pad52)") (class "Default")
      (node (ref "U9") (pin "52") (pinfunction "PB13/SPI2_SCK/I2S2_CK/USART3_CTS/TIM1_CH1N/CAN2_TX/OTG_HS_ULPI_D6/ETH_RMII_TXD1/ETH_MII_TXD1/EVENTOUT/OTG_HS_VBUS_52") (pintype "bidirectional"))
    )
    (net (code "232") (name "unconnected-(U9-PB15{slash}SPI2_MOSI{slash}I2S2_SD{slash}TIM1_CH3N{slash}TIM8_CH3N{slash}TIM12_CH2{slash}OTG_HS_DP{slash}EVENTOUT-Pad54)") (class "Default")
      (node (ref "U9") (pin "54") (pinfunction "PB15/SPI2_MOSI/I2S2_SD/TIM1_CH3N/TIM8_CH3N/TIM12_CH2/OTG_HS_DP/EVENTOUT_54") (pintype "bidirectional"))
    )
    (net (code "233") (name "unconnected-(U9-PC0{slash}OTG_HS_ULPI_STP{slash}EVENTOUT{slash}ADC123_IN10-Pad15)") (class "Default")
      (node (ref "U9") (pin "15") (pinfunction "PC0/OTG_HS_ULPI_STP/EVENTOUT/ADC123_IN10_15") (pintype "bidirectional"))
    )
    (net (code "234") (name "unconnected-(U9-PC1{slash}ETH_MDC{slash}EVENTOUT{slash}ADC123_IN11-Pad16)") (class "Default")
      (node (ref "U9") (pin "16") (pinfunction "PC1/ETH_MDC/EVENTOUT/ADC123_IN11_16") (pintype "bidirectional"))
    )
    (net (code "235") (name "unconnected-(U9-PC2{slash}SPI2_MISO{slash}OTG_HS_ULPI_DIR{slash}TH_MII_TXD2{slash}I2S2ext_SD{slash}EVENTOUT{slash}ADC123_IN12-Pad17)") (class "Default")
      (node (ref "U9") (pin "17") (pinfunction "PC2/SPI2_MISO/OTG_HS_ULPI_DIR/TH_MII_TXD2/I2S2ext_SD/EVENTOUT/ADC123_IN12_17") (pintype "bidirectional"))
    )
    (net (code "236") (name "unconnected-(U9-PC3{slash}SPI2_MOSI{slash}I2S2_SD{slash}OTG_HS_ULPI_NXT{slash}ETH_MII_TX_CLK{slash}EVENTOUT{slash}ADC123_IN13-Pad18)") (class "Default")
      (node (ref "U9") (pin "18") (pinfunction "PC3/SPI2_MOSI/I2S2_SD/OTG_HS_ULPI_NXT/ETH_MII_TX_CLK/EVENTOUT/ADC123_IN13_18") (pintype "bidirectional"))
    )
    (net (code "237") (name "unconnected-(U9-PD2{slash}TIM3_ETR{slash}UART5_RX{slash}SDIO_CMD{slash}DCMI_D11{slash}EVENTOUT-Pad83)") (class "Default")
      (node (ref "U9") (pin "83") (pinfunction "PD2/TIM3_ETR/UART5_RX/SDIO_CMD/DCMI_D11/EVENTOUT_83") (pintype "bidirectional"))
    )
    (net (code "238") (name "unconnected-(U9-PD3{slash}FSMC_CLK{slash}USART2_CTS{slash}EVENTOUT-Pad84)") (class "Default")
      (node (ref "U9") (pin "84") (pinfunction "PD3/FSMC_CLK/USART2_CTS/EVENTOUT_84") (pintype "bidirectional"))
    )
    (net (code "239") (name "unconnected-(U9-PD6{slash}FSMC_NWAIT{slash}USART2_RX{slash}EVENTOUT-Pad87)") (class "Default")
      (node (ref "U9") (pin "87") (pinfunction "PD6/FSMC_NWAIT/USART2_RX/EVENTOUT_87") (pintype "bidirectional"))
    )
    (net (code "240") (name "unconnected-(U9-PE0{slash}TIM4_ETR{slash}FSMC_NBL0{slash}DCMI_D2{slash}EVENTOUT-Pad97)") (class "Default")
      (node (ref "U9") (pin "97") (pinfunction "PE0/TIM4_ETR/FSMC_NBL0/DCMI_D2/EVENTOUT_97") (pintype "bidirectional"))
    )
    (net (code "241") (name "unconnected-(U9-PE1{slash}FSMC_NBL1{slash}DCMI_D3{slash}EVENTOUT-Pad98)") (class "Default")
      (node (ref "U9") (pin "98") (pinfunction "PE1/FSMC_NBL1/DCMI_D3/EVENTOUT_98") (pintype "bidirectional"))
    )
    (net (code "242") (name "unconnected-(U9-PE5{slash}TRACED2{slash}FSMC_A21{slash}TIM9_CH1{slash}DCMI_D6{slash}EVENTOUT-Pad4)") (class "Default")
      (node (ref "U9") (pin "4") (pinfunction "PE5/TRACED2/FSMC_A21/TIM9_CH1/DCMI_D6/EVENTOUT_4") (pintype "bidirectional"))
    )
    (net (code "243") (name "unconnected-(U9-PE6{slash}TRACED3{slash}FSMC_A22{slash}TIM9_CH2{slash}DCMI_D7{slash}EVENTOUT-Pad5)") (class "Default")
      (node (ref "U9") (pin "5") (pinfunction "PE6/TRACED3/FSMC_A22/TIM9_CH2/DCMI_D7/EVENTOUT_5") (pintype "bidirectional"))
    )
    (net (code "244") (name "unconnected-(U10-REGF-Pad5)") (class "Default")
      (node (ref "U10") (pin "5") (pinfunction "REGF_5") (pintype "passive+no_connect"))
    )
    (net (code "245") (name "unconnected-(U10-REGS-Pad4)") (class "Default")
      (node (ref "U10") (pin "4") (pinfunction "REGS_4") (pintype "passive+no_connect"))
    )
    (net (code "246") (name "unconnected-(U10-~{EF}-Pad8)") (class "Default")
      (node (ref "U10") (pin "8") (pinfunction "~{EF}_8") (pintype "passive+no_connect"))
    )
    (net (code "247") (name "unconnected-(U11-REGF-Pad5)") (class "Default")
      (node (ref "U11") (pin "5") (pinfunction "REGF_5") (pintype "passive+no_connect"))
    )
    (net (code "248") (name "unconnected-(U11-REGS-Pad4)") (class "Default")
      (node (ref "U11") (pin "4") (pinfunction "REGS_4") (pintype "passive+no_connect"))
    )
    (net (code "249") (name "unconnected-(U11-~{EF}-Pad8)") (class "Default")
      (node (ref "U11") (pin "8") (pinfunction "~{EF}_8") (pintype "passive+no_connect"))
    )
    (net (code "250") (name "unconnected-(U12-REGF-Pad5)") (class "Default")
      (node (ref "U12") (pin "5") (pinfunction "REGF_5") (pintype "passive+no_connect"))
    )
    (net (code "251") (name "unconnected-(U12-REGS-Pad4)") (class "Default")
      (node (ref "U12") (pin "4") (pinfunction "REGS_4") (pintype "passive+no_connect"))
    )
    (net (code "252") (name "unconnected-(U12-~{EF}-Pad8)") (class "Default")
      (node (ref "U12") (pin "8") (pinfunction "~{EF}_8") (pintype "passive+no_connect"))
    )
    (net (code "253") (name "unconnected-(U15-REGF-Pad5)") (class "Default")
      (node (ref "U15") (pin "5") (pinfunction "REGF_5") (pintype "passive+no_connect"))
    )
    (net (code "254") (name "unconnected-(U15-REGS-Pad4)") (class "Default")
      (node (ref "U15") (pin "4") (pinfunction "REGS_4") (pintype "passive+no_connect"))
    )
    (net (code "255") (name "unconnected-(U15-~{EF}-Pad8)") (class "Default")
      (node (ref "U15") (pin "8") (pinfunction "~{EF}_8") (pintype "passive+no_connect"))
    )
    (net (code "256") (name "unconnected-(U18-REGF-Pad5)") (class "Default")
      (node (ref "U18") (pin "5") (pinfunction "REGF_5") (pintype "passive+no_connect"))
    )
    (net (code "257") (name "unconnected-(U18-REGS-Pad4)") (class "Default")
      (node (ref "U18") (pin "4") (pinfunction "REGS_4") (pintype "passive+no_connect"))
    )
    (net (code "258") (name "unconnected-(U18-~{EF}-Pad8)") (class "Default")
      (node (ref "U18") (pin "8") (pinfunction "~{EF}_8") (pintype "passive+no_connect"))
    )
    (net (code "259") (name "unconnected-(U19-REGF-Pad5)") (class "Default")
      (node (ref "U19") (pin "5") (pinfunction "REGF_5") (pintype "passive+no_connect"))
    )
    (net (code "260") (name "unconnected-(U19-REGS-Pad4)") (class "Default")
      (node (ref "U19") (pin "4") (pinfunction "REGS_4") (pintype "passive+no_connect"))
    )
    (net (code "261") (name "unconnected-(U19-~{EF}-Pad8)") (class "Default")
      (node (ref "U19") (pin "8") (pinfunction "~{EF}_8") (pintype "passive+no_connect"))
    )
    (net (code "262") (name "unconnected-(U20-REGF-Pad5)") (class "Default")
      (node (ref "U20") (pin "5") (pinfunction "REGF_5") (pintype "passive+no_connect"))
    )
    (net (code "263") (name "unconnected-(U20-REGS-Pad4)") (class "Default")
      (node (ref "U20") (pin "4") (pinfunction "REGS_4") (pintype "passive+no_connect"))
    )
    (net (code "264") (name "unconnected-(U20-~{EF}-Pad8)") (class "Default")
      (node (ref "U20") (pin "8") (pinfunction "~{EF}_8") (pintype "passive+no_connect"))
    )
  )
)
